# M8416V1.net
KiCad netlist of a schematic drawn in EAGLE
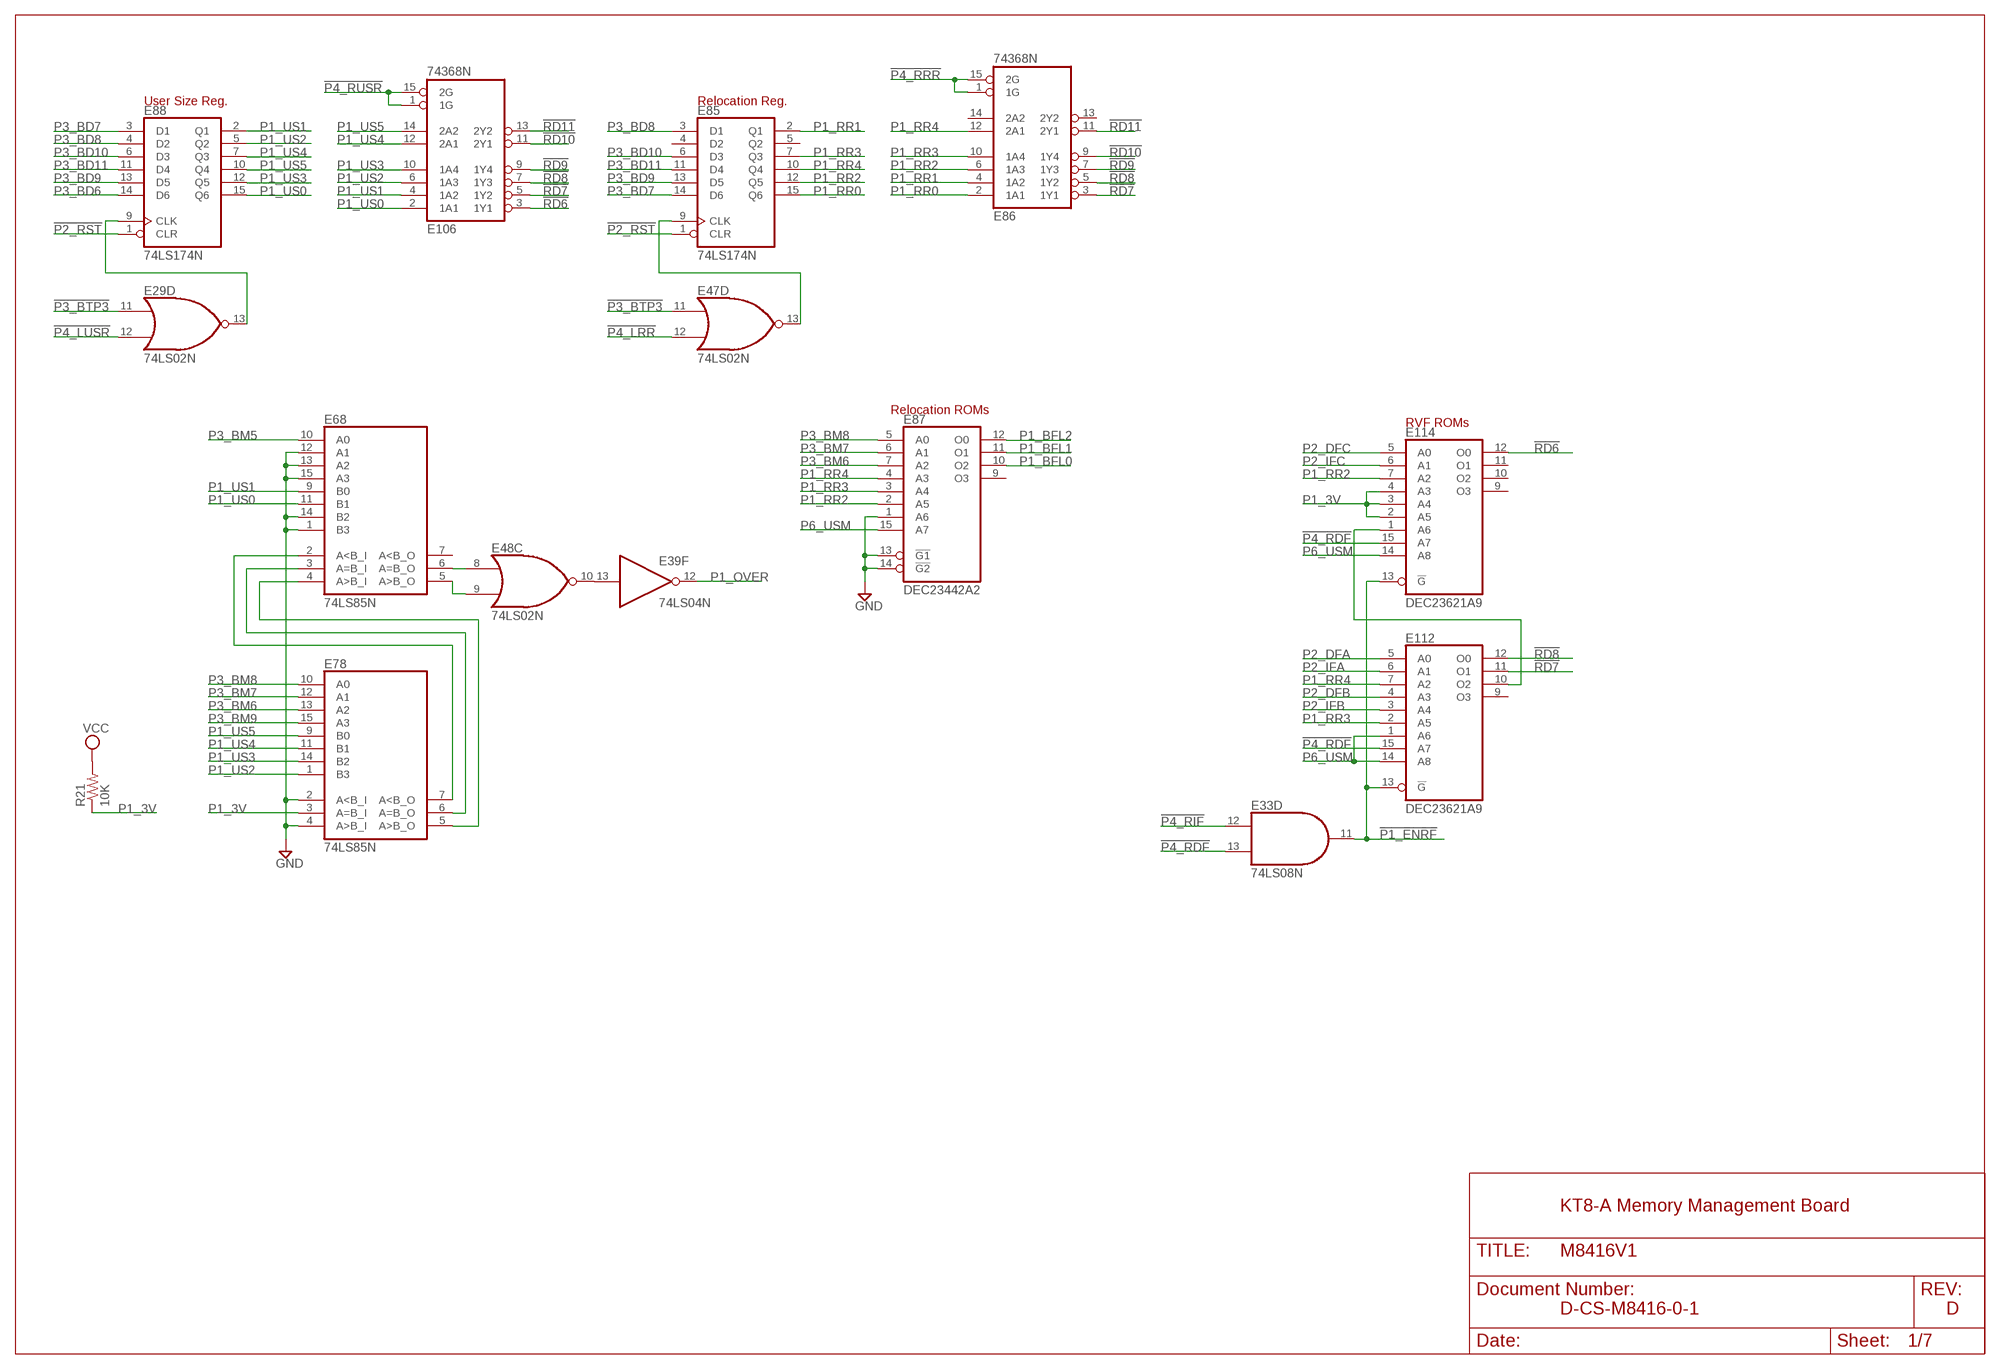
[diagram p0: schematic, sheet 1]
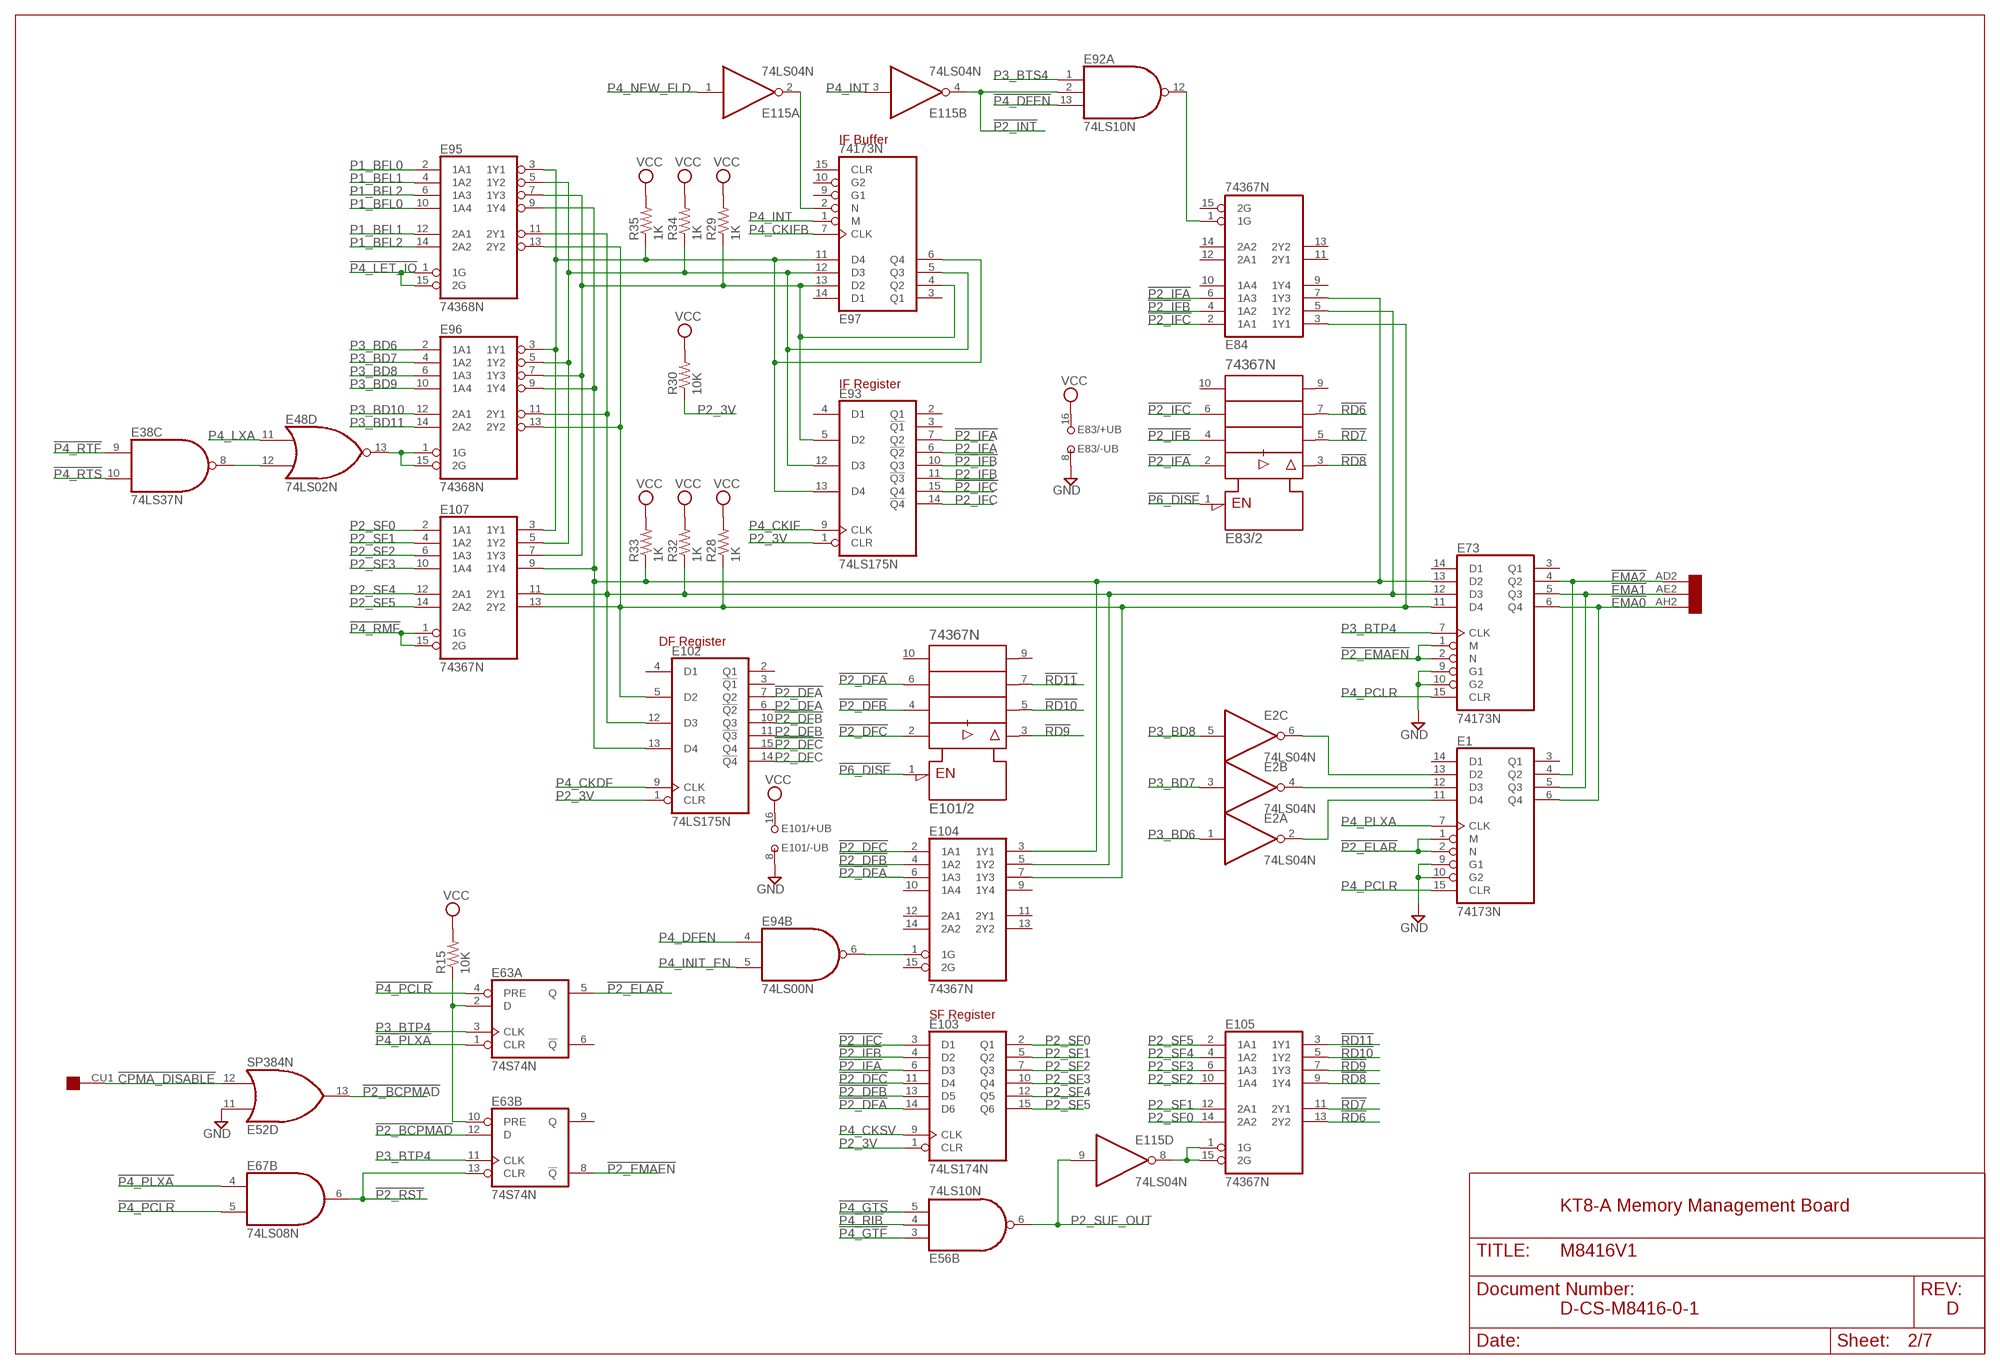
[diagram p1: schematic, sheet 2]
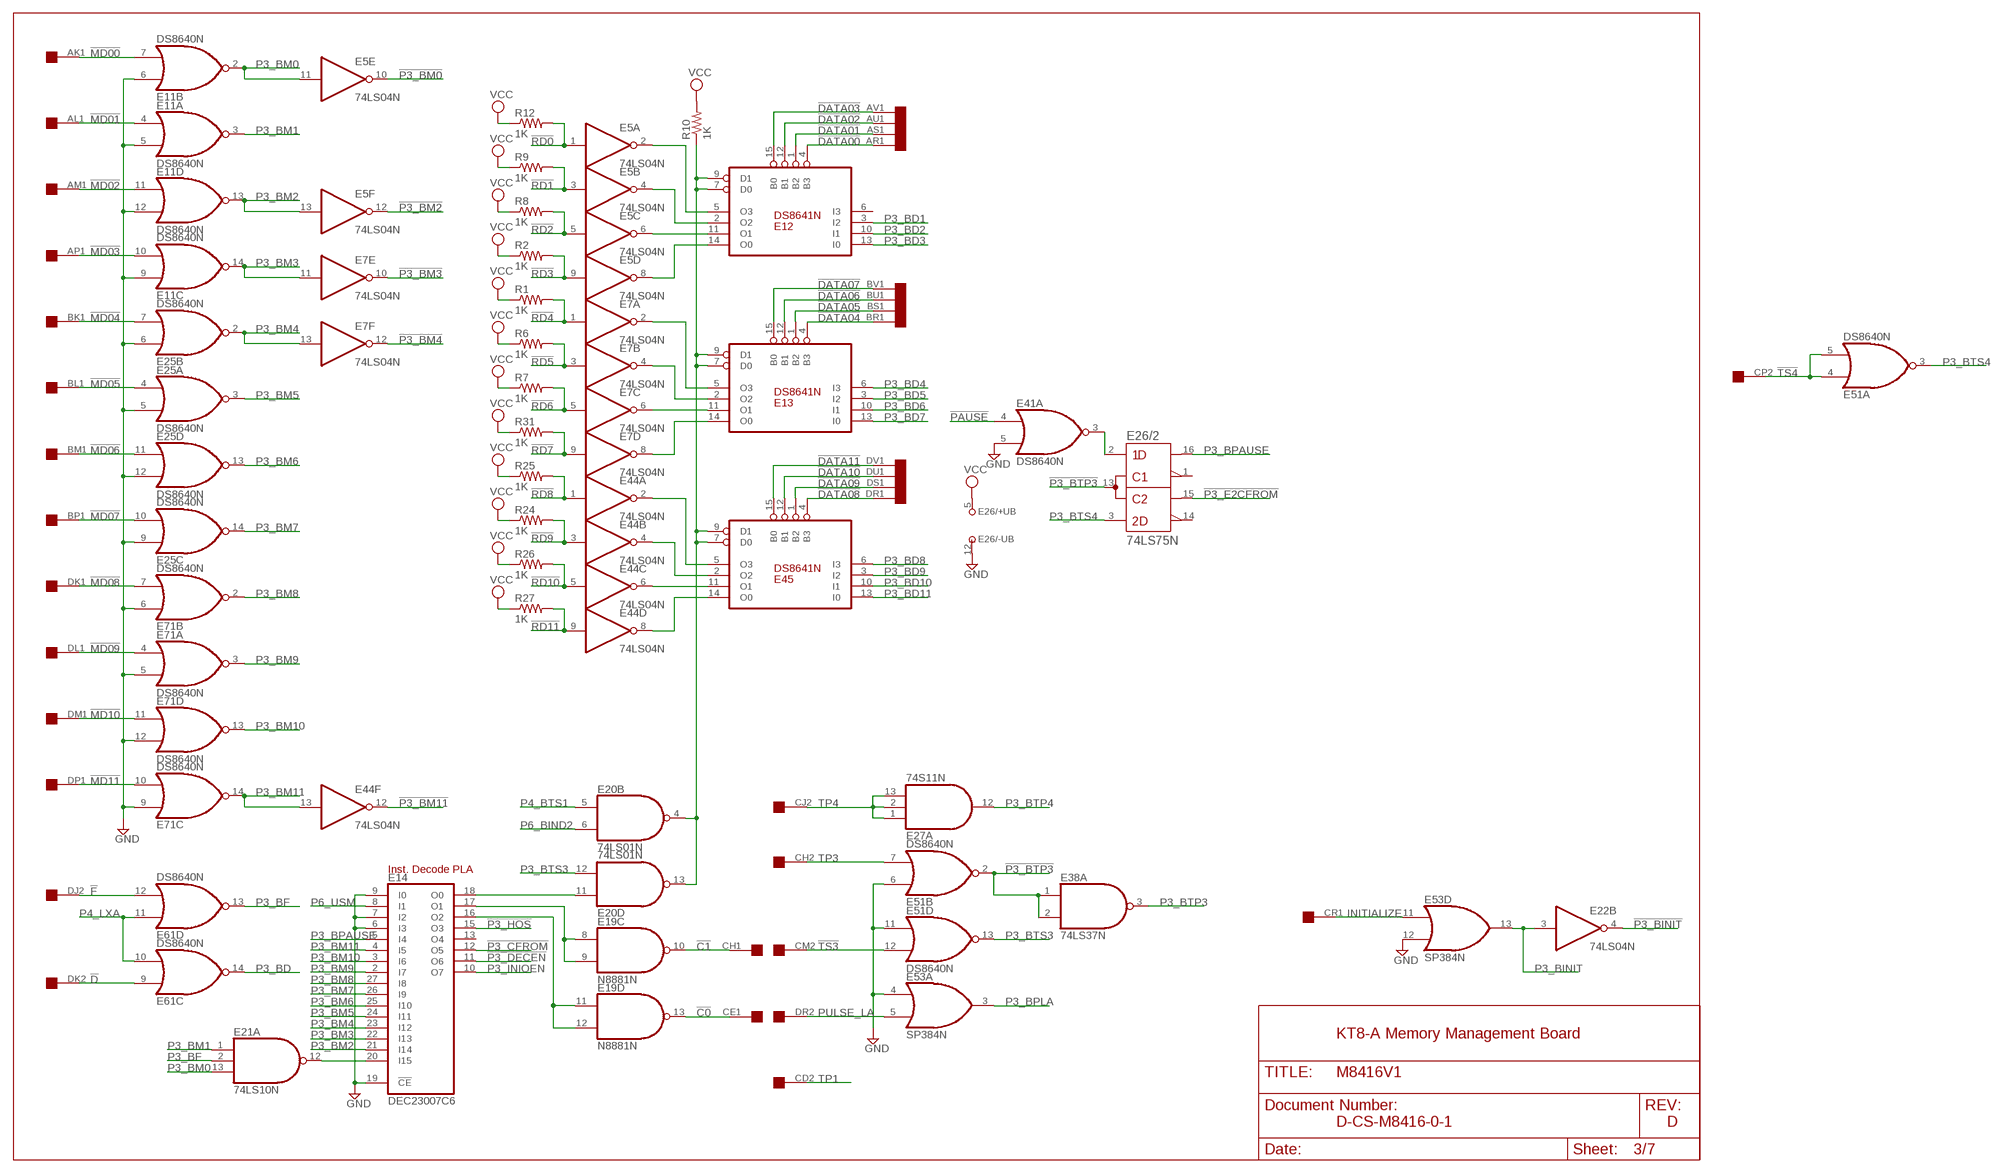
[diagram p2: schematic, sheet 3]
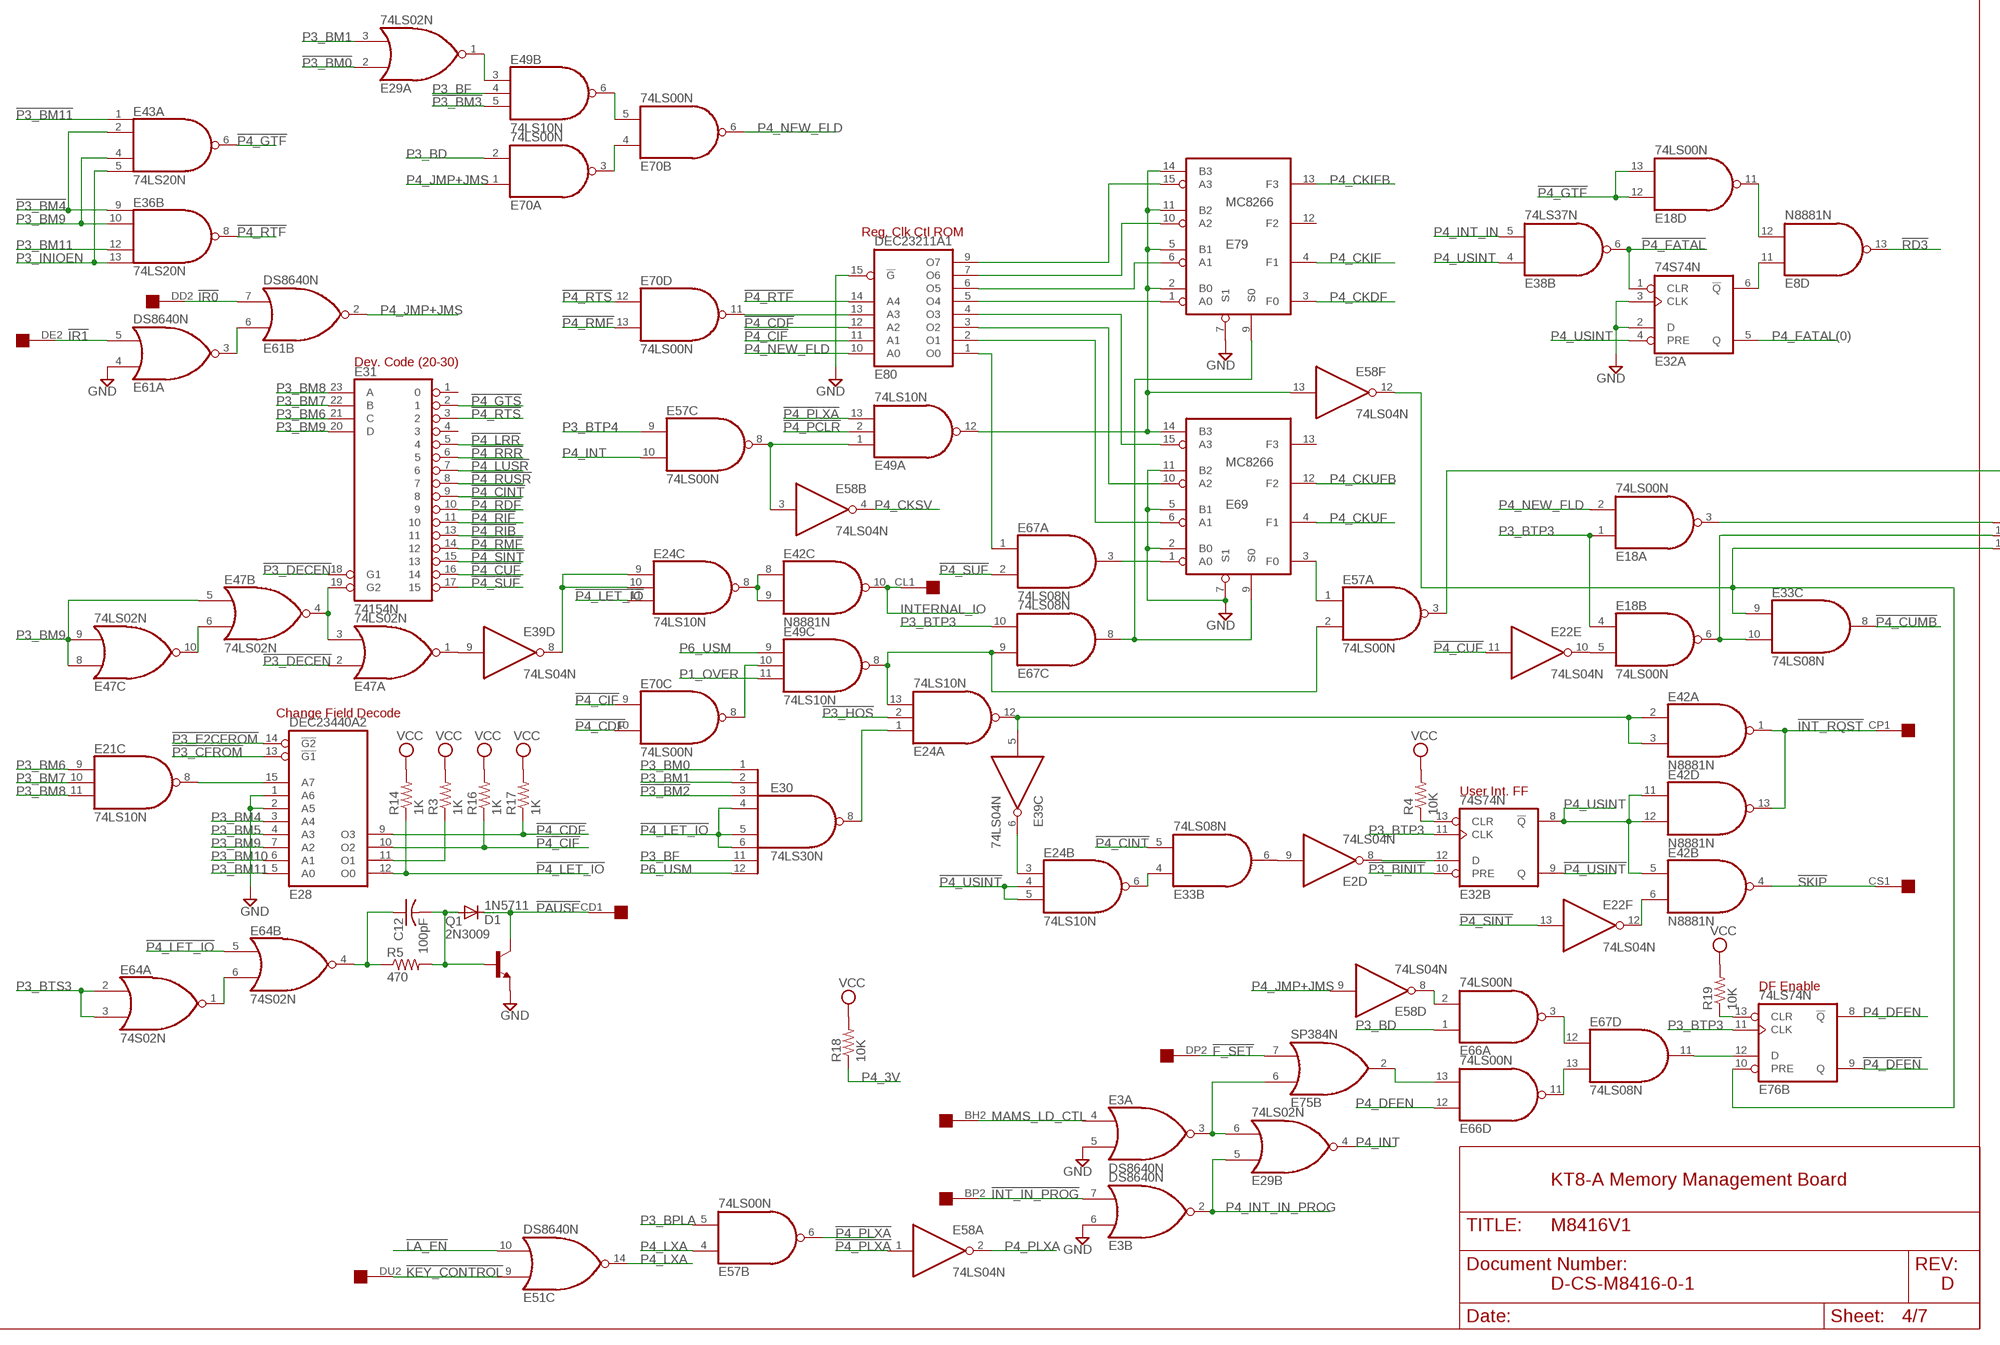
[diagram p3: schematic, sheet 4, part 1 of 2]
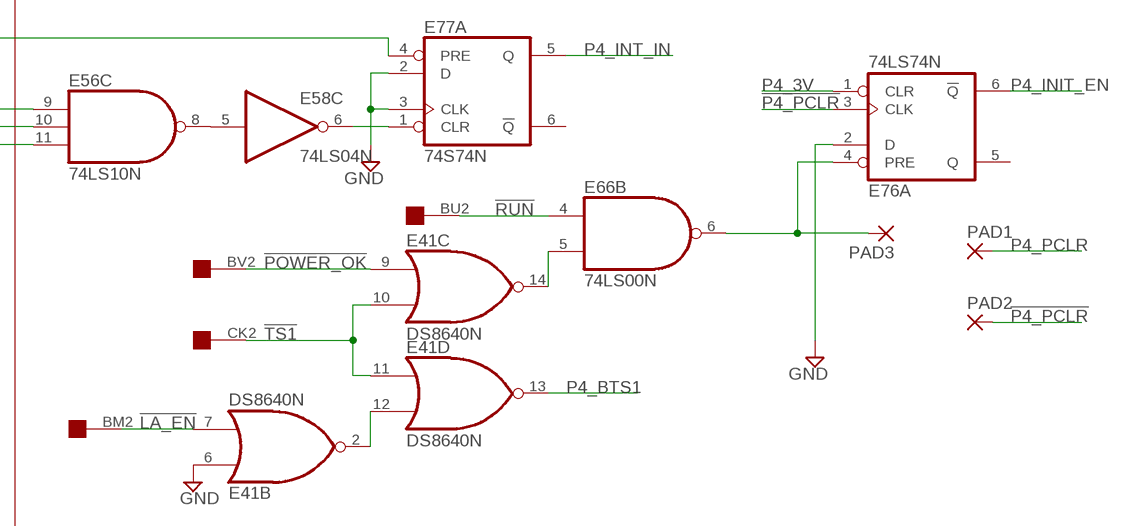
[diagram p4: schematic, sheet 4, part 2 of 2]
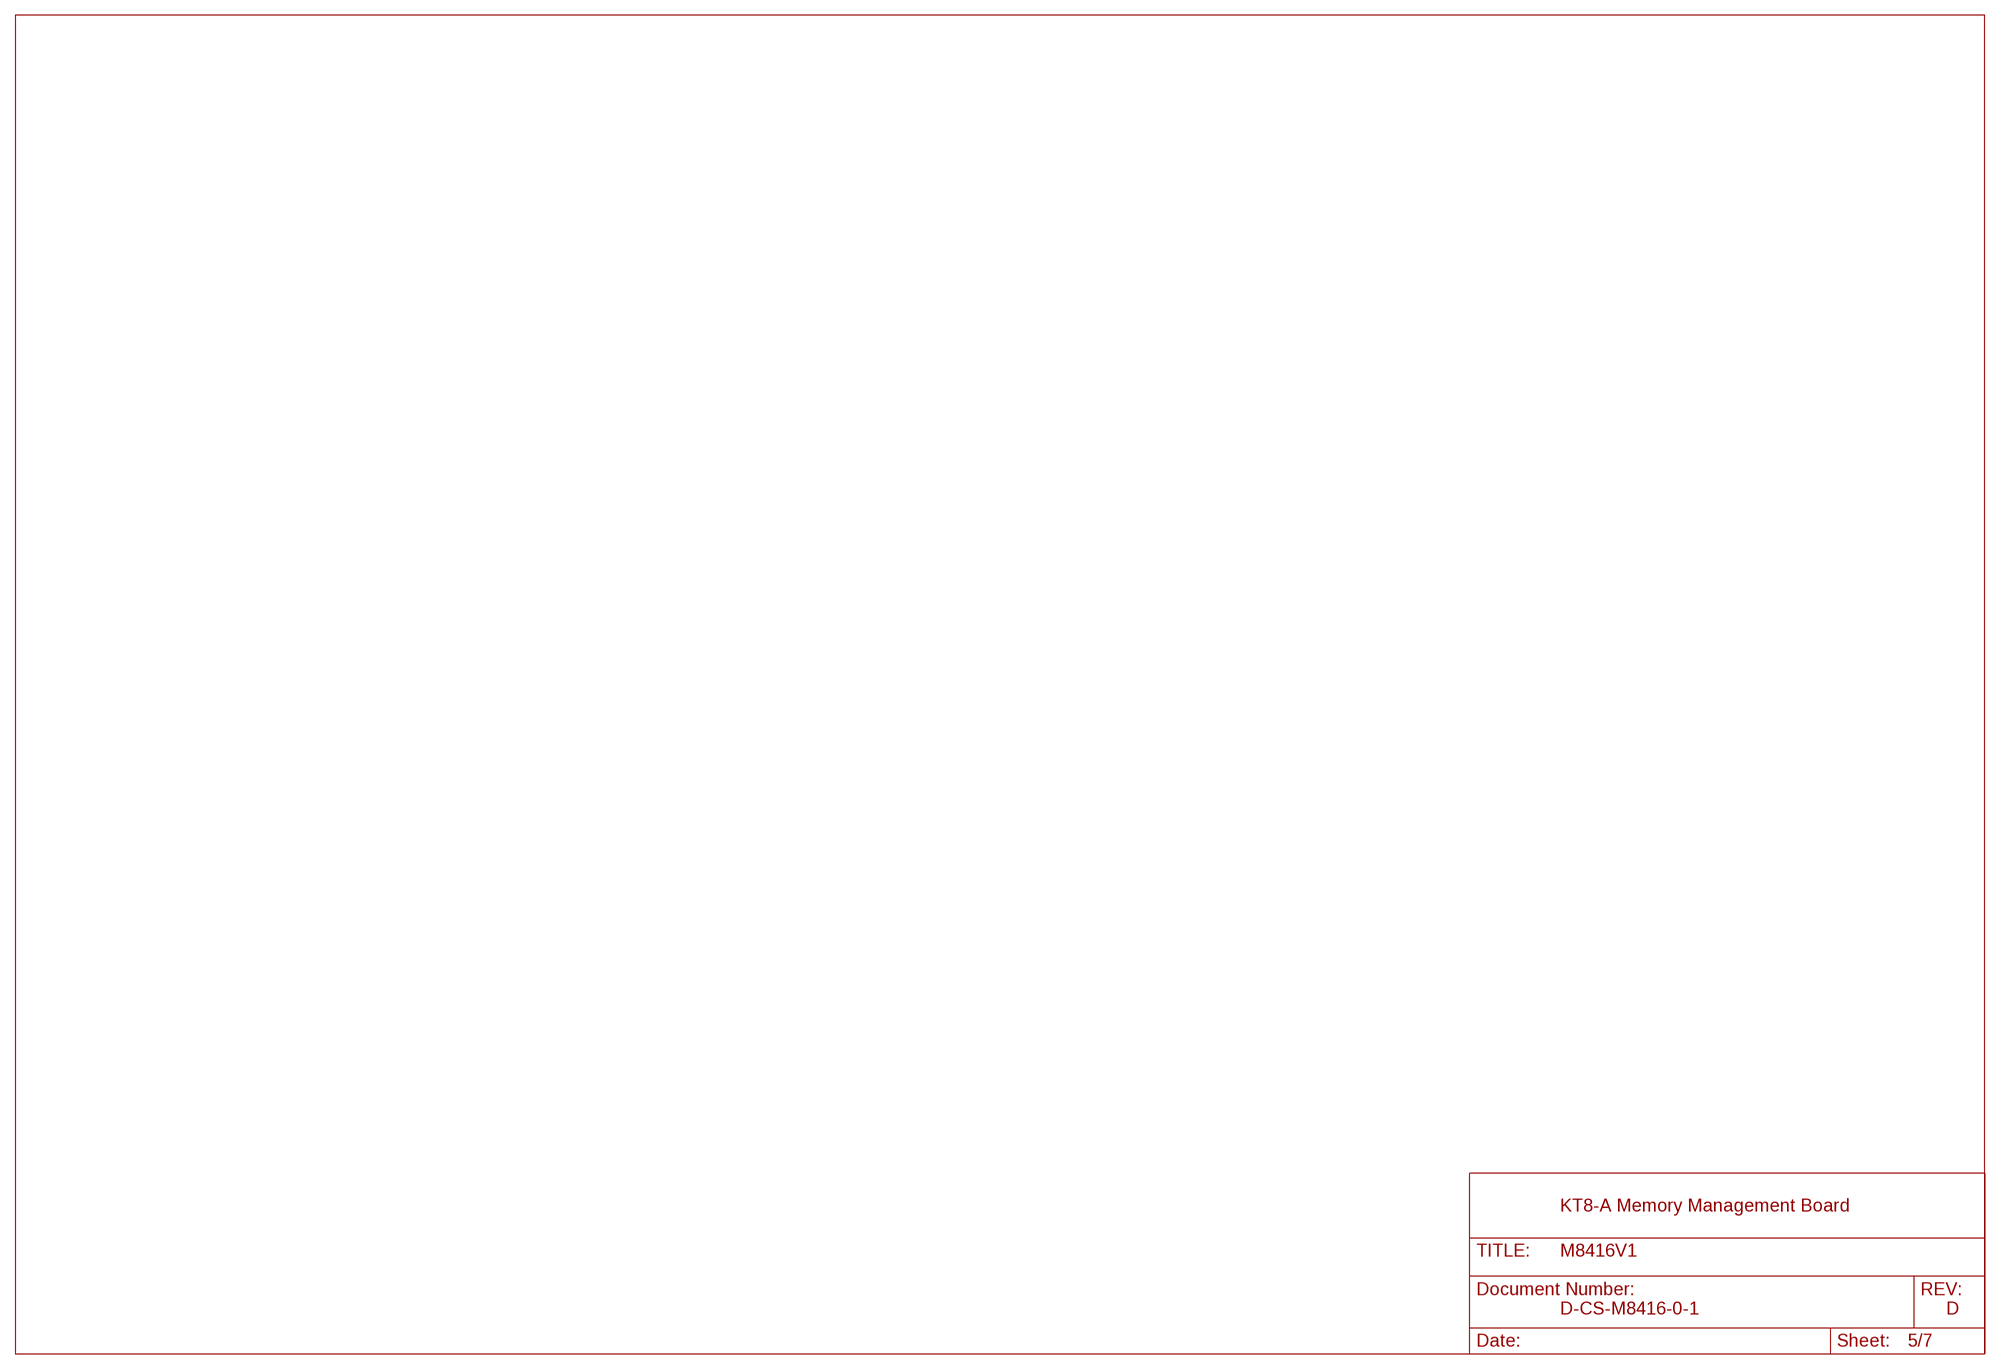
[diagram p5: schematic, sheet 5]
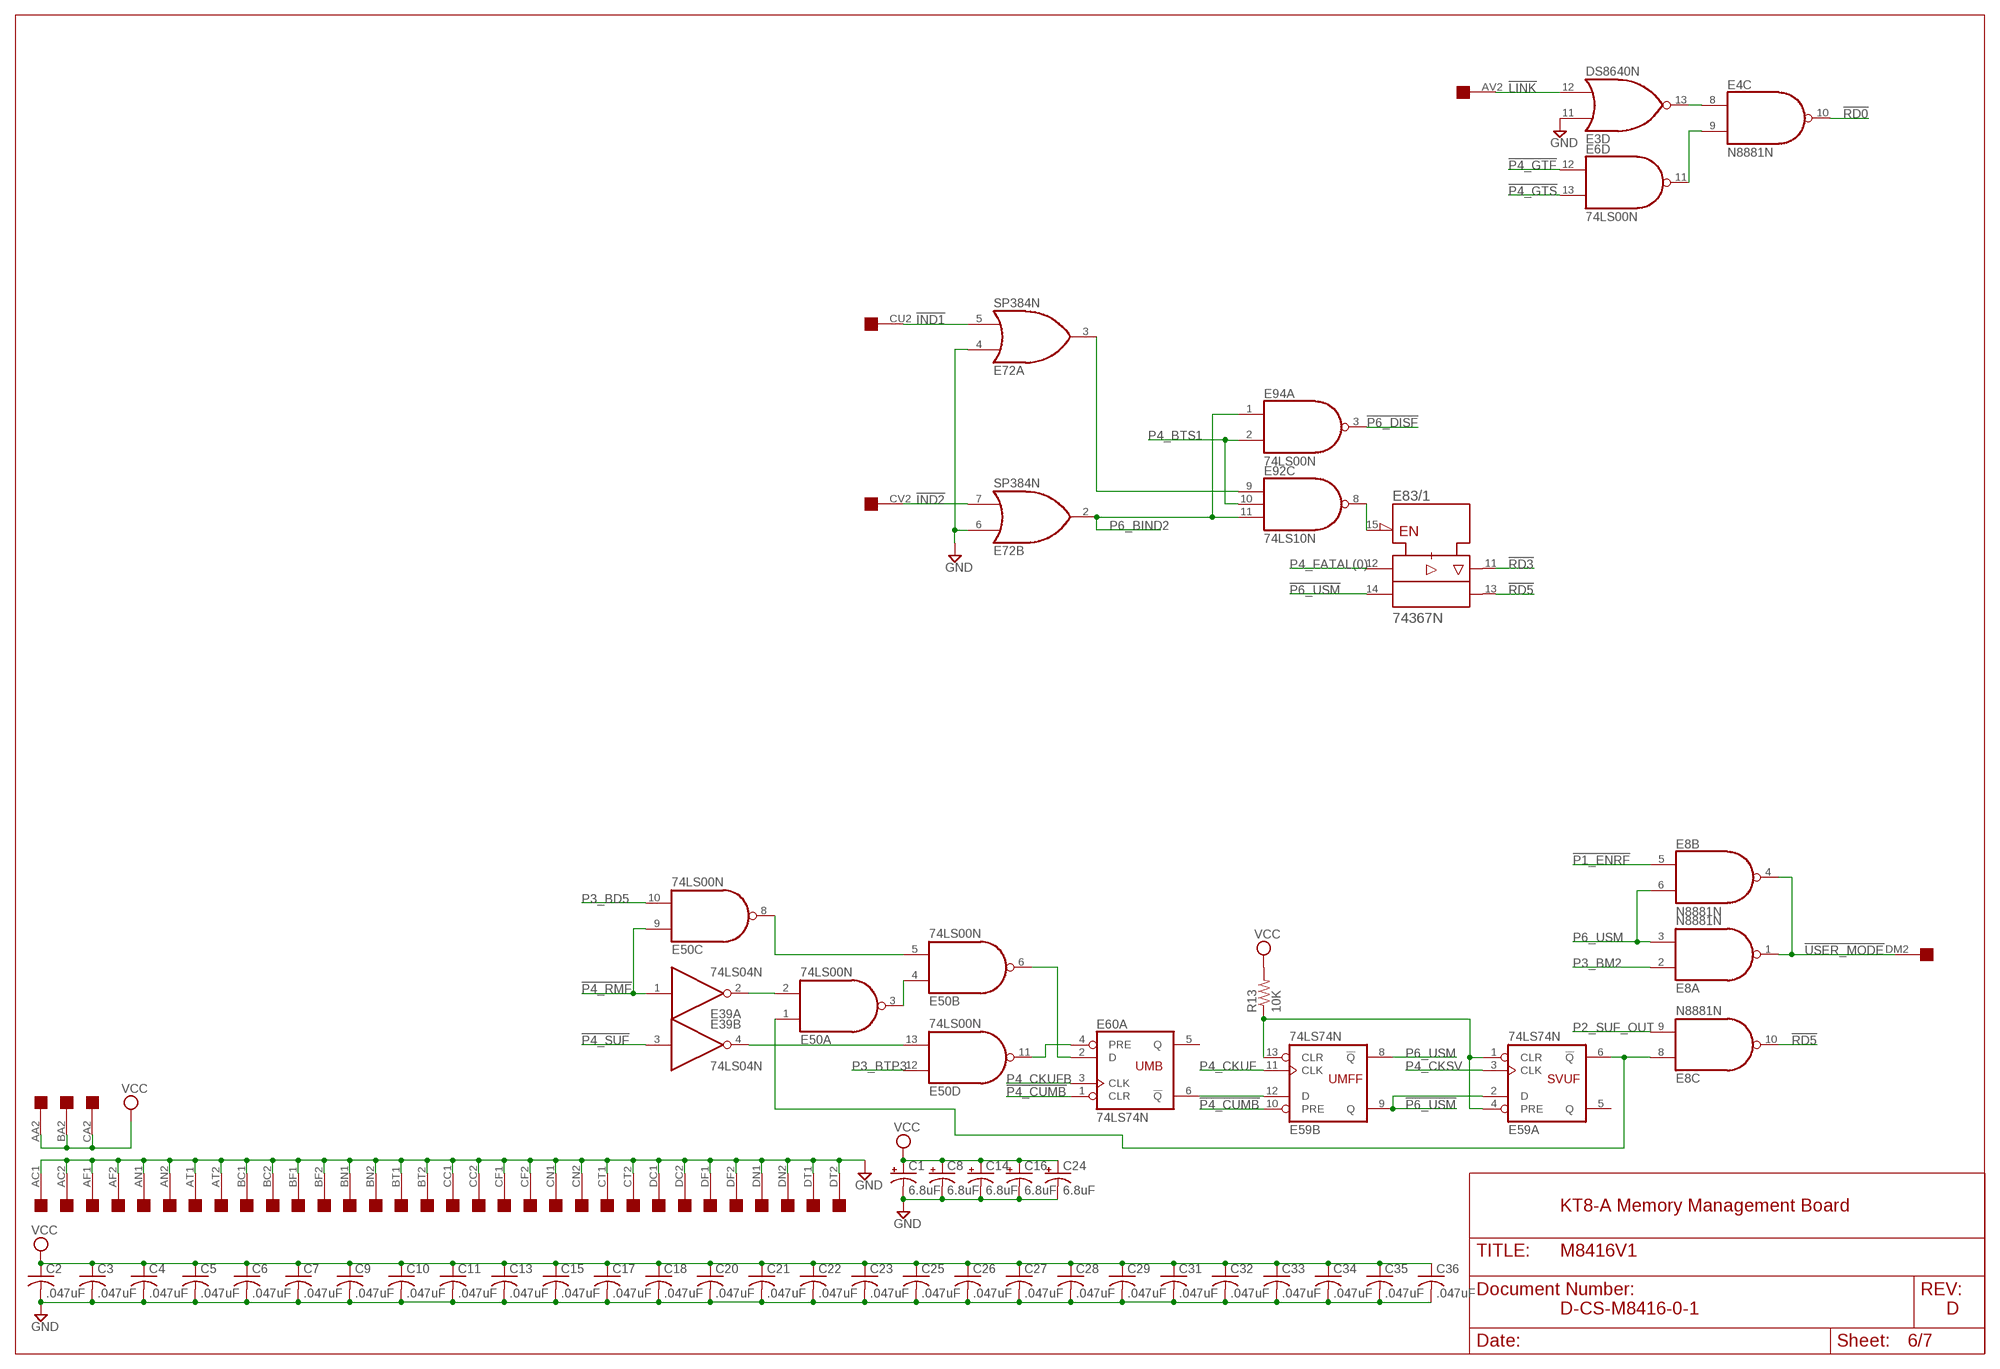
[diagram p6: schematic, sheet 6]
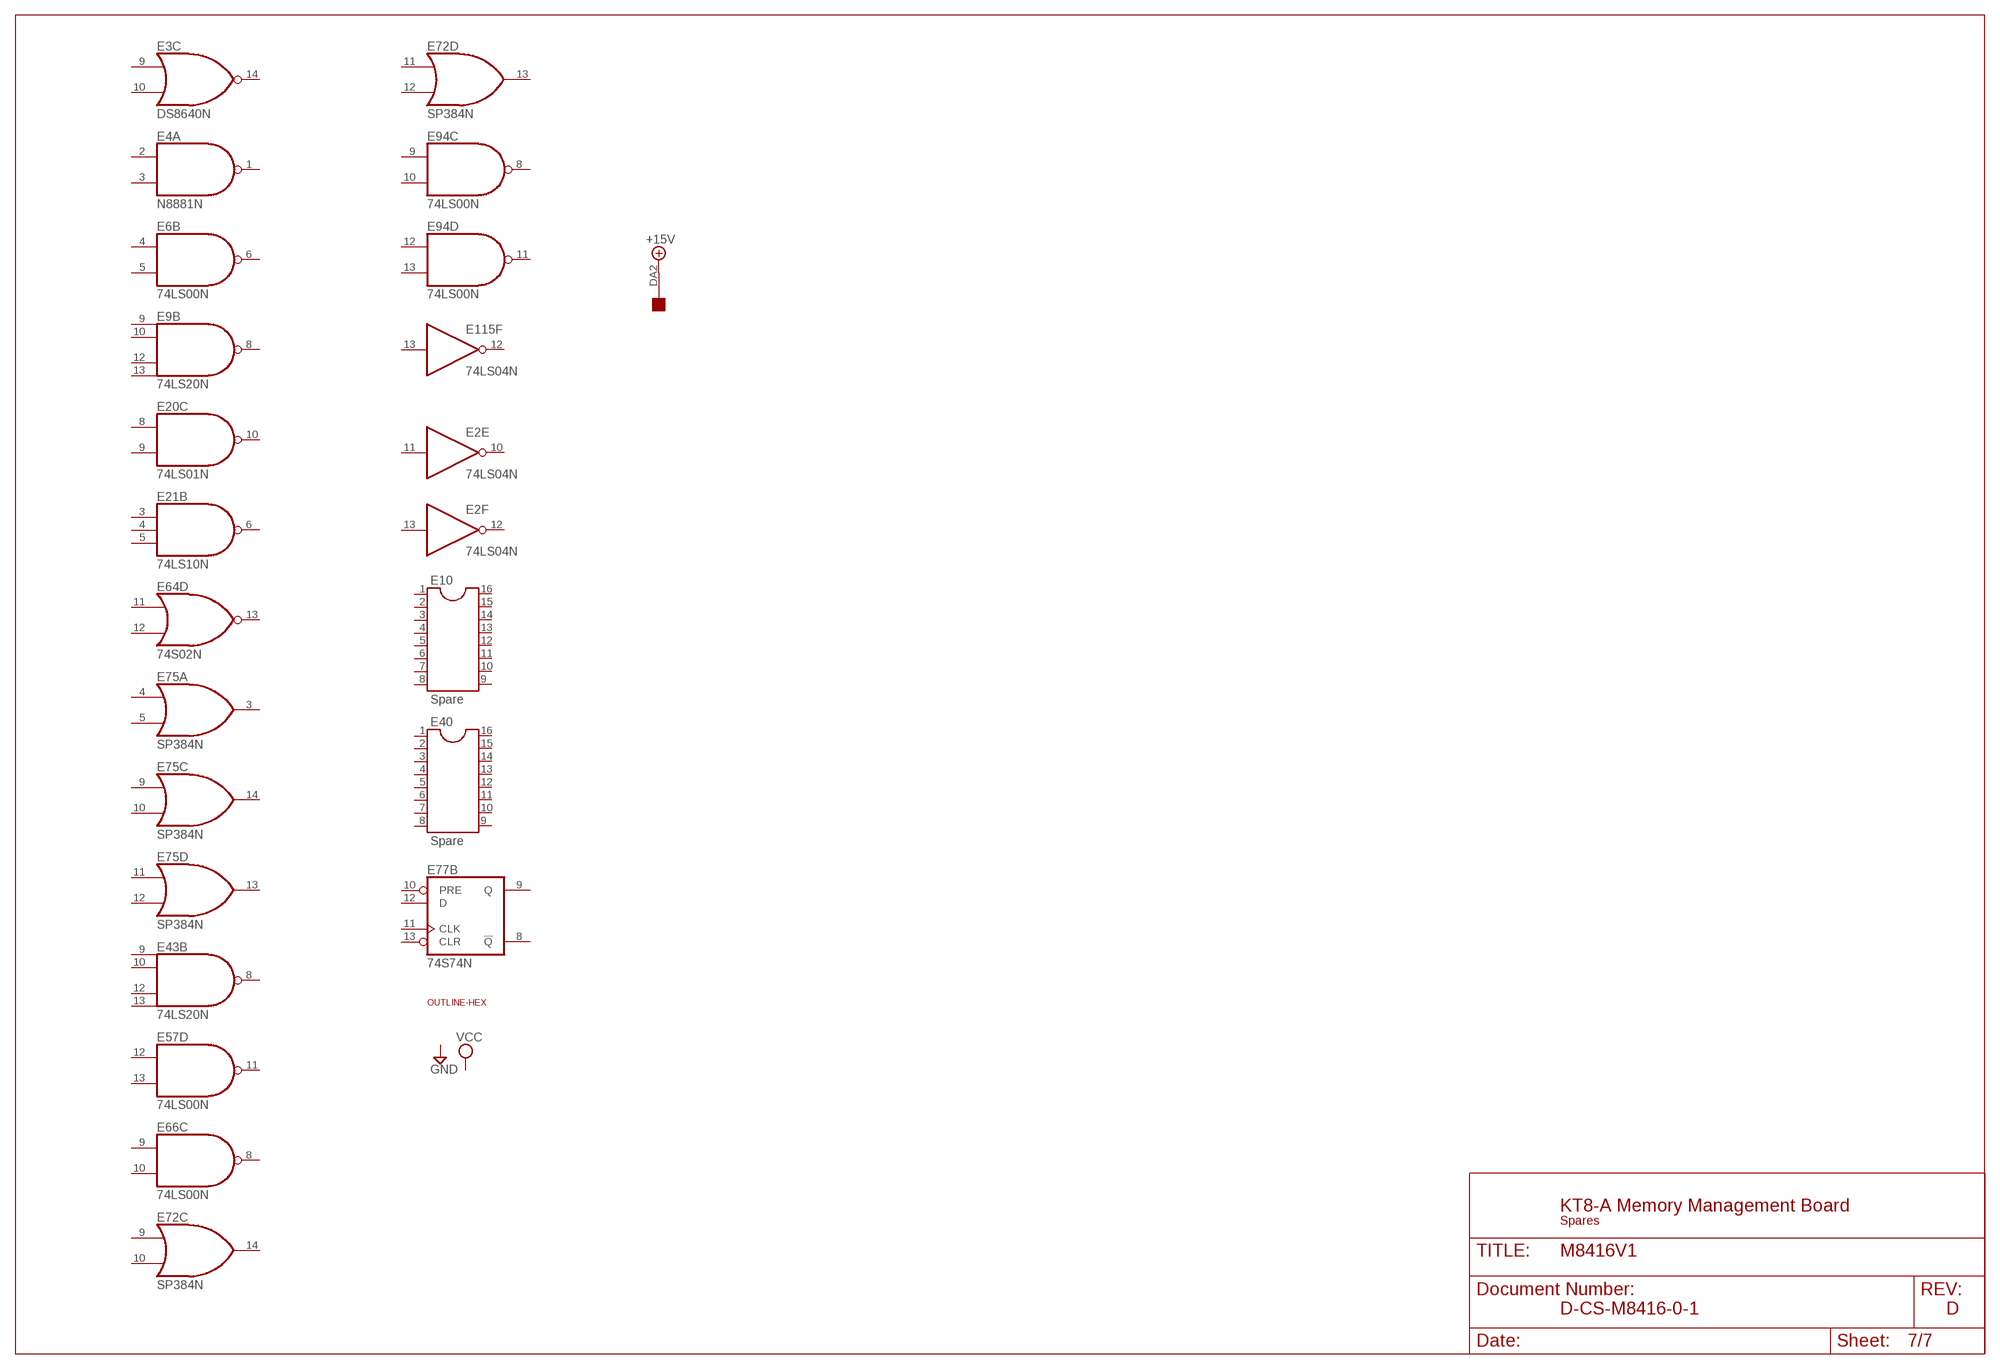
[diagram p7: schematic, sheet 7]

(export (version "E")
  (design (tool "Eeschema 10.0.6"))
  (components
    (comp (ref "E2")
      (value "74LS04N")
      (footprint "eagle-import:DIL14")
      (libsource (lib "eagle-import") (part "7404NLS"))
    )
    (comp (ref "E3")
      (value "DS8640N")
      (footprint "eagle-import:DIL14")
      (libsource (lib "eagle-import") (part "DS8640N"))
    )
    (comp (ref "E4")
      (value "N8881N")
      (footprint "eagle-import:DIL14")
      (libsource (lib "eagle-import") (part "N8881N"))
    )
    (comp (ref "E6")
      (value "74LS00N")
      (footprint "eagle-import:DIL14")
      (libsource (lib "eagle-import") (part "7400NLS"))
    )
    (comp (ref "E9")
      (value "74LS20N")
      (footprint "eagle-import:DIL14")
      (libsource (lib "eagle-import") (part "7420NLS"))
    )
    (comp (ref "E10")
      (value "Spare")
      (footprint "eagle-import:SOCKET-16")
      (libsource (lib "eagle-import") (part "DIL16S"))
    )
    (comp (ref "E20")
      (value "74LS01N")
      (footprint "eagle-import:DIL14")
      (libsource (lib "eagle-import") (part "7401NLS"))
    )
    (comp (ref "E21")
      (value "74LS10N")
      (footprint "eagle-import:DIL14")
      (libsource (lib "eagle-import") (part "7410NLS"))
    )
    (comp (ref "E40")
      (value "Spare")
      (footprint "eagle-import:SOCKET-16")
      (libsource (lib "eagle-import") (part "DIL16S"))
    )
    (comp (ref "E43")
      (value "74LS20N")
      (footprint "eagle-import:DIL14")
      (libsource (lib "eagle-import") (part "7420NLS"))
    )
    (comp (ref "E57")
      (value "74LS00N")
      (footprint "eagle-import:DIL14")
      (libsource (lib "eagle-import") (part "7400NLS"))
    )
    (comp (ref "E64")
      (value "74S02N")
      (footprint "eagle-import:DIL14")
      (libsource (lib "eagle-import") (part "7402NS"))
    )
    (comp (ref "E66")
      (value "74LS00N")
      (footprint "eagle-import:DIL14")
      (libsource (lib "eagle-import") (part "7400NLS"))
    )
    (comp (ref "E72")
      (value "SP384N")
      (footprint "eagle-import:DIL14")
      (libsource (lib "eagle-import") (part "SP384N"))
    )
    (comp (ref "E75")
      (value "SP384N")
      (footprint "eagle-import:DIL14")
      (libsource (lib "eagle-import") (part "SP384N"))
    )
    (comp (ref "E77")
      (value "74S74N")
      (footprint "eagle-import:DIL14")
      (libsource (lib "eagle-import") (part "7474NS"))
    )
    (comp (ref "E94")
      (value "74LS00N")
      (footprint "eagle-import:DIL14")
      (libsource (lib "eagle-import") (part "7400NLS"))
    )
    (comp (ref "E115")
      (value "74LS04N")
      (footprint "eagle-import:DIL14")
      (libsource (lib "eagle-import") (part "7404NLS"))
    )
    (comp (ref "U$1")
      (value "HEX")
      (footprint "eagle-import:EDGE-CON12")
      (libsource (lib "eagle-import") (part "HEX"))
    )
    (comp (ref "U$2")
      (value "OUTLINE-HEX")
      (footprint "eagle-import:HEX-HEIGHT")
      (libsource (lib "eagle-import") (part "OUTLINE-HEX"))
    )
    (comp (ref "E1")
      (value "74173N")
      (footprint "eagle-import:DIL16")
      (libsource (lib "eagle-import") (part "74173NLS"))
    )
    (comp (ref "E38")
      (value "74LS37N")
      (footprint "eagle-import:DIL14")
      (libsource (lib "eagle-import") (part "7437NLS"))
    )
    (comp (ref "E48")
      (value "74LS02N")
      (footprint "eagle-import:DIL14")
      (libsource (lib "eagle-import") (part "7402NLS"))
    )
    (comp (ref "E52")
      (value "SP384N")
      (footprint "eagle-import:DIL14")
      (libsource (lib "eagle-import") (part "SP384N"))
    )
    (comp (ref "E56")
      (value "74LS10N")
      (footprint "eagle-import:DIL14")
      (libsource (lib "eagle-import") (part "7410NLS"))
    )
    (comp (ref "E63")
      (value "74S74N")
      (footprint "eagle-import:DIL14")
      (libsource (lib "eagle-import") (part "7474NS"))
    )
    (comp (ref "E67")
      (value "74LS08N")
      (footprint "eagle-import:DIL14")
      (libsource (lib "eagle-import") (part "7408NLS"))
    )
    (comp (ref "E73")
      (value "74173N")
      (footprint "eagle-import:DIL16")
      (libsource (lib "eagle-import") (part "74173NLS"))
    )
    (comp (ref "E83")
      (value "74367N")
      (footprint "eagle-import:DIL16")
      (libsource (lib "eagle-import") (part "74367N"))
    )
    (comp (ref "E84")
      (value "74367N")
      (footprint "eagle-import:DIL16")
      (libsource (lib "eagle-import") (part "74xx-us_74367N"))
    )
    (comp (ref "E92")
      (value "74LS10N")
      (footprint "eagle-import:DIL14")
      (libsource (lib "eagle-import") (part "7410NLS"))
    )
    (comp (ref "E93")
      (value "74LS175N")
      (footprint "eagle-import:DIL16")
      (libsource (lib "eagle-import") (part "74175NLS"))
    )
    (comp (ref "E95")
      (value "74368N")
      (footprint "eagle-import:DIL16")
      (libsource (lib "eagle-import") (part "74368N"))
    )
    (comp (ref "E96")
      (value "74368N")
      (footprint "eagle-import:DIL16")
      (libsource (lib "eagle-import") (part "74368N"))
    )
    (comp (ref "E97")
      (value "74173N")
      (footprint "eagle-import:DIL16")
      (libsource (lib "eagle-import") (part "74173NLS"))
    )
    (comp (ref "E101")
      (value "74367N")
      (footprint "eagle-import:DIL16")
      (libsource (lib "eagle-import") (part "74367N"))
    )
    (comp (ref "E102")
      (value "74LS175N")
      (footprint "eagle-import:DIL16")
      (libsource (lib "eagle-import") (part "74175NLS"))
    )
    (comp (ref "E103")
      (value "74LS174N")
      (footprint "eagle-import:DIL16")
      (libsource (lib "eagle-import") (part "74174NLS"))
    )
    (comp (ref "E104")
      (value "74367N")
      (footprint "eagle-import:DIL16")
      (libsource (lib "eagle-import") (part "74xx-us_74367N"))
    )
    (comp (ref "E105")
      (value "74367N")
      (footprint "eagle-import:DIL16")
      (libsource (lib "eagle-import") (part "74xx-us_74367N"))
    )
    (comp (ref "E107")
      (value "74367N")
      (footprint "eagle-import:DIL16")
      (libsource (lib "eagle-import") (part "74xx-us_74367N"))
    )
    (comp (ref "R15")
      (value "10K")
      (footprint "eagle-import:0207_10")
      (libsource (lib "eagle-import") (part "R-US_0207/10"))
    )
    (comp (ref "R28")
      (value "1K")
      (footprint "eagle-import:0207_10")
      (libsource (lib "eagle-import") (part "R-US_0207/10"))
    )
    (comp (ref "R29")
      (value "1K")
      (footprint "eagle-import:0207_10")
      (libsource (lib "eagle-import") (part "R-US_0207/10"))
    )
    (comp (ref "R30")
      (value "10K")
      (footprint "eagle-import:0207_10")
      (libsource (lib "eagle-import") (part "R-US_0207/10"))
    )
    (comp (ref "R32")
      (value "1K")
      (footprint "eagle-import:0207_10")
      (libsource (lib "eagle-import") (part "R-US_0207/10"))
    )
    (comp (ref "R33")
      (value "1K")
      (footprint "eagle-import:0207_10")
      (libsource (lib "eagle-import") (part "R-US_0207/10"))
    )
    (comp (ref "R34")
      (value "1K")
      (footprint "eagle-import:0207_10")
      (libsource (lib "eagle-import") (part "R-US_0207/10"))
    )
    (comp (ref "R35")
      (value "1K")
      (footprint "eagle-import:0207_10")
      (libsource (lib "eagle-import") (part "R-US_0207/10"))
    )
    (comp (ref "E29")
      (value "74LS02N")
      (footprint "eagle-import:DIL14")
      (libsource (lib "eagle-import") (part "7402NLS"))
    )
    (comp (ref "E33")
      (value "74LS08N")
      (footprint "eagle-import:DIL14")
      (libsource (lib "eagle-import") (part "7408NLS"))
    )
    (comp (ref "E39")
      (value "74LS04N")
      (footprint "eagle-import:DIL14")
      (libsource (lib "eagle-import") (part "7404NLS"))
    )
    (comp (ref "E47")
      (value "74LS02N")
      (footprint "eagle-import:DIL14")
      (libsource (lib "eagle-import") (part "7402NLS"))
    )
    (comp (ref "E68")
      (value "74LS85N")
      (footprint "eagle-import:DIL16")
      (libsource (lib "eagle-import") (part "7485NLS"))
    )
    (comp (ref "E78")
      (value "74LS85N")
      (footprint "eagle-import:DIL16")
      (libsource (lib "eagle-import") (part "7485NLS"))
    )
    (comp (ref "E85")
      (value "74LS174N")
      (footprint "eagle-import:DIL16")
      (libsource (lib "eagle-import") (part "74174NLS"))
    )
    (comp (ref "E86")
      (value "74368N")
      (footprint "eagle-import:DIL16")
      (libsource (lib "eagle-import") (part "74368N"))
    )
    (comp (ref "E87")
      (value "DEC23442A2")
      (footprint "eagle-import:DIL16")
      (libsource (lib "eagle-import") (part "74S287"))
    )
    (comp (ref "E88")
      (value "74LS174N")
      (footprint "eagle-import:DIL16")
      (libsource (lib "eagle-import") (part "74174NLS"))
    )
    (comp (ref "E106")
      (value "74368N")
      (footprint "eagle-import:DIL16")
      (libsource (lib "eagle-import") (part "74368N"))
    )
    (comp (ref "E112")
      (value "DEC23621A9")
      (footprint "eagle-import:DIL16")
      (libsource (lib "eagle-import") (part "74S571"))
    )
    (comp (ref "E114")
      (value "DEC23621A9")
      (footprint "eagle-import:DIL16")
      (libsource (lib "eagle-import") (part "74S571"))
    )
    (comp (ref "R21")
      (value "10K")
      (footprint "eagle-import:0207_10")
      (libsource (lib "eagle-import") (part "R-US_0207/10"))
    )
    (comp (ref "C1")
      (value "6.8uF")
      (footprint "eagle-import:E12-8")
      (libsource (lib "eagle-import") (part "CPOL-USE20-8AXIAL"))
    )
    (comp (ref "C2")
      (value ".047uF")
      (footprint "eagle-import:C102-043X133")
      (libsource (lib "eagle-import") (part "C-US102-043X133"))
    )
    (comp (ref "C3")
      (value ".047uF")
      (footprint "eagle-import:C102-043X133")
      (libsource (lib "eagle-import") (part "C-US102-043X133"))
    )
    (comp (ref "C4")
      (value ".047uF")
      (footprint "eagle-import:C102-043X133")
      (libsource (lib "eagle-import") (part "C-US102-043X133"))
    )
    (comp (ref "C5")
      (value ".047uF")
      (footprint "eagle-import:C102-043X133")
      (libsource (lib "eagle-import") (part "C-US102-043X133"))
    )
    (comp (ref "C6")
      (value ".047uF")
      (footprint "eagle-import:C102-043X133")
      (libsource (lib "eagle-import") (part "C-US102-043X133"))
    )
    (comp (ref "C7")
      (value ".047uF")
      (footprint "eagle-import:C102-043X133")
      (libsource (lib "eagle-import") (part "C-US102-043X133"))
    )
    (comp (ref "C8")
      (value "6.8uF")
      (footprint "eagle-import:E12-8")
      (libsource (lib "eagle-import") (part "CPOL-USE20-8AXIAL"))
    )
    (comp (ref "C9")
      (value ".047uF")
      (footprint "eagle-import:C102-043X133")
      (libsource (lib "eagle-import") (part "C-US102-043X133"))
    )
    (comp (ref "C10")
      (value ".047uF")
      (footprint "eagle-import:C102-043X133")
      (libsource (lib "eagle-import") (part "C-US102-043X133"))
    )
    (comp (ref "C11")
      (value ".047uF")
      (footprint "eagle-import:C102-043X133")
      (libsource (lib "eagle-import") (part "C-US102-043X133"))
    )
    (comp (ref "C13")
      (value ".047uF")
      (footprint "eagle-import:C102-043X133")
      (libsource (lib "eagle-import") (part "C-US102-043X133"))
    )
    (comp (ref "C14")
      (value "6.8uF")
      (footprint "eagle-import:E12-8")
      (libsource (lib "eagle-import") (part "CPOL-USE20-8AXIAL"))
    )
    (comp (ref "C15")
      (value ".047uF")
      (footprint "eagle-import:C102-043X133")
      (libsource (lib "eagle-import") (part "C-US102-043X133"))
    )
    (comp (ref "C16")
      (value "6.8uF")
      (footprint "eagle-import:E12-8")
      (libsource (lib "eagle-import") (part "CPOL-USE20-8AXIAL"))
    )
    (comp (ref "C17")
      (value ".047uF")
      (footprint "eagle-import:C102-043X133")
      (libsource (lib "eagle-import") (part "C-US102-043X133"))
    )
    (comp (ref "C18")
      (value ".047uF")
      (footprint "eagle-import:C102-043X133")
      (libsource (lib "eagle-import") (part "C-US102-043X133"))
    )
    (comp (ref "C20")
      (value ".047uF")
      (footprint "eagle-import:C102-043X133")
      (libsource (lib "eagle-import") (part "C-US102-043X133"))
    )
    (comp (ref "C21")
      (value ".047uF")
      (footprint "eagle-import:C102-043X133")
      (libsource (lib "eagle-import") (part "C-US102-043X133"))
    )
    (comp (ref "C22")
      (value ".047uF")
      (footprint "eagle-import:C102-043X133")
      (libsource (lib "eagle-import") (part "C-US102-043X133"))
    )
    (comp (ref "C23")
      (value ".047uF")
      (footprint "eagle-import:C102-043X133")
      (libsource (lib "eagle-import") (part "C-US102-043X133"))
    )
    (comp (ref "C24")
      (value "6.8uF")
      (footprint "eagle-import:E12-8")
      (libsource (lib "eagle-import") (part "CPOL-USE20-8AXIAL"))
    )
    (comp (ref "C25")
      (value ".047uF")
      (footprint "eagle-import:C102-043X133")
      (libsource (lib "eagle-import") (part "C-US102-043X133"))
    )
    (comp (ref "C26")
      (value ".047uF")
      (footprint "eagle-import:C102-043X133")
      (libsource (lib "eagle-import") (part "C-US102-043X133"))
    )
    (comp (ref "C27")
      (value ".047uF")
      (footprint "eagle-import:C102-043X133")
      (libsource (lib "eagle-import") (part "C-US102-043X133"))
    )
    (comp (ref "C28")
      (value ".047uF")
      (footprint "eagle-import:C102-043X133")
      (libsource (lib "eagle-import") (part "C-US102-043X133"))
    )
    (comp (ref "C29")
      (value ".047uF")
      (footprint "eagle-import:C102-043X133")
      (libsource (lib "eagle-import") (part "C-US102-043X133"))
    )
    (comp (ref "C31")
      (value ".047uF")
      (footprint "eagle-import:C102-043X133")
      (libsource (lib "eagle-import") (part "C-US102-043X133"))
    )
    (comp (ref "C32")
      (value ".047uF")
      (footprint "eagle-import:C102-043X133")
      (libsource (lib "eagle-import") (part "C-US102-043X133"))
    )
    (comp (ref "C33")
      (value ".047uF")
      (footprint "eagle-import:C102-043X133")
      (libsource (lib "eagle-import") (part "C-US102-043X133"))
    )
    (comp (ref "C34")
      (value ".047uF")
      (footprint "eagle-import:C102-043X133")
      (libsource (lib "eagle-import") (part "C-US102-043X133"))
    )
    (comp (ref "C35")
      (value ".047uF")
      (footprint "eagle-import:C102-043X133")
      (libsource (lib "eagle-import") (part "C-US102-043X133"))
    )
    (comp (ref "C36")
      (value ".047uF")
      (footprint "eagle-import:C102-043X133")
      (libsource (lib "eagle-import") (part "C-US102-043X133"))
    )
    (comp (ref "E8")
      (value "N8881N")
      (footprint "eagle-import:DIL14")
      (libsource (lib "eagle-import") (part "N8881N"))
    )
    (comp (ref "E50")
      (value "74LS00N")
      (footprint "eagle-import:DIL14")
      (libsource (lib "eagle-import") (part "7400NLS"))
    )
    (comp (ref "E59")
      (value "74LS74N")
      (footprint "eagle-import:DIL14")
      (libsource (lib "eagle-import") (part "7474NLS"))
    )
    (comp (ref "E60")
      (value "74LS74N")
      (footprint "eagle-import:DIL14")
      (libsource (lib "eagle-import") (part "7474NLS"))
    )
    (comp (ref "R13")
      (value "10K")
      (footprint "eagle-import:0207_10")
      (libsource (lib "eagle-import") (part "R-US_0207/10"))
    )
    (comp (ref "C12")
      (value "100pF")
      (footprint "eagle-import:C063-025X075")
      (libsource (lib "eagle-import") (part "C-US"))
    )
    (comp (ref "D1")
      (value "1N5711")
      (footprint "eagle-import:DO35-10")
      (libsource (lib "eagle-import") (part "DIODE-DO35-10"))
    )
    (comp (ref "E18")
      (value "74LS00N")
      (footprint "eagle-import:DIL14")
      (libsource (lib "eagle-import") (part "7400NLS"))
    )
    (comp (ref "E22")
      (value "74LS04N")
      (footprint "eagle-import:DIL14")
      (libsource (lib "eagle-import") (part "7404NLS"))
    )
    (comp (ref "E24")
      (value "74LS10N")
      (footprint "eagle-import:DIL14")
      (libsource (lib "eagle-import") (part "7410NLS"))
    )
    (comp (ref "E28")
      (value "DEC23440A2")
      (footprint "eagle-import:DIL16")
      (libsource (lib "eagle-import") (part "74S287"))
    )
    (comp (ref "E30")
      (value "74LS30N")
      (footprint "eagle-import:DIL14")
      (libsource (lib "eagle-import") (part "7430NLS"))
    )
    (comp (ref "E31")
      (value "74154N")
      (footprint "eagle-import:DIL24-6")
      (libsource (lib "eagle-import") (part "74154N"))
    )
    (comp (ref "E32")
      (value "74S74N")
      (footprint "eagle-import:DIL14")
      (libsource (lib "eagle-import") (part "7474NS"))
    )
    (comp (ref "E36")
      (value "74LS20N")
      (footprint "eagle-import:DIL14")
      (libsource (lib "eagle-import") (part "7420NLS"))
    )
    (comp (ref "E41")
      (value "DS8640N")
      (footprint "eagle-import:DIL14")
      (libsource (lib "eagle-import") (part "DS8640N"))
    )
    (comp (ref "E42")
      (value "N8881N")
      (footprint "eagle-import:DIL14")
      (libsource (lib "eagle-import") (part "N8881N"))
    )
    (comp (ref "E49")
      (value "74LS10N")
      (footprint "eagle-import:DIL14")
      (libsource (lib "eagle-import") (part "7410NLS"))
    )
    (comp (ref "E51")
      (value "DS8640N")
      (footprint "eagle-import:DIL14")
      (libsource (lib "eagle-import") (part "DS8640N"))
    )
    (comp (ref "E58")
      (value "74LS04N")
      (footprint "eagle-import:DIL14")
      (libsource (lib "eagle-import") (part "7404NLS"))
    )
    (comp (ref "E61")
      (value "DS8640N")
      (footprint "eagle-import:DIL14")
      (libsource (lib "eagle-import") (part "DS8640N"))
    )
    (comp (ref "E69")
      (value "MC8266")
      (footprint "eagle-import:DIL16")
      (libsource (lib "eagle-import") (part "MC8266"))
    )
    (comp (ref "E70")
      (value "74LS00N")
      (footprint "eagle-import:DIL14")
      (libsource (lib "eagle-import") (part "7400NLS"))
    )
    (comp (ref "E76")
      (value "74LS74N")
      (footprint "eagle-import:DIL14")
      (libsource (lib "eagle-import") (part "7474NLS"))
    )
    (comp (ref "E79")
      (value "MC8266")
      (footprint "eagle-import:DIL16")
      (libsource (lib "eagle-import") (part "MC8266"))
    )
    (comp (ref "E80")
      (value "DEC23211A1")
      (footprint "eagle-import:DIL16")
      (libsource (lib "eagle-import") (part "74S288"))
    )
    (comp (ref "PAD1")
      (value "1,6/0,8")
      (footprint "eagle-import:1,6_0,8")
      (libsource (lib "eagle-import") (part "1,6/0,8"))
    )
    (comp (ref "PAD2")
      (value "1,6/0,8")
      (footprint "eagle-import:1,6_0,8")
      (libsource (lib "eagle-import") (part "1,6/0,8"))
    )
    (comp (ref "PAD3")
      (value "1,6/0,8")
      (footprint "eagle-import:1,6_0,8")
      (libsource (lib "eagle-import") (part "1,6/0,8"))
    )
    (comp (ref "Q1")
      (value "2N3009")
      (footprint "eagle-import:TO5")
      (libsource (lib "eagle-import") (part "-NPN-TO5"))
    )
    (comp (ref "R3")
      (value "1K")
      (footprint "eagle-import:0207_10")
      (libsource (lib "eagle-import") (part "R-US_0207/10"))
    )
    (comp (ref "R4")
      (value "10K")
      (footprint "eagle-import:0207_10")
      (libsource (lib "eagle-import") (part "R-US_0207/10"))
    )
    (comp (ref "R5")
      (value "470")
      (footprint "eagle-import:0207_10")
      (libsource (lib "eagle-import") (part "R-US_0207/10"))
    )
    (comp (ref "R14")
      (value "1K")
      (footprint "eagle-import:0207_10")
      (libsource (lib "eagle-import") (part "R-US_0207/10"))
    )
    (comp (ref "R16")
      (value "1K")
      (footprint "eagle-import:0207_10")
      (libsource (lib "eagle-import") (part "R-US_0207/10"))
    )
    (comp (ref "R17")
      (value "1K")
      (footprint "eagle-import:0207_10")
      (libsource (lib "eagle-import") (part "R-US_0207/10"))
    )
    (comp (ref "R18")
      (value "10K")
      (footprint "eagle-import:0207_10")
      (libsource (lib "eagle-import") (part "R-US_0207/10"))
    )
    (comp (ref "R19")
      (value "10K")
      (footprint "eagle-import:0207_10")
      (libsource (lib "eagle-import") (part "R-US_0207/10"))
    )
    (comp (ref "E5")
      (value "74LS04N")
      (footprint "eagle-import:DIL14")
      (libsource (lib "eagle-import") (part "7404NLS"))
    )
    (comp (ref "E7")
      (value "74LS04N")
      (footprint "eagle-import:DIL14")
      (libsource (lib "eagle-import") (part "7404NLS"))
    )
    (comp (ref "E11")
      (value "DS8640N")
      (footprint "eagle-import:DIL14")
      (libsource (lib "eagle-import") (part "DS8640N"))
    )
    (comp (ref "E12")
      (value "DS8641N")
      (footprint "eagle-import:DIL16")
      (libsource (lib "eagle-import") (part "DS8641N"))
    )
    (comp (ref "E13")
      (value "DS8641N")
      (footprint "eagle-import:DIL16")
      (libsource (lib "eagle-import") (part "DS8641N"))
    )
    (comp (ref "E14")
      (value "DEC23007C6")
      (footprint "eagle-import:DIL28")
      (libsource (lib "eagle-import") (part "82S100"))
    )
    (comp (ref "E19")
      (value "N8881N")
      (footprint "eagle-import:DIL14")
      (libsource (lib "eagle-import") (part "N8881N"))
    )
    (comp (ref "E25")
      (value "DS8640N")
      (footprint "eagle-import:DIL14")
      (libsource (lib "eagle-import") (part "DS8640N"))
    )
    (comp (ref "E26")
      (value "74LS75N")
      (footprint "eagle-import:DIL16")
      (libsource (lib "eagle-import") (part "7475N"))
    )
    (comp (ref "E27")
      (value "74S11N")
      (footprint "eagle-import:DIL14")
      (libsource (lib "eagle-import") (part "7411NS"))
    )
    (comp (ref "E44")
      (value "74LS04N")
      (footprint "eagle-import:DIL14")
      (libsource (lib "eagle-import") (part "7404NLS"))
    )
    (comp (ref "E45")
      (value "DS8641N")
      (footprint "eagle-import:DIL16")
      (libsource (lib "eagle-import") (part "DS8641N"))
    )
    (comp (ref "E53")
      (value "SP384N")
      (footprint "eagle-import:DIL14")
      (libsource (lib "eagle-import") (part "SP384N"))
    )
    (comp (ref "E71")
      (value "DS8640N")
      (footprint "eagle-import:DIL14")
      (libsource (lib "eagle-import") (part "DS8640N"))
    )
    (comp (ref "R1")
      (value "1K")
      (footprint "eagle-import:0207_10")
      (libsource (lib "eagle-import") (part "R-US_0207/10"))
    )
    (comp (ref "R2")
      (value "1K")
      (footprint "eagle-import:0207_10")
      (libsource (lib "eagle-import") (part "R-US_0207/10"))
    )
    (comp (ref "R6")
      (value "1K")
      (footprint "eagle-import:0207_10")
      (libsource (lib "eagle-import") (part "R-US_0207/10"))
    )
    (comp (ref "R7")
      (value "1K")
      (footprint "eagle-import:0207_10")
      (libsource (lib "eagle-import") (part "R-US_0207/10"))
    )
    (comp (ref "R8")
      (value "1K")
      (footprint "eagle-import:0207_10")
      (libsource (lib "eagle-import") (part "R-US_0207/10"))
    )
    (comp (ref "R9")
      (value "1K")
      (footprint "eagle-import:0207_10")
      (libsource (lib "eagle-import") (part "R-US_0207/10"))
    )
    (comp (ref "R10")
      (value "1K")
      (footprint "eagle-import:0207_10")
      (libsource (lib "eagle-import") (part "R-US_0207/10"))
    )
    (comp (ref "R12")
      (value "1K")
      (footprint "eagle-import:0207_10")
      (libsource (lib "eagle-import") (part "R-US_0207/10"))
    )
    (comp (ref "R24")
      (value "1K")
      (footprint "eagle-import:0207_10")
      (libsource (lib "eagle-import") (part "R-US_0207/10"))
    )
    (comp (ref "R25")
      (value "1K")
      (footprint "eagle-import:0207_10")
      (libsource (lib "eagle-import") (part "R-US_0207/10"))
    )
    (comp (ref "R26")
      (value "1K")
      (footprint "eagle-import:0207_10")
      (libsource (lib "eagle-import") (part "R-US_0207/10"))
    )
    (comp (ref "R27")
      (value "1K")
      (footprint "eagle-import:0207_10")
      (libsource (lib "eagle-import") (part "R-US_0207/10"))
    )
    (comp (ref "R31")
      (value "1K")
      (footprint "eagle-import:0207_10")
      (libsource (lib "eagle-import") (part "R-US_0207/10"))
    )
  )
  (nets
    (net (code "1") (name "+15V") (class "Default")
      (node (ref "U$1") (pin "DA2") (pinfunction "1_DA2") (pintype "bidirectional"))
    )
    (net (code "2") (name "GND") (class "Default")
      (node (ref "C1") (pin "-") (pinfunction "-_-") (pintype "passive"))
      (node (ref "C10") (pin "2") (pinfunction "2_2") (pintype "passive"))
      (node (ref "C11") (pin "2") (pinfunction "2_2") (pintype "passive"))
      (node (ref "C13") (pin "2") (pinfunction "2_2") (pintype "passive"))
      (node (ref "C14") (pin "-") (pinfunction "-_-") (pintype "passive"))
      (node (ref "C15") (pin "2") (pinfunction "2_2") (pintype "passive"))
      (node (ref "C16") (pin "-") (pinfunction "-_-") (pintype "passive"))
      (node (ref "C17") (pin "2") (pinfunction "2_2") (pintype "passive"))
      (node (ref "C18") (pin "2") (pinfunction "2_2") (pintype "passive"))
      (node (ref "C2") (pin "2") (pinfunction "2_2") (pintype "passive"))
      (node (ref "C20") (pin "2") (pinfunction "2_2") (pintype "passive"))
      (node (ref "C21") (pin "2") (pinfunction "2_2") (pintype "passive"))
      (node (ref "C22") (pin "2") (pinfunction "2_2") (pintype "passive"))
      (node (ref "C23") (pin "2") (pinfunction "2_2") (pintype "passive"))
      (node (ref "C24") (pin "-") (pinfunction "-_-") (pintype "passive"))
      (node (ref "C25") (pin "2") (pinfunction "2_2") (pintype "passive"))
      (node (ref "C26") (pin "2") (pinfunction "2_2") (pintype "passive"))
      (node (ref "C27") (pin "2") (pinfunction "2_2") (pintype "passive"))
      (node (ref "C28") (pin "2") (pinfunction "2_2") (pintype "passive"))
      (node (ref "C29") (pin "2") (pinfunction "2_2") (pintype "passive"))
      (node (ref "C3") (pin "2") (pinfunction "2_2") (pintype "passive"))
      (node (ref "C31") (pin "2") (pinfunction "2_2") (pintype "passive"))
      (node (ref "C32") (pin "2") (pinfunction "2_2") (pintype "passive"))
      (node (ref "C33") (pin "2") (pinfunction "2_2") (pintype "passive"))
      (node (ref "C34") (pin "2") (pinfunction "2_2") (pintype "passive"))
      (node (ref "C35") (pin "2") (pinfunction "2_2") (pintype "passive"))
      (node (ref "C36") (pin "2") (pinfunction "2_2") (pintype "passive"))
      (node (ref "C4") (pin "2") (pinfunction "2_2") (pintype "passive"))
      (node (ref "C5") (pin "2") (pinfunction "2_2") (pintype "passive"))
      (node (ref "C6") (pin "2") (pinfunction "2_2") (pintype "passive"))
      (node (ref "C7") (pin "2") (pinfunction "2_2") (pintype "passive"))
      (node (ref "C8") (pin "-") (pinfunction "-_-") (pintype "passive"))
      (node (ref "C9") (pin "2") (pinfunction "2_2") (pintype "passive"))
      (node (ref "E1") (pin "10") (pinfunction "G2_10") (pintype "input"))
      (node (ref "E1") (pin "9") (pinfunction "G1_9") (pintype "input"))
      (node (ref "E101") (pin "8") (pinfunction "-UB_8") (pintype "power_in"))
      (node (ref "E11") (pin "12") (pinfunction "I1_12") (pintype "input"))
      (node (ref "E11") (pin "5") (pinfunction "I1_5") (pintype "input"))
      (node (ref "E11") (pin "6") (pinfunction "I0_6") (pintype "input"))
      (node (ref "E11") (pin "9") (pinfunction "I0_9") (pintype "input"))
      (node (ref "E14") (pin "19") (pinfunction "~{CE}_19") (pintype "input"))
      (node (ref "E14") (pin "6") (pinfunction "I3_6") (pintype "input"))
      (node (ref "E14") (pin "7") (pinfunction "I2_7") (pintype "input"))
      (node (ref "E14") (pin "9") (pinfunction "I0_9") (pintype "input"))
      (node (ref "E25") (pin "12") (pinfunction "I1_12") (pintype "input"))
      (node (ref "E25") (pin "5") (pinfunction "I1_5") (pintype "input"))
      (node (ref "E25") (pin "6") (pinfunction "I0_6") (pintype "input"))
      (node (ref "E25") (pin "9") (pinfunction "I0_9") (pintype "input"))
      (node (ref "E26") (pin "12") (pinfunction "-UB_12") (pintype "power_in"))
      (node (ref "E28") (pin "1") (pinfunction "A6_1") (pintype "input"))
      (node (ref "E28") (pin "2") (pinfunction "A5_2") (pintype "input"))
      (node (ref "E3") (pin "11") (pinfunction "I0_11") (pintype "input"))
      (node (ref "E3") (pin "5") (pinfunction "I1_5") (pintype "input"))
      (node (ref "E3") (pin "6") (pinfunction "I0_6") (pintype "input"))
      (node (ref "E32") (pin "2") (pinfunction "D_2") (pintype "input"))
      (node (ref "E32") (pin "3") (pinfunction "CLK_3") (pintype "input"))
      (node (ref "E41") (pin "5") (pinfunction "I1_5") (pintype "input"))
      (node (ref "E41") (pin "6") (pinfunction "I0_6") (pintype "input"))
      (node (ref "E51") (pin "11") (pinfunction "I0_11") (pintype "input"))
      (node (ref "E51") (pin "6") (pinfunction "I0_6") (pintype "input"))
      (node (ref "E52") (pin "11") (pinfunction "I0_11") (pintype "input"))
      (node (ref "E53") (pin "12") (pinfunction "I1_12") (pintype "input"))
      (node (ref "E53") (pin "4") (pinfunction "I0_4") (pintype "input"))
      (node (ref "E61") (pin "4") (pinfunction "I0_4") (pintype "input"))
      (node (ref "E68") (pin "1") (pinfunction "B3_1") (pintype "input"))
      (node (ref "E68") (pin "12") (pinfunction "A1_12") (pintype "input"))
      (node (ref "E68") (pin "13") (pinfunction "A2_13") (pintype "input"))
      (node (ref "E68") (pin "14") (pinfunction "B2_14") (pintype "input"))
      (node (ref "E68") (pin "15") (pinfunction "A3_15") (pintype "input"))
      (node (ref "E69") (pin "11") (pinfunction "B2_11") (pintype "input"))
      (node (ref "E69") (pin "2") (pinfunction "B0_2") (pintype "input"))
      (node (ref "E69") (pin "5") (pinfunction "B1_5") (pintype "input"))
      (node (ref "E69") (pin "7") (pinfunction "S1_7") (pintype "input"))
      (node (ref "E71") (pin "12") (pinfunction "I1_12") (pintype "input"))
      (node (ref "E71") (pin "5") (pinfunction "I1_5") (pintype "input"))
      (node (ref "E71") (pin "6") (pinfunction "I0_6") (pintype "input"))
      (node (ref "E71") (pin "9") (pinfunction "I0_9") (pintype "input"))
      (node (ref "E72") (pin "4") (pinfunction "I0_4") (pintype "input"))
      (node (ref "E72") (pin "6") (pinfunction "I0_6") (pintype "input"))
      (node (ref "E73") (pin "10") (pinfunction "G2_10") (pintype "input"))
      (node (ref "E73") (pin "9") (pinfunction "G1_9") (pintype "input"))
      (node (ref "E76") (pin "2") (pinfunction "D_2") (pintype "input"))
      (node (ref "E77") (pin "2") (pinfunction "D_2") (pintype "input"))
      (node (ref "E77") (pin "3") (pinfunction "CLK_3") (pintype "input"))
      (node (ref "E78") (pin "2") (pinfunction "A<B_I_2") (pintype "input"))
      (node (ref "E78") (pin "4") (pinfunction "A>B_I_4") (pintype "input"))
      (node (ref "E79") (pin "7") (pinfunction "S1_7") (pintype "input"))
      (node (ref "E80") (pin "15") (pinfunction "~{G}_15") (pintype "input"))
      (node (ref "E83") (pin "8") (pinfunction "-UB_8") (pintype "power_in"))
      (node (ref "E87") (pin "1") (pinfunction "A6_1") (pintype "input"))
      (node (ref "E87") (pin "13") (pinfunction "~{G1}_13") (pintype "input"))
      (node (ref "E87") (pin "14") (pinfunction "~{G2}_14") (pintype "input"))
      (node (ref "Q1") (pin "1") (pinfunction "E_1") (pintype "passive"))
      (node (ref "U$1") (pin "AC1") (pinfunction "1_AC1") (pintype "bidirectional"))
      (node (ref "U$1") (pin "AC2") (pinfunction "1_AC2") (pintype "bidirectional"))
      (node (ref "U$1") (pin "AF1") (pinfunction "1_AF1") (pintype "bidirectional"))
      (node (ref "U$1") (pin "AF2") (pinfunction "1_AF2") (pintype "bidirectional"))
      (node (ref "U$1") (pin "AN1") (pinfunction "1_AN1") (pintype "bidirectional"))
      (node (ref "U$1") (pin "AN2") (pinfunction "1_AN2") (pintype "bidirectional"))
      (node (ref "U$1") (pin "AT1") (pinfunction "1_AT1") (pintype "bidirectional"))
      (node (ref "U$1") (pin "AT2") (pinfunction "1_AT2") (pintype "bidirectional"))
      (node (ref "U$1") (pin "BC1") (pinfunction "1_BC1") (pintype "bidirectional"))
      (node (ref "U$1") (pin "BC2") (pinfunction "1_BC2") (pintype "bidirectional"))
      (node (ref "U$1") (pin "BF1") (pinfunction "1_BF1") (pintype "bidirectional"))
      (node (ref "U$1") (pin "BF2") (pinfunction "1_BF2") (pintype "bidirectional"))
      (node (ref "U$1") (pin "BN1") (pinfunction "1_BN1") (pintype "bidirectional"))
      (node (ref "U$1") (pin "BN2") (pinfunction "1_BN2") (pintype "bidirectional"))
      (node (ref "U$1") (pin "BT1") (pinfunction "1_BT1") (pintype "bidirectional"))
      (node (ref "U$1") (pin "BT2") (pinfunction "1_BT2") (pintype "bidirectional"))
      (node (ref "U$1") (pin "CC1") (pinfunction "1_CC1") (pintype "bidirectional"))
      (node (ref "U$1") (pin "CC2") (pinfunction "1_CC2") (pintype "bidirectional"))
      (node (ref "U$1") (pin "CF1") (pinfunction "1_CF1") (pintype "bidirectional"))
      (node (ref "U$1") (pin "CF2") (pinfunction "1_CF2") (pintype "bidirectional"))
      (node (ref "U$1") (pin "CN1") (pinfunction "1_CN1") (pintype "bidirectional"))
      (node (ref "U$1") (pin "CN2") (pinfunction "1_CN2") (pintype "bidirectional"))
      (node (ref "U$1") (pin "CT1") (pinfunction "1_CT1") (pintype "bidirectional"))
      (node (ref "U$1") (pin "CT2") (pinfunction "1_CT2") (pintype "bidirectional"))
      (node (ref "U$1") (pin "DC1") (pinfunction "1_DC1") (pintype "bidirectional"))
      (node (ref "U$1") (pin "DC2") (pinfunction "1_DC2") (pintype "bidirectional"))
      (node (ref "U$1") (pin "DF1") (pinfunction "1_DF1") (pintype "bidirectional"))
      (node (ref "U$1") (pin "DF2") (pinfunction "1_DF2") (pintype "bidirectional"))
      (node (ref "U$1") (pin "DN1") (pinfunction "1_DN1") (pintype "bidirectional"))
      (node (ref "U$1") (pin "DN2") (pinfunction "1_DN2") (pintype "bidirectional"))
      (node (ref "U$1") (pin "DT1") (pinfunction "1_DT1") (pintype "bidirectional"))
      (node (ref "U$1") (pin "DT2") (pinfunction "1_DT2") (pintype "bidirectional"))
    )
    (net (code "3") (name "INITIALIZE") (class "Default")
      (node (ref "E53") (pin "11") (pinfunction "I0_11") (pintype "input"))
      (node (ref "U$1") (pin "CR1") (pinfunction "1_CR1") (pintype "bidirectional"))
    )
    (net (code "4") (name "INTERNAL_IO") (class "Default")
      (node (ref "E42") (pin "10") (pinfunction "O_10") (pintype "open_collector"))
      (node (ref "U$1") (pin "CL1") (pinfunction "1_CL1") (pintype "bidirectional"))
    )
    (net (code "5") (name "MAMS_LD_CTL") (class "Default")
      (node (ref "E3") (pin "4") (pinfunction "I0_4") (pintype "input"))
      (node (ref "U$1") (pin "BH2") (pinfunction "1_BH2") (pintype "bidirectional"))
    )
    (net (code "6") (name "Net-(E1A-D2)") (class "Default")
      (node (ref "E1") (pin "13") (pinfunction "D2_13") (pintype "input"))
      (node (ref "E2") (pin "6") (pinfunction "O_6") (pintype "output"))
    )
    (net (code "7") (name "Net-(E1A-D3)") (class "Default")
      (node (ref "E1") (pin "12") (pinfunction "D3_12") (pintype "input"))
      (node (ref "E2") (pin "4") (pinfunction "O_4") (pintype "output"))
    )
    (net (code "8") (name "Net-(E1A-D4)") (class "Default")
      (node (ref "E1") (pin "11") (pinfunction "D4_11") (pintype "input"))
      (node (ref "E2") (pin "2") (pinfunction "O_2") (pintype "output"))
    )
    (net (code "9") (name "Net-(E2D-I)") (class "Default")
      (node (ref "E2") (pin "9") (pinfunction "I_9") (pintype "input"))
      (node (ref "E33") (pin "6") (pinfunction "O_6") (pintype "output"))
    )
    (net (code "10") (name "Net-(E2D-O)") (class "Default")
      (node (ref "E2") (pin "8") (pinfunction "O_8") (pintype "output"))
      (node (ref "E32") (pin "12") (pinfunction "D_12") (pintype "input"))
    )
    (net (code "11") (name "Net-(E3D-O)") (class "Default")
      (node (ref "E3") (pin "13") (pinfunction "O_13") (pintype "output"))
      (node (ref "E4") (pin "8") (pinfunction "I0_8") (pintype "input"))
    )
    (net (code "12") (name "Net-(E4C-I1)") (class "Default")
      (node (ref "E4") (pin "9") (pinfunction "I1_9") (pintype "input"))
      (node (ref "E6") (pin "11") (pinfunction "O_11") (pintype "output"))
    )
    (net (code "13") (name "Net-(E12A-D0)") (class "Default")
      (node (ref "E12") (pin "7") (pinfunction "D0_7") (pintype "input"))
      (node (ref "E12") (pin "9") (pinfunction "D1_9") (pintype "input"))
      (node (ref "E13") (pin "7") (pinfunction "D0_7") (pintype "input"))
      (node (ref "E13") (pin "9") (pinfunction "D1_9") (pintype "input"))
      (node (ref "E20") (pin "13") (pinfunction "O_13") (pintype "open_collector"))
      (node (ref "E20") (pin "4") (pinfunction "O_4") (pintype "open_collector"))
      (node (ref "E45") (pin "7") (pinfunction "D0_7") (pintype "input"))
      (node (ref "E45") (pin "9") (pinfunction "D1_9") (pintype "input"))
      (node (ref "R10") (pin "1") (pinfunction "1_1") (pintype "passive"))
    )
    (net (code "14") (name "Net-(E12A-O0)") (class "Default")
      (node (ref "E12") (pin "14") (pinfunction "O0_14") (pintype "input"))
      (node (ref "E5") (pin "8") (pinfunction "O_8") (pintype "output"))
    )
    (net (code "15") (name "Net-(E12A-O1)") (class "Default")
      (node (ref "E12") (pin "11") (pinfunction "O1_11") (pintype "input"))
      (node (ref "E5") (pin "6") (pinfunction "O_6") (pintype "output"))
    )
    (net (code "16") (name "Net-(E12A-O2)") (class "Default")
      (node (ref "E12") (pin "2") (pinfunction "O2_2") (pintype "input"))
      (node (ref "E5") (pin "4") (pinfunction "O_4") (pintype "output"))
    )
    (net (code "17") (name "Net-(E12A-O3)") (class "Default")
      (node (ref "E12") (pin "5") (pinfunction "O3_5") (pintype "input"))
      (node (ref "E5") (pin "2") (pinfunction "O_2") (pintype "output"))
    )
    (net (code "18") (name "Net-(E13A-O0)") (class "Default")
      (node (ref "E13") (pin "14") (pinfunction "O0_14") (pintype "input"))
      (node (ref "E7") (pin "8") (pinfunction "O_8") (pintype "output"))
    )
    (net (code "19") (name "Net-(E13A-O1)") (class "Default")
      (node (ref "E13") (pin "11") (pinfunction "O1_11") (pintype "input"))
      (node (ref "E7") (pin "6") (pinfunction "O_6") (pintype "output"))
    )
    (net (code "20") (name "Net-(E13A-O2)") (class "Default")
      (node (ref "E13") (pin "2") (pinfunction "O2_2") (pintype "input"))
      (node (ref "E7") (pin "4") (pinfunction "O_4") (pintype "output"))
    )
    (net (code "21") (name "Net-(E13A-O3)") (class "Default")
      (node (ref "E13") (pin "5") (pinfunction "O3_5") (pintype "input"))
      (node (ref "E7") (pin "2") (pinfunction "O_2") (pintype "output"))
    )
    (net (code "22") (name "Net-(E14A-I15)") (class "Default")
      (node (ref "E14") (pin "20") (pinfunction "I15_20") (pintype "input"))
      (node (ref "E21") (pin "12") (pinfunction "O_12") (pintype "output"))
    )
    (net (code "23") (name "Net-(E14A-O0)") (class "Default")
      (node (ref "E14") (pin "18") (pinfunction "O0_18") (pintype "tri_state"))
      (node (ref "E20") (pin "11") (pinfunction "I0_11") (pintype "input"))
    )
    (net (code "24") (name "Net-(E14A-O1)") (class "Default")
      (node (ref "E14") (pin "17") (pinfunction "O1_17") (pintype "tri_state"))
      (node (ref "E19") (pin "8") (pinfunction "I0_8") (pintype "input"))
      (node (ref "E19") (pin "9") (pinfunction "I1_9") (pintype "input"))
    )
    (net (code "25") (name "Net-(E14A-O2)") (class "Default")
      (node (ref "E14") (pin "16") (pinfunction "O2_16") (pintype "tri_state"))
      (node (ref "E19") (pin "11") (pinfunction "I0_11") (pintype "input"))
      (node (ref "E19") (pin "12") (pinfunction "I1_12") (pintype "input"))
    )
    (net (code "26") (name "Net-(E18A-O)") (class "Default")
      (node (ref "E18") (pin "3") (pinfunction "O_3") (pintype "output"))
      (node (ref "E56") (pin "9") (pinfunction "I0_9") (pintype "input"))
    )
    (net (code "27") (name "Net-(E18B-I1)") (class "Default")
      (node (ref "E18") (pin "5") (pinfunction "I1_5") (pintype "input"))
      (node (ref "E22") (pin "10") (pinfunction "O_10") (pintype "output"))
    )
    (net (code "28") (name "Net-(E18B-O)") (class "Default")
      (node (ref "E18") (pin "6") (pinfunction "O_6") (pintype "output"))
      (node (ref "E33") (pin "10") (pinfunction "I1_10") (pintype "input"))
      (node (ref "E56") (pin "10") (pinfunction "I1_10") (pintype "input"))
    )
    (net (code "29") (name "Net-(E18D-O)") (class "Default")
      (node (ref "E18") (pin "11") (pinfunction "O_11") (pintype "output"))
      (node (ref "E8") (pin "12") (pinfunction "I1_12") (pintype "input"))
    )
    (net (code "30") (name "Net-(E21C-O)") (class "Default")
      (node (ref "E21") (pin "8") (pinfunction "O_8") (pintype "output"))
      (node (ref "E28") (pin "15") (pinfunction "A7_15") (pintype "input"))
    )
    (net (code "31") (name "Net-(E22F-O)") (class "Default")
      (node (ref "E22") (pin "12") (pinfunction "O_12") (pintype "output"))
      (node (ref "E42") (pin "6") (pinfunction "I1_6") (pintype "input"))
    )
    (net (code "32") (name "Net-(E24A-I0)") (class "Default")
      (node (ref "E24") (pin "1") (pinfunction "I0_1") (pintype "input"))
      (node (ref "E30") (pin "8") (pinfunction "O_8") (pintype "output"))
    )
    (net (code "33") (name "Net-(E24A-I2)") (class "Default")
      (node (ref "E24") (pin "13") (pinfunction "I2_13") (pintype "input"))
      (node (ref "E49") (pin "8") (pinfunction "O_8") (pintype "output"))
      (node (ref "E57") (pin "2") (pinfunction "I1_2") (pintype "input"))
      (node (ref "E67") (pin "9") (pinfunction "I0_9") (pintype "input"))
    )
    (net (code "34") (name "Net-(E24A-O)") (class "Default")
      (node (ref "E24") (pin "12") (pinfunction "O_12") (pintype "output"))
      (node (ref "E39") (pin "5") (pinfunction "I_5") (pintype "input"))
      (node (ref "E42") (pin "2") (pinfunction "I0_2") (pintype "input"))
      (node (ref "E42") (pin "3") (pinfunction "I1_3") (pintype "input"))
    )
    (net (code "35") (name "Net-(E24B-I0)") (class "Default")
      (node (ref "E24") (pin "3") (pinfunction "I0_3") (pintype "input"))
      (node (ref "E39") (pin "6") (pinfunction "O_6") (pintype "output"))
    )
    (net (code "36") (name "Net-(E24B-O)") (class "Default")
      (node (ref "E24") (pin "6") (pinfunction "O_6") (pintype "output"))
      (node (ref "E33") (pin "4") (pinfunction "I0_4") (pintype "input"))
    )
    (net (code "37") (name "Net-(E24C-I0)") (class "Default")
      (node (ref "E24") (pin "10") (pinfunction "I1_10") (pintype "input"))
      (node (ref "E24") (pin "9") (pinfunction "I0_9") (pintype "input"))
      (node (ref "E39") (pin "8") (pinfunction "O_8") (pintype "output"))
    )
    (net (code "38") (name "Net-(E24C-O)") (class "Default")
      (node (ref "E24") (pin "8") (pinfunction "O_8") (pintype "output"))
      (node (ref "E42") (pin "8") (pinfunction "I0_8") (pintype "input"))
      (node (ref "E42") (pin "9") (pinfunction "I1_9") (pintype "input"))
    )
    (net (code "39") (name "Net-(E26D-1D)") (class "Default")
      (node (ref "E26") (pin "2") (pinfunction "1D_2") (pintype "input"))
      (node (ref "E41") (pin "3") (pinfunction "O_3") (pintype "output"))
    )
    (net (code "40") (name "Net-(E28A-O1)") (class "Default")
      (node (ref "E28") (pin "11") (pinfunction "O1_11") (pintype "tri_state"))
      (node (ref "R3") (pin "1") (pinfunction "1_1") (pintype "passive"))
    )
    (net (code "41") (name "Net-(E29A-O)") (class "Default")
      (node (ref "E29") (pin "1") (pinfunction "O_1") (pintype "output"))
      (node (ref "E49") (pin "3") (pinfunction "I0_3") (pintype "input"))
    )
    (net (code "42") (name "Net-(E29B-I1)") (class "Default")
      (node (ref "E29") (pin "6") (pinfunction "I1_6") (pintype "input"))
      (node (ref "E3") (pin "3") (pinfunction "O_3") (pintype "output"))
      (node (ref "E75") (pin "6") (pinfunction "I0_6") (pintype "input"))
    )
    (net (code "43") (name "Net-(E29D-O)") (class "Default")
      (node (ref "E29") (pin "13") (pinfunction "O_13") (pintype "output"))
      (node (ref "E88") (pin "9") (pinfunction "CLK_9") (pintype "input"))
    )
    (net (code "44") (name "Net-(E31A-G2)") (class "Default")
      (node (ref "E31") (pin "19") (pinfunction "G2_19") (pintype "input"))
      (node (ref "E47") (pin "3") (pinfunction "I1_3") (pintype "input"))
      (node (ref "E47") (pin "4") (pinfunction "O_4") (pintype "output"))
    )
    (net (code "45") (name "Net-(E32A-~{Q})") (class "Default")
      (node (ref "E32") (pin "6") (pinfunction "~{Q}_6") (pintype "output"))
      (node (ref "E8") (pin "11") (pinfunction "I0_11") (pintype "input"))
    )
    (net (code "46") (name "Net-(E32B-CLR)") (class "Default")
      (node (ref "E32") (pin "13") (pinfunction "CLR_13") (pintype "input"))
      (node (ref "R4") (pin "1") (pinfunction "1_1") (pintype "passive"))
    )
    (net (code "47") (name "Net-(E33C-I0)") (class "Default")
      (node (ref "E33") (pin "9") (pinfunction "I0_9") (pintype "input"))
      (node (ref "E56") (pin "11") (pinfunction "I2_11") (pintype "input"))
      (node (ref "E58") (pin "12") (pinfunction "O_12") (pintype "output"))
      (node (ref "E76") (pin "10") (pinfunction "PRE_10") (pintype "input"))
    )
    (net (code "48") (name "Net-(E38C-O)") (class "Default")
      (node (ref "E38") (pin "8") (pinfunction "O_8") (pintype "output"))
      (node (ref "E48") (pin "12") (pinfunction "I1_12") (pintype "input"))
    )
    (net (code "49") (name "Net-(E39A-O)") (class "Default")
      (node (ref "E39") (pin "2") (pinfunction "O_2") (pintype "output"))
      (node (ref "E50") (pin "2") (pinfunction "I1_2") (pintype "input"))
    )
    (net (code "50") (name "Net-(E39B-O)") (class "Default")
      (node (ref "E39") (pin "4") (pinfunction "O_4") (pintype "output"))
      (node (ref "E50") (pin "13") (pinfunction "I1_13") (pintype "input"))
    )
    (net (code "51") (name "Net-(E39D-I)") (class "Default")
      (node (ref "E39") (pin "9") (pinfunction "I_9") (pintype "input"))
      (node (ref "E47") (pin "1") (pinfunction "O_1") (pintype "output"))
    )
    (net (code "52") (name "Net-(E39F-I)") (class "Default")
      (node (ref "E39") (pin "13") (pinfunction "I_13") (pintype "input"))
      (node (ref "E48") (pin "10") (pinfunction "O_10") (pintype "output"))
    )
    (net (code "53") (name "Net-(E41B-O)") (class "Default")
      (node (ref "E41") (pin "12") (pinfunction "I1_12") (pintype "input"))
      (node (ref "E41") (pin "2") (pinfunction "O_2") (pintype "output"))
    )
    (net (code "54") (name "Net-(E41C-O)") (class "Default")
      (node (ref "E41") (pin "14") (pinfunction "O_14") (pintype "output"))
      (node (ref "E66") (pin "5") (pinfunction "I1_5") (pintype "input"))
    )
    (net (code "55") (name "Net-(E44A-O)") (class "Default")
      (node (ref "E44") (pin "2") (pinfunction "O_2") (pintype "output"))
      (node (ref "E45") (pin "5") (pinfunction "O3_5") (pintype "input"))
    )
    (net (code "56") (name "Net-(E44B-O)") (class "Default")
      (node (ref "E44") (pin "4") (pinfunction "O_4") (pintype "output"))
      (node (ref "E45") (pin "2") (pinfunction "O2_2") (pintype "input"))
    )
    (net (code "57") (name "Net-(E44C-O)") (class "Default")
      (node (ref "E44") (pin "6") (pinfunction "O_6") (pintype "output"))
      (node (ref "E45") (pin "11") (pinfunction "O1_11") (pintype "input"))
    )
    (net (code "58") (name "Net-(E44D-O)") (class "Default")
      (node (ref "E44") (pin "8") (pinfunction "O_8") (pintype "output"))
      (node (ref "E45") (pin "14") (pinfunction "O0_14") (pintype "input"))
    )
    (net (code "59") (name "Net-(E47B-I1)") (class "Default")
      (node (ref "E47") (pin "10") (pinfunction "O_10") (pintype "output"))
      (node (ref "E47") (pin "6") (pinfunction "I1_6") (pintype "input"))
    )
    (net (code "60") (name "Net-(E47D-O)") (class "Default")
      (node (ref "E47") (pin "13") (pinfunction "O_13") (pintype "output"))
      (node (ref "E85") (pin "9") (pinfunction "CLK_9") (pintype "input"))
    )
    (net (code "61") (name "Net-(E48C-I0)") (class "Default")
      (node (ref "E48") (pin "8") (pinfunction "I0_8") (pintype "input"))
      (node (ref "E68") (pin "6") (pinfunction "A=B_O_6") (pintype "output"))
    )
    (net (code "62") (name "Net-(E48C-I1)") (class "Default")
      (node (ref "E48") (pin "9") (pinfunction "I1_9") (pintype "input"))
      (node (ref "E68") (pin "5") (pinfunction "A>B_O_5") (pintype "output"))
    )
    (net (code "63") (name "Net-(E48D-O)") (class "Default")
      (node (ref "E48") (pin "13") (pinfunction "O_13") (pintype "output"))
      (node (ref "E96") (pin "1") (pinfunction "1G_1") (pintype "input"))
      (node (ref "E96") (pin "15") (pinfunction "2G_15") (pintype "input"))
    )
    (net (code "64") (name "Net-(E49A-I0)") (class "Default")
      (node (ref "E49") (pin "1") (pinfunction "I0_1") (pintype "input"))
      (node (ref "E57") (pin "8") (pinfunction "O_8") (pintype "output"))
      (node (ref "E58") (pin "3") (pinfunction "I_3") (pintype "input"))
    )
    (net (code "65") (name "Net-(E49A-O)") (class "Default")
      (node (ref "E49") (pin "12") (pinfunction "O_12") (pintype "output"))
      (node (ref "E58") (pin "13") (pinfunction "I_13") (pintype "input"))
      (node (ref "E69") (pin "14") (pinfunction "B3_14") (pintype "input"))
      (node (ref "E79") (pin "11") (pinfunction "B2_11") (pintype "input"))
      (node (ref "E79") (pin "14") (pinfunction "B3_14") (pintype "input"))
      (node (ref "E79") (pin "2") (pinfunction "B0_2") (pintype "input"))
      (node (ref "E79") (pin "5") (pinfunction "B1_5") (pintype "input"))
    )
    (net (code "66") (name "Net-(E49B-O)") (class "Default")
      (node (ref "E49") (pin "6") (pinfunction "O_6") (pintype "output"))
      (node (ref "E70") (pin "5") (pinfunction "I1_5") (pintype "input"))
    )
    (net (code "67") (name "Net-(E49C-I1)") (class "Default")
      (node (ref "E49") (pin "10") (pinfunction "I1_10") (pintype "input"))
      (node (ref "E70") (pin "8") (pinfunction "O_8") (pintype "output"))
    )
    (net (code "68") (name "Net-(E50A-I0)") (class "Default")
      (node (ref "E50") (pin "1") (pinfunction "I0_1") (pintype "input"))
      (node (ref "E59") (pin "6") (pinfunction "~{Q}_6") (pintype "output"))
      (node (ref "E8") (pin "8") (pinfunction "I0_8") (pintype "input"))
    )
    (net (code "69") (name "Net-(E50A-O)") (class "Default")
      (node (ref "E50") (pin "3") (pinfunction "O_3") (pintype "output"))
      (node (ref "E50") (pin "4") (pinfunction "I0_4") (pintype "input"))
    )
    (net (code "70") (name "Net-(E50B-I1)") (class "Default")
      (node (ref "E50") (pin "5") (pinfunction "I1_5") (pintype "input"))
      (node (ref "E50") (pin "8") (pinfunction "O_8") (pintype "output"))
    )
    (net (code "71") (name "Net-(E50B-O)") (class "Default")
      (node (ref "E50") (pin "6") (pinfunction "O_6") (pintype "output"))
      (node (ref "E60") (pin "2") (pinfunction "D_2") (pintype "input"))
    )
    (net (code "72") (name "Net-(E50D-O)") (class "Default")
      (node (ref "E50") (pin "11") (pinfunction "O_11") (pintype "output"))
      (node (ref "E60") (pin "4") (pinfunction "PRE_4") (pintype "input"))
    )
    (net (code "73") (name "Net-(E56C-O)") (class "Default")
      (node (ref "E56") (pin "8") (pinfunction "O_8") (pintype "output"))
      (node (ref "E58") (pin "5") (pinfunction "I_5") (pintype "input"))
    )
    (net (code "74") (name "Net-(E57A-I0)") (class "Default")
      (node (ref "E57") (pin "1") (pinfunction "I0_1") (pintype "input"))
      (node (ref "E69") (pin "3") (pinfunction "F0_3") (pintype "output"))
    )
    (net (code "75") (name "Net-(E57A-O)") (class "Default")
      (node (ref "E57") (pin "3") (pinfunction "O_3") (pintype "output"))
      (node (ref "E77") (pin "4") (pinfunction "PRE_4") (pintype "input"))
    )
    (net (code "76") (name "Net-(E58C-O)") (class "Default")
      (node (ref "E58") (pin "6") (pinfunction "O_6") (pintype "output"))
      (node (ref "E77") (pin "1") (pinfunction "CLR_1") (pintype "input"))
    )
    (net (code "77") (name "Net-(E58D-O)") (class "Default")
      (node (ref "E58") (pin "8") (pinfunction "O_8") (pintype "output"))
      (node (ref "E66") (pin "2") (pinfunction "I1_2") (pintype "input"))
    )
    (net (code "78") (name "Net-(E59A-CLR)") (class "Default")
      (node (ref "E59") (pin "1") (pinfunction "CLR_1") (pintype "input"))
      (node (ref "E59") (pin "13") (pinfunction "CLR_13") (pintype "input"))
      (node (ref "E59") (pin "4") (pinfunction "PRE_4") (pintype "input"))
      (node (ref "R13") (pin "1") (pinfunction "1_1") (pintype "passive"))
    )
    (net (code "79") (name "Net-(E59B-D)") (class "Default")
      (node (ref "E59") (pin "12") (pinfunction "D_12") (pintype "input"))
      (node (ref "E60") (pin "6") (pinfunction "~{Q}_6") (pintype "output"))
    )
    (net (code "80") (name "Net-(E61A-O)") (class "Default")
      (node (ref "E61") (pin "3") (pinfunction "O_3") (pintype "output"))
      (node (ref "E61") (pin "6") (pinfunction "I0_6") (pintype "input"))
    )
    (net (code "81") (name "Net-(E63A-D)") (class "Default")
      (node (ref "E63") (pin "10") (pinfunction "PRE_10") (pintype "input"))
      (node (ref "E63") (pin "2") (pinfunction "D_2") (pintype "input"))
      (node (ref "R15") (pin "1") (pinfunction "1_1") (pintype "passive"))
    )
    (net (code "82") (name "Net-(E64A-O)") (class "Default")
      (node (ref "E64") (pin "1") (pinfunction "O_1") (pintype "output"))
      (node (ref "E64") (pin "6") (pinfunction "I1_6") (pintype "input"))
    )
    (net (code "83") (name "Net-(E64B-O)") (class "Default")
      (node (ref "C12") (pin "1") (pinfunction "1_1") (pintype "passive"))
      (node (ref "E64") (pin "4") (pinfunction "O_4") (pintype "output"))
      (node (ref "R5") (pin "1") (pinfunction "1_1") (pintype "passive"))
    )
    (net (code "84") (name "Net-(E66A-O)") (class "Default")
      (node (ref "E66") (pin "3") (pinfunction "O_3") (pintype "output"))
      (node (ref "E67") (pin "12") (pinfunction "I0_12") (pintype "input"))
    )
    (net (code "85") (name "Net-(E66B-O)") (class "Default")
      (node (ref "E66") (pin "6") (pinfunction "O_6") (pintype "output"))
      (node (ref "E76") (pin "4") (pinfunction "PRE_4") (pintype "input"))
      (node (ref "PAD3") (pin "1") (pinfunction "P_1") (pintype "passive"))
    )
    (net (code "86") (name "Net-(E66D-I1)") (class "Default")
      (node (ref "E66") (pin "13") (pinfunction "I1_13") (pintype "input"))
      (node (ref "E75") (pin "2") (pinfunction "O_2") (pintype "output"))
    )
    (net (code "87") (name "Net-(E66D-O)") (class "Default")
      (node (ref "E66") (pin "11") (pinfunction "O_11") (pintype "output"))
      (node (ref "E67") (pin "13") (pinfunction "I1_13") (pintype "input"))
    )
    (net (code "88") (name "Net-(E67A-I0)") (class "Default")
      (node (ref "E67") (pin "1") (pinfunction "I0_1") (pintype "input"))
      (node (ref "E80") (pin "1") (pinfunction "O0_1") (pintype "tri_state"))
    )
    (net (code "89") (name "Net-(E67A-O)") (class "Default")
      (node (ref "E67") (pin "3") (pinfunction "O_3") (pintype "output"))
      (node (ref "E69") (pin "1") (pinfunction "A0_1") (pintype "input"))
    )
    (net (code "90") (name "Net-(E67C-O)") (class "Default")
      (node (ref "E67") (pin "8") (pinfunction "O_8") (pintype "output"))
      (node (ref "E69") (pin "9") (pinfunction "S0_9") (pintype "input"))
      (node (ref "E79") (pin "9") (pinfunction "S0_9") (pintype "input"))
    )
    (net (code "91") (name "Net-(E67D-O)") (class "Default")
      (node (ref "E67") (pin "11") (pinfunction "O_11") (pintype "output"))
      (node (ref "E76") (pin "12") (pinfunction "D_12") (pintype "input"))
    )
    (net (code "92") (name "Net-(E68A-A<B_I)") (class "Default")
      (node (ref "E68") (pin "2") (pinfunction "A<B_I_2") (pintype "input"))
      (node (ref "E78") (pin "7") (pinfunction "A<B_O_7") (pintype "output"))
    )
    (net (code "93") (name "Net-(E68A-A=B_I)") (class "Default")
      (node (ref "E68") (pin "3") (pinfunction "A=B_I_3") (pintype "input"))
      (node (ref "E78") (pin "6") (pinfunction "A=B_O_6") (pintype "output"))
    )
    (net (code "94") (name "Net-(E68A-A>B_I)") (class "Default")
      (node (ref "E68") (pin "4") (pinfunction "A>B_I_4") (pintype "input"))
      (node (ref "E78") (pin "5") (pinfunction "A>B_O_5") (pintype "output"))
    )
    (net (code "95") (name "Net-(E69A-A1)") (class "Default")
      (node (ref "E69") (pin "6") (pinfunction "A1_6") (pintype "input"))
      (node (ref "E80") (pin "2") (pinfunction "O1_2") (pintype "tri_state"))
    )
    (net (code "96") (name "Net-(E69A-A2)") (class "Default")
      (node (ref "E69") (pin "10") (pinfunction "A2_10") (pintype "input"))
      (node (ref "E80") (pin "3") (pinfunction "O2_3") (pintype "tri_state"))
    )
    (net (code "97") (name "Net-(E69A-A3)") (class "Default")
      (node (ref "E69") (pin "15") (pinfunction "A3_15") (pintype "input"))
      (node (ref "E80") (pin "4") (pinfunction "O3_4") (pintype "tri_state"))
    )
    (net (code "98") (name "Net-(E70A-O)") (class "Default")
      (node (ref "E70") (pin "3") (pinfunction "O_3") (pintype "output"))
      (node (ref "E70") (pin "4") (pinfunction "I0_4") (pintype "input"))
    )
    (net (code "99") (name "Net-(E70D-O)") (class "Default")
      (node (ref "E70") (pin "11") (pinfunction "O_11") (pintype "output"))
      (node (ref "E80") (pin "13") (pinfunction "A3_13") (pintype "input"))
    )
    (net (code "100") (name "Net-(E72A-O)") (class "Default")
      (node (ref "E72") (pin "3") (pinfunction "O_3") (pintype "output"))
      (node (ref "E92") (pin "9") (pinfunction "I0_9") (pintype "input"))
    )
    (net (code "101") (name "Net-(E76B-CLR)") (class "Default")
      (node (ref "E76") (pin "13") (pinfunction "CLR_13") (pintype "input"))
      (node (ref "R19") (pin "1") (pinfunction "1_1") (pintype "passive"))
    )
    (net (code "102") (name "Net-(E79A-A0)") (class "Default")
      (node (ref "E79") (pin "1") (pinfunction "A0_1") (pintype "input"))
      (node (ref "E80") (pin "5") (pinfunction "O4_5") (pintype "tri_state"))
    )
    (net (code "103") (name "Net-(E79A-A1)") (class "Default")
      (node (ref "E79") (pin "6") (pinfunction "A1_6") (pintype "input"))
      (node (ref "E80") (pin "6") (pinfunction "O5_6") (pintype "tri_state"))
    )
    (net (code "104") (name "Net-(E79A-A2)") (class "Default")
      (node (ref "E79") (pin "10") (pinfunction "A2_10") (pintype "input"))
      (node (ref "E80") (pin "7") (pinfunction "O6_7") (pintype "tri_state"))
    )
    (net (code "105") (name "Net-(E79A-A3)") (class "Default")
      (node (ref "E79") (pin "15") (pinfunction "A3_15") (pintype "input"))
      (node (ref "E80") (pin "9") (pinfunction "O7_9") (pintype "tri_state"))
    )
    (net (code "106") (name "Net-(E83C-~{G})") (class "Default")
      (node (ref "E83") (pin "15") (pinfunction "~{G}_15") (pintype "input"))
      (node (ref "E92") (pin "8") (pinfunction "O_8") (pintype "output"))
    )
    (net (code "107") (name "Net-(E84A-1G)") (class "Default")
      (node (ref "E84") (pin "1") (pinfunction "1G_1") (pintype "input"))
      (node (ref "E92") (pin "12") (pinfunction "O_12") (pintype "output"))
    )
    (net (code "108") (name "Net-(E102A-D2)") (class "Default")
      (node (ref "E102") (pin "5") (pinfunction "D2_5") (pintype "input"))
      (node (ref "E104") (pin "7") (pinfunction "1Y3_7") (pintype "tri_state"))
      (node (ref "E107") (pin "13") (pinfunction "2Y2_13") (pintype "tri_state"))
      (node (ref "E73") (pin "11") (pinfunction "D4_11") (pintype "input"))
      (node (ref "E84") (pin "3") (pinfunction "1Y1_3") (pintype "tri_state"))
      (node (ref "E95") (pin "13") (pinfunction "2Y2_13") (pintype "tri_state"))
      (node (ref "E96") (pin "13") (pinfunction "2Y2_13") (pintype "tri_state"))
      (node (ref "R28") (pin "1") (pinfunction "1_1") (pintype "passive"))
    )
    (net (code "109") (name "Net-(E102A-D3)") (class "Default")
      (node (ref "E102") (pin "12") (pinfunction "D3_12") (pintype "input"))
      (node (ref "E104") (pin "5") (pinfunction "1Y2_5") (pintype "tri_state"))
      (node (ref "E107") (pin "11") (pinfunction "2Y1_11") (pintype "tri_state"))
      (node (ref "E73") (pin "12") (pinfunction "D3_12") (pintype "input"))
      (node (ref "E84") (pin "5") (pinfunction "1Y2_5") (pintype "tri_state"))
      (node (ref "E95") (pin "11") (pinfunction "2Y1_11") (pintype "tri_state"))
      (node (ref "E96") (pin "11") (pinfunction "2Y1_11") (pintype "tri_state"))
      (node (ref "R32") (pin "1") (pinfunction "1_1") (pintype "passive"))
    )
    (net (code "110") (name "Net-(E102A-D4)") (class "Default")
      (node (ref "E102") (pin "13") (pinfunction "D4_13") (pintype "input"))
      (node (ref "E104") (pin "3") (pinfunction "1Y1_3") (pintype "tri_state"))
      (node (ref "E107") (pin "9") (pinfunction "1Y4_9") (pintype "tri_state"))
      (node (ref "E73") (pin "13") (pinfunction "D2_13") (pintype "input"))
      (node (ref "E84") (pin "7") (pinfunction "1Y3_7") (pintype "tri_state"))
      (node (ref "E95") (pin "9") (pinfunction "1Y4_9") (pintype "tri_state"))
      (node (ref "E96") (pin "9") (pinfunction "1Y4_9") (pintype "tri_state"))
      (node (ref "R33") (pin "1") (pinfunction "1_1") (pintype "passive"))
    )
    (net (code "111") (name "Net-(E104A-1G)") (class "Default")
      (node (ref "E104") (pin "1") (pinfunction "1G_1") (pintype "input"))
      (node (ref "E94") (pin "6") (pinfunction "O_6") (pintype "output"))
    )
    (net (code "112") (name "Net-(E105A-1G)") (class "Default")
      (node (ref "E105") (pin "1") (pinfunction "1G_1") (pintype "input"))
      (node (ref "E105") (pin "15") (pinfunction "2G_15") (pintype "input"))
      (node (ref "E115") (pin "8") (pinfunction "O_8") (pintype "output"))
    )
    (net (code "113") (name "Net-(E107A-1Y1)") (class "Default")
      (node (ref "E107") (pin "3") (pinfunction "1Y1_3") (pintype "tri_state"))
      (node (ref "E93") (pin "13") (pinfunction "D4_13") (pintype "input"))
      (node (ref "E95") (pin "3") (pinfunction "1Y1_3") (pintype "tri_state"))
      (node (ref "E96") (pin "3") (pinfunction "1Y1_3") (pintype "tri_state"))
      (node (ref "E97") (pin "11") (pinfunction "D4_11") (pintype "input"))
      (node (ref "E97") (pin "6") (pinfunction "Q4_6") (pintype "tri_state"))
      (node (ref "R35") (pin "1") (pinfunction "1_1") (pintype "passive"))
    )
    (net (code "114") (name "Net-(E107A-1Y2)") (class "Default")
      (node (ref "E107") (pin "5") (pinfunction "1Y2_5") (pintype "tri_state"))
      (node (ref "E93") (pin "12") (pinfunction "D3_12") (pintype "input"))
      (node (ref "E95") (pin "5") (pinfunction "1Y2_5") (pintype "tri_state"))
      (node (ref "E96") (pin "5") (pinfunction "1Y2_5") (pintype "tri_state"))
      (node (ref "E97") (pin "12") (pinfunction "D3_12") (pintype "input"))
      (node (ref "E97") (pin "5") (pinfunction "Q3_5") (pintype "tri_state"))
      (node (ref "R34") (pin "1") (pinfunction "1_1") (pintype "passive"))
    )
    (net (code "115") (name "Net-(E107A-1Y3)") (class "Default")
      (node (ref "E107") (pin "7") (pinfunction "1Y3_7") (pintype "tri_state"))
      (node (ref "E93") (pin "5") (pinfunction "D2_5") (pintype "input"))
      (node (ref "E95") (pin "7") (pinfunction "1Y3_7") (pintype "tri_state"))
      (node (ref "E96") (pin "7") (pinfunction "1Y3_7") (pintype "tri_state"))
      (node (ref "E97") (pin "13") (pinfunction "D2_13") (pintype "input"))
      (node (ref "E97") (pin "4") (pinfunction "Q2_4") (pintype "tri_state"))
      (node (ref "R29") (pin "1") (pinfunction "1_1") (pintype "passive"))
    )
    (net (code "116") (name "Net-(E112A-O2)") (class "Default")
      (node (ref "E112") (pin "10") (pinfunction "O2_10") (pintype "tri_state"))
      (node (ref "E114") (pin "1") (pinfunction "A6_1") (pintype "input"))
    )
    (net (code "117") (name "Net-(E115A-O)") (class "Default")
      (node (ref "E115") (pin "2") (pinfunction "O_2") (pintype "output"))
      (node (ref "E97") (pin "2") (pinfunction "N_2") (pintype "input"))
    )
    (net (code "118") (name "Net-(Q1-B)") (class "Default")
      (node (ref "C12") (pin "2") (pinfunction "2_2") (pintype "passive"))
      (node (ref "D1") (pin "A") (pinfunction "A_A") (pintype "passive"))
      (node (ref "Q1") (pin "2") (pinfunction "B_2") (pintype "passive"))
      (node (ref "R5") (pin "2") (pinfunction "2_2") (pintype "passive"))
    )
    (net (code "119") (name "P1_3V") (class "Default")
      (node (ref "E114") (pin "2") (pinfunction "A5_2") (pintype "input"))
      (node (ref "E114") (pin "3") (pinfunction "A4_3") (pintype "input"))
      (node (ref "E114") (pin "4") (pinfunction "A3_4") (pintype "input"))
      (node (ref "E78") (pin "3") (pinfunction "A=B_I_3") (pintype "input"))
      (node (ref "R21") (pin "1") (pinfunction "1_1") (pintype "passive"))
    )
    (net (code "120") (name "P1_BFL0") (class "Default")
      (node (ref "E87") (pin "10") (pinfunction "O2_10") (pintype "tri_state"))
      (node (ref "E95") (pin "10") (pinfunction "1A4_10") (pintype "input"))
      (node (ref "E95") (pin "2") (pinfunction "1A1_2") (pintype "input"))
    )
    (net (code "121") (name "P1_BFL1") (class "Default")
      (node (ref "E87") (pin "11") (pinfunction "O1_11") (pintype "tri_state"))
      (node (ref "E95") (pin "12") (pinfunction "2A1_12") (pintype "input"))
      (node (ref "E95") (pin "4") (pinfunction "1A2_4") (pintype "input"))
    )
    (net (code "122") (name "P1_BFL2") (class "Default")
      (node (ref "E87") (pin "12") (pinfunction "O0_12") (pintype "tri_state"))
      (node (ref "E95") (pin "14") (pinfunction "2A2_14") (pintype "input"))
      (node (ref "E95") (pin "6") (pinfunction "1A3_6") (pintype "input"))
    )
    (net (code "123") (name "P1_OVER") (class "Default")
      (node (ref "E39") (pin "12") (pinfunction "O_12") (pintype "output"))
      (node (ref "E49") (pin "11") (pinfunction "I2_11") (pintype "input"))
    )
    (net (code "124") (name "P1_RR0") (class "Default")
      (node (ref "E85") (pin "15") (pinfunction "Q6_15") (pintype "output"))
      (node (ref "E86") (pin "2") (pinfunction "1A1_2") (pintype "input"))
    )
    (net (code "125") (name "P1_RR1") (class "Default")
      (node (ref "E85") (pin "2") (pinfunction "Q1_2") (pintype "output"))
      (node (ref "E86") (pin "4") (pinfunction "1A2_4") (pintype "input"))
    )
    (net (code "126") (name "P1_RR2") (class "Default")
      (node (ref "E114") (pin "7") (pinfunction "A2_7") (pintype "input"))
      (node (ref "E85") (pin "12") (pinfunction "Q5_12") (pintype "output"))
      (node (ref "E86") (pin "6") (pinfunction "1A3_6") (pintype "input"))
      (node (ref "E87") (pin "2") (pinfunction "A5_2") (pintype "input"))
    )
    (net (code "127") (name "P1_RR3") (class "Default")
      (node (ref "E112") (pin "2") (pinfunction "A5_2") (pintype "input"))
      (node (ref "E85") (pin "7") (pinfunction "Q3_7") (pintype "output"))
      (node (ref "E86") (pin "10") (pinfunction "1A4_10") (pintype "input"))
      (node (ref "E87") (pin "3") (pinfunction "A4_3") (pintype "input"))
    )
    (net (code "128") (name "P1_RR4") (class "Default")
      (node (ref "E112") (pin "7") (pinfunction "A2_7") (pintype "input"))
      (node (ref "E85") (pin "10") (pinfunction "Q4_10") (pintype "output"))
      (node (ref "E86") (pin "12") (pinfunction "2A1_12") (pintype "input"))
      (node (ref "E87") (pin "4") (pinfunction "A3_4") (pintype "input"))
    )
    (net (code "129") (name "P1_US0") (class "Default")
      (node (ref "E106") (pin "2") (pinfunction "1A1_2") (pintype "input"))
      (node (ref "E68") (pin "11") (pinfunction "B1_11") (pintype "input"))
      (node (ref "E88") (pin "15") (pinfunction "Q6_15") (pintype "output"))
    )
    (net (code "130") (name "P1_US1") (class "Default")
      (node (ref "E106") (pin "4") (pinfunction "1A2_4") (pintype "input"))
      (node (ref "E68") (pin "9") (pinfunction "B0_9") (pintype "input"))
      (node (ref "E88") (pin "2") (pinfunction "Q1_2") (pintype "output"))
    )
    (net (code "131") (name "P1_US2") (class "Default")
      (node (ref "E106") (pin "6") (pinfunction "1A3_6") (pintype "input"))
      (node (ref "E78") (pin "1") (pinfunction "B3_1") (pintype "input"))
      (node (ref "E88") (pin "5") (pinfunction "Q2_5") (pintype "output"))
    )
    (net (code "132") (name "P1_US3") (class "Default")
      (node (ref "E106") (pin "10") (pinfunction "1A4_10") (pintype "input"))
      (node (ref "E78") (pin "14") (pinfunction "B2_14") (pintype "input"))
      (node (ref "E88") (pin "12") (pinfunction "Q5_12") (pintype "output"))
    )
    (net (code "133") (name "P1_US4") (class "Default")
      (node (ref "E106") (pin "12") (pinfunction "2A1_12") (pintype "input"))
      (node (ref "E78") (pin "11") (pinfunction "B1_11") (pintype "input"))
      (node (ref "E88") (pin "7") (pinfunction "Q3_7") (pintype "output"))
    )
    (net (code "134") (name "P1_US5") (class "Default")
      (node (ref "E106") (pin "14") (pinfunction "2A2_14") (pintype "input"))
      (node (ref "E78") (pin "9") (pinfunction "B0_9") (pintype "input"))
      (node (ref "E88") (pin "10") (pinfunction "Q4_10") (pintype "output"))
    )
    (net (code "135") (name "P2_3V") (class "Default")
      (node (ref "E102") (pin "1") (pinfunction "CLR_1") (pintype "input"))
      (node (ref "E103") (pin "1") (pinfunction "CLR_1") (pintype "input"))
      (node (ref "E93") (pin "1") (pinfunction "CLR_1") (pintype "input"))
      (node (ref "R30") (pin "1") (pinfunction "1_1") (pintype "passive"))
    )
    (net (code "136") (name "P2_DFA") (class "Default")
      (node (ref "E102") (pin "6") (pinfunction "~{Q2}_6") (pintype "output"))
      (node (ref "E112") (pin "5") (pinfunction "A0_5") (pintype "input"))
    )
    (net (code "137") (name "P2_DFB") (class "Default")
      (node (ref "E102") (pin "11") (pinfunction "~{Q3}_11") (pintype "output"))
      (node (ref "E112") (pin "4") (pinfunction "A3_4") (pintype "input"))
    )
    (net (code "138") (name "P2_DFC") (class "Default")
      (node (ref "E102") (pin "14") (pinfunction "~{Q4}_14") (pintype "output"))
      (node (ref "E114") (pin "5") (pinfunction "A0_5") (pintype "input"))
    )
    (net (code "139") (name "P2_IFA") (class "Default")
      (node (ref "E112") (pin "6") (pinfunction "A1_6") (pintype "input"))
      (node (ref "E93") (pin "6") (pinfunction "~{Q2}_6") (pintype "output"))
    )
    (net (code "140") (name "P2_IFB") (class "Default")
      (node (ref "E112") (pin "3") (pinfunction "A4_3") (pintype "input"))
      (node (ref "E93") (pin "11") (pinfunction "~{Q3}_11") (pintype "output"))
    )
    (net (code "141") (name "P2_IFC") (class "Default")
      (node (ref "E114") (pin "6") (pinfunction "A1_6") (pintype "input"))
      (node (ref "E93") (pin "14") (pinfunction "~{Q4}_14") (pintype "output"))
    )
    (net (code "142") (name "P2_SF0") (class "Default")
      (node (ref "E103") (pin "2") (pinfunction "Q1_2") (pintype "output"))
      (node (ref "E105") (pin "14") (pinfunction "2A2_14") (pintype "input"))
      (node (ref "E107") (pin "2") (pinfunction "1A1_2") (pintype "input"))
    )
    (net (code "143") (name "P2_SF1") (class "Default")
      (node (ref "E103") (pin "5") (pinfunction "Q2_5") (pintype "output"))
      (node (ref "E105") (pin "12") (pinfunction "2A1_12") (pintype "input"))
      (node (ref "E107") (pin "4") (pinfunction "1A2_4") (pintype "input"))
    )
    (net (code "144") (name "P2_SF2") (class "Default")
      (node (ref "E103") (pin "7") (pinfunction "Q3_7") (pintype "output"))
      (node (ref "E105") (pin "10") (pinfunction "1A4_10") (pintype "input"))
      (node (ref "E107") (pin "6") (pinfunction "1A3_6") (pintype "input"))
    )
    (net (code "145") (name "P2_SF3") (class "Default")
      (node (ref "E103") (pin "10") (pinfunction "Q4_10") (pintype "output"))
      (node (ref "E105") (pin "6") (pinfunction "1A3_6") (pintype "input"))
      (node (ref "E107") (pin "10") (pinfunction "1A4_10") (pintype "input"))
    )
    (net (code "146") (name "P2_SF4") (class "Default")
      (node (ref "E103") (pin "12") (pinfunction "Q5_12") (pintype "output"))
      (node (ref "E105") (pin "4") (pinfunction "1A2_4") (pintype "input"))
      (node (ref "E107") (pin "12") (pinfunction "2A1_12") (pintype "input"))
    )
    (net (code "147") (name "P2_SF5") (class "Default")
      (node (ref "E103") (pin "15") (pinfunction "Q6_15") (pintype "output"))
      (node (ref "E105") (pin "2") (pinfunction "1A1_2") (pintype "input"))
      (node (ref "E107") (pin "14") (pinfunction "2A2_14") (pintype "input"))
    )
    (net (code "148") (name "P2_SUF_OUT") (class "Default")
      (node (ref "E115") (pin "9") (pinfunction "I_9") (pintype "input"))
      (node (ref "E56") (pin "6") (pinfunction "O_6") (pintype "output"))
      (node (ref "E8") (pin "9") (pinfunction "I1_9") (pintype "input"))
    )
    (net (code "149") (name "P3_BD") (class "Default")
      (node (ref "E61") (pin "14") (pinfunction "O_14") (pintype "output"))
      (node (ref "E66") (pin "1") (pinfunction "I0_1") (pintype "input"))
      (node (ref "E70") (pin "2") (pinfunction "I1_2") (pintype "input"))
    )
    (net (code "150") (name "P3_BD1") (class "Default")
      (node (ref "E12") (pin "3") (pinfunction "I2_3") (pintype "output"))
    )
    (net (code "151") (name "P3_BD2") (class "Default")
      (node (ref "E12") (pin "10") (pinfunction "I1_10") (pintype "output"))
    )
    (net (code "152") (name "P3_BD3") (class "Default")
      (node (ref "E12") (pin "13") (pinfunction "I0_13") (pintype "output"))
    )
    (net (code "153") (name "P3_BD4") (class "Default")
      (node (ref "E13") (pin "6") (pinfunction "I3_6") (pintype "output"))
    )
    (net (code "154") (name "P3_BD5") (class "Default")
      (node (ref "E13") (pin "3") (pinfunction "I2_3") (pintype "output"))
      (node (ref "E50") (pin "10") (pinfunction "I1_10") (pintype "input"))
    )
    (net (code "155") (name "P3_BD6") (class "Default")
      (node (ref "E13") (pin "10") (pinfunction "I1_10") (pintype "output"))
      (node (ref "E2") (pin "1") (pinfunction "I_1") (pintype "input"))
      (node (ref "E88") (pin "14") (pinfunction "D6_14") (pintype "input"))
      (node (ref "E96") (pin "2") (pinfunction "1A1_2") (pintype "input"))
    )
    (net (code "156") (name "P3_BD7") (class "Default")
      (node (ref "E13") (pin "13") (pinfunction "I0_13") (pintype "output"))
      (node (ref "E2") (pin "3") (pinfunction "I_3") (pintype "input"))
      (node (ref "E85") (pin "14") (pinfunction "D6_14") (pintype "input"))
      (node (ref "E88") (pin "3") (pinfunction "D1_3") (pintype "input"))
      (node (ref "E96") (pin "4") (pinfunction "1A2_4") (pintype "input"))
    )
    (net (code "157") (name "P3_BD8") (class "Default")
      (node (ref "E2") (pin "5") (pinfunction "I_5") (pintype "input"))
      (node (ref "E45") (pin "6") (pinfunction "I3_6") (pintype "output"))
      (node (ref "E85") (pin "3") (pinfunction "D1_3") (pintype "input"))
      (node (ref "E88") (pin "4") (pinfunction "D2_4") (pintype "input"))
      (node (ref "E96") (pin "6") (pinfunction "1A3_6") (pintype "input"))
    )
    (net (code "158") (name "P3_BD9") (class "Default")
      (node (ref "E45") (pin "3") (pinfunction "I2_3") (pintype "output"))
      (node (ref "E85") (pin "13") (pinfunction "D5_13") (pintype "input"))
      (node (ref "E88") (pin "13") (pinfunction "D5_13") (pintype "input"))
      (node (ref "E96") (pin "10") (pinfunction "1A4_10") (pintype "input"))
    )
    (net (code "159") (name "P3_BD10") (class "Default")
      (node (ref "E45") (pin "10") (pinfunction "I1_10") (pintype "output"))
      (node (ref "E85") (pin "6") (pinfunction "D3_6") (pintype "input"))
      (node (ref "E88") (pin "6") (pinfunction "D3_6") (pintype "input"))
      (node (ref "E96") (pin "12") (pinfunction "2A1_12") (pintype "input"))
    )
    (net (code "160") (name "P3_BD11") (class "Default")
      (node (ref "E45") (pin "13") (pinfunction "I0_13") (pintype "output"))
      (node (ref "E85") (pin "11") (pinfunction "D4_11") (pintype "input"))
      (node (ref "E88") (pin "11") (pinfunction "D4_11") (pintype "input"))
      (node (ref "E96") (pin "14") (pinfunction "2A2_14") (pintype "input"))
    )
    (net (code "161") (name "P3_BF") (class "Default")
      (node (ref "E21") (pin "2") (pinfunction "I1_2") (pintype "input"))
      (node (ref "E30") (pin "11") (pinfunction "I6_11") (pintype "input"))
      (node (ref "E49") (pin "4") (pinfunction "I1_4") (pintype "input"))
      (node (ref "E61") (pin "13") (pinfunction "O_13") (pintype "output"))
    )
    (net (code "162") (name "P3_BINIT") (class "Default")
      (node (ref "E22") (pin "3") (pinfunction "I_3") (pintype "input"))
      (node (ref "E53") (pin "13") (pinfunction "O_13") (pintype "output"))
    )
    (net (code "163") (name "P3_BM0") (class "Default")
      (node (ref "E11") (pin "2") (pinfunction "O_2") (pintype "output"))
      (node (ref "E21") (pin "13") (pinfunction "I2_13") (pintype "input"))
      (node (ref "E30") (pin "1") (pinfunction "I0_1") (pintype "input"))
      (node (ref "E5") (pin "11") (pinfunction "I_11") (pintype "input"))
    )
    (net (code "164") (name "P3_BM1") (class "Default")
      (node (ref "E11") (pin "3") (pinfunction "O_3") (pintype "output"))
      (node (ref "E21") (pin "1") (pinfunction "I0_1") (pintype "input"))
      (node (ref "E29") (pin "3") (pinfunction "I1_3") (pintype "input"))
      (node (ref "E30") (pin "2") (pinfunction "I1_2") (pintype "input"))
    )
    (net (code "165") (name "P3_BM2") (class "Default")
      (node (ref "E11") (pin "13") (pinfunction "O_13") (pintype "output"))
      (node (ref "E14") (pin "21") (pinfunction "I14_21") (pintype "input"))
      (node (ref "E5") (pin "13") (pinfunction "I_13") (pintype "input"))
      (node (ref "E8") (pin "2") (pinfunction "I0_2") (pintype "input"))
    )
    (net (code "166") (name "P3_BM3") (class "Default")
      (node (ref "E11") (pin "14") (pinfunction "O_14") (pintype "output"))
      (node (ref "E14") (pin "22") (pinfunction "I13_22") (pintype "input"))
      (node (ref "E7") (pin "11") (pinfunction "I_11") (pintype "input"))
    )
    (net (code "167") (name "P3_BM4") (class "Default")
      (node (ref "E14") (pin "23") (pinfunction "I12_23") (pintype "input"))
      (node (ref "E25") (pin "2") (pinfunction "O_2") (pintype "output"))
      (node (ref "E28") (pin "3") (pinfunction "A4_3") (pintype "input"))
      (node (ref "E7") (pin "13") (pinfunction "I_13") (pintype "input"))
    )
    (net (code "168") (name "P3_BM5") (class "Default")
      (node (ref "E14") (pin "24") (pinfunction "I11_24") (pintype "input"))
      (node (ref "E25") (pin "3") (pinfunction "O_3") (pintype "output"))
      (node (ref "E28") (pin "4") (pinfunction "A3_4") (pintype "input"))
      (node (ref "E68") (pin "10") (pinfunction "A0_10") (pintype "input"))
    )
    (net (code "169") (name "P3_BM6") (class "Default")
      (node (ref "E14") (pin "25") (pinfunction "I10_25") (pintype "input"))
      (node (ref "E21") (pin "9") (pinfunction "I0_9") (pintype "input"))
      (node (ref "E25") (pin "13") (pinfunction "O_13") (pintype "output"))
      (node (ref "E31") (pin "21") (pinfunction "C_21") (pintype "input"))
      (node (ref "E78") (pin "13") (pinfunction "A2_13") (pintype "input"))
      (node (ref "E87") (pin "7") (pinfunction "A2_7") (pintype "input"))
    )
    (net (code "170") (name "P3_BM7") (class "Default")
      (node (ref "E14") (pin "26") (pinfunction "I9_26") (pintype "input"))
      (node (ref "E21") (pin "10") (pinfunction "I1_10") (pintype "input"))
      (node (ref "E25") (pin "14") (pinfunction "O_14") (pintype "output"))
      (node (ref "E31") (pin "22") (pinfunction "B_22") (pintype "input"))
      (node (ref "E78") (pin "12") (pinfunction "A1_12") (pintype "input"))
      (node (ref "E87") (pin "6") (pinfunction "A1_6") (pintype "input"))
    )
    (net (code "171") (name "P3_BM8") (class "Default")
      (node (ref "E14") (pin "27") (pinfunction "I8_27") (pintype "input"))
      (node (ref "E21") (pin "11") (pinfunction "I2_11") (pintype "input"))
      (node (ref "E31") (pin "23") (pinfunction "A_23") (pintype "input"))
      (node (ref "E71") (pin "2") (pinfunction "O_2") (pintype "output"))
      (node (ref "E78") (pin "10") (pinfunction "A0_10") (pintype "input"))
      (node (ref "E87") (pin "5") (pinfunction "A0_5") (pintype "input"))
    )
    (net (code "172") (name "P3_BM9") (class "Default")
      (node (ref "E14") (pin "2") (pinfunction "I7_2") (pintype "input"))
      (node (ref "E28") (pin "7") (pinfunction "A2_7") (pintype "input"))
      (node (ref "E31") (pin "20") (pinfunction "D_20") (pintype "input"))
      (node (ref "E36") (pin "10") (pinfunction "I1_10") (pintype "input"))
      (node (ref "E43") (pin "4") (pinfunction "I2_4") (pintype "input"))
      (node (ref "E47") (pin "5") (pinfunction "I0_5") (pintype "input"))
      (node (ref "E47") (pin "8") (pinfunction "I0_8") (pintype "input"))
      (node (ref "E47") (pin "9") (pinfunction "I1_9") (pintype "input"))
      (node (ref "E71") (pin "3") (pinfunction "O_3") (pintype "output"))
      (node (ref "E78") (pin "15") (pinfunction "A3_15") (pintype "input"))
    )
    (net (code "173") (name "P3_BM10") (class "Default")
      (node (ref "E14") (pin "3") (pinfunction "I6_3") (pintype "input"))
      (node (ref "E28") (pin "6") (pinfunction "A1_6") (pintype "input"))
      (node (ref "E71") (pin "13") (pinfunction "O_13") (pintype "output"))
    )
    (net (code "174") (name "P3_BM11") (class "Default")
      (node (ref "E14") (pin "4") (pinfunction "I5_4") (pintype "input"))
      (node (ref "E28") (pin "5") (pinfunction "A0_5") (pintype "input"))
      (node (ref "E36") (pin "12") (pinfunction "I2_12") (pintype "input"))
      (node (ref "E44") (pin "13") (pinfunction "I_13") (pintype "input"))
      (node (ref "E71") (pin "14") (pinfunction "O_14") (pintype "output"))
    )
    (net (code "175") (name "P3_BPAUSE") (class "Default")
      (node (ref "E14") (pin "5") (pinfunction "I4_5") (pintype "input"))
      (node (ref "E26") (pin "16") (pinfunction "1Q_16") (pintype "output"))
    )
    (net (code "176") (name "P3_BPLA") (class "Default")
      (node (ref "E53") (pin "3") (pinfunction "O_3") (pintype "output"))
      (node (ref "E57") (pin "5") (pinfunction "I1_5") (pintype "input"))
    )
    (net (code "177") (name "P3_BTP3") (class "Default")
      (node (ref "E18") (pin "1") (pinfunction "I0_1") (pintype "input"))
      (node (ref "E18") (pin "4") (pinfunction "I0_4") (pintype "input"))
      (node (ref "E32") (pin "11") (pinfunction "CLK_11") (pintype "input"))
      (node (ref "E38") (pin "3") (pinfunction "O_3") (pintype "output"))
      (node (ref "E50") (pin "12") (pinfunction "I0_12") (pintype "input"))
      (node (ref "E67") (pin "10") (pinfunction "I1_10") (pintype "input"))
      (node (ref "E76") (pin "11") (pinfunction "CLK_11") (pintype "input"))
    )
    (net (code "178") (name "P3_BTP4") (class "Default")
      (node (ref "E27") (pin "12") (pinfunction "O_12") (pintype "output"))
      (node (ref "E57") (pin "9") (pinfunction "I0_9") (pintype "input"))
      (node (ref "E63") (pin "11") (pinfunction "CLK_11") (pintype "input"))
      (node (ref "E63") (pin "3") (pinfunction "CLK_3") (pintype "input"))
      (node (ref "E73") (pin "7") (pinfunction "CLK_7") (pintype "input"))
    )
    (net (code "179") (name "P3_BTS3") (class "Default")
      (node (ref "E20") (pin "12") (pinfunction "I1_12") (pintype "input"))
      (node (ref "E51") (pin "13") (pinfunction "O_13") (pintype "output"))
      (node (ref "E64") (pin "2") (pinfunction "I0_2") (pintype "input"))
      (node (ref "E64") (pin "3") (pinfunction "I1_3") (pintype "input"))
    )
    (net (code "180") (name "P3_BTS4") (class "Default")
      (node (ref "E26") (pin "3") (pinfunction "2D_3") (pintype "input"))
      (node (ref "E51") (pin "3") (pinfunction "O_3") (pintype "output"))
      (node (ref "E92") (pin "1") (pinfunction "I0_1") (pintype "input"))
    )
    (net (code "181") (name "P3_INIOEN") (class "Default")
      (node (ref "E14") (pin "10") (pinfunction "O7_10") (pintype "tri_state"))
      (node (ref "E36") (pin "13") (pinfunction "I3_13") (pintype "input"))
      (node (ref "E43") (pin "5") (pinfunction "I3_5") (pintype "input"))
    )
    (net (code "182") (name "P4_3V") (class "Default")
      (node (ref "E76") (pin "1") (pinfunction "CLR_1") (pintype "input"))
      (node (ref "R18") (pin "1") (pinfunction "1_1") (pintype "passive"))
    )
    (net (code "183") (name "P4_BTS1") (class "Default")
      (node (ref "E20") (pin "5") (pinfunction "I0_5") (pintype "input"))
      (node (ref "E41") (pin "13") (pinfunction "O_13") (pintype "output"))
      (node (ref "E92") (pin "10") (pinfunction "I1_10") (pintype "input"))
      (node (ref "E94") (pin "2") (pinfunction "I1_2") (pintype "input"))
    )
    (net (code "184") (name "P4_CKDF") (class "Default")
      (node (ref "E102") (pin "9") (pinfunction "CLK_9") (pintype "input"))
      (node (ref "E79") (pin "3") (pinfunction "F0_3") (pintype "output"))
    )
    (net (code "185") (name "P4_CKIF") (class "Default")
      (node (ref "E79") (pin "4") (pinfunction "F1_4") (pintype "output"))
      (node (ref "E93") (pin "9") (pinfunction "CLK_9") (pintype "input"))
    )
    (net (code "186") (name "P4_CKIFB") (class "Default")
      (node (ref "E79") (pin "13") (pinfunction "F3_13") (pintype "output"))
      (node (ref "E97") (pin "7") (pinfunction "CLK_7") (pintype "input"))
    )
    (net (code "187") (name "P4_CKSV") (class "Default")
      (node (ref "E103") (pin "9") (pinfunction "CLK_9") (pintype "input"))
      (node (ref "E58") (pin "4") (pinfunction "O_4") (pintype "output"))
      (node (ref "E59") (pin "3") (pinfunction "CLK_3") (pintype "input"))
    )
    (net (code "188") (name "P4_CKUF") (class "Default")
      (node (ref "E59") (pin "11") (pinfunction "CLK_11") (pintype "input"))
      (node (ref "E69") (pin "4") (pinfunction "F1_4") (pintype "output"))
    )
    (net (code "189") (name "P4_CKUFB") (class "Default")
      (node (ref "E60") (pin "3") (pinfunction "CLK_3") (pintype "input"))
      (node (ref "E69") (pin "12") (pinfunction "F2_12") (pintype "output"))
    )
    (net (code "190") (name "P4_DFEN") (class "Default")
      (node (ref "E66") (pin "12") (pinfunction "I0_12") (pintype "input"))
      (node (ref "E76") (pin "8") (pinfunction "~{Q}_8") (pintype "output"))
      (node (ref "E94") (pin "4") (pinfunction "I0_4") (pintype "input"))
    )
    (net (code "191") (name "P4_FATAL(0)") (class "Default")
      (node (ref "E32") (pin "5") (pinfunction "Q_5") (pintype "output"))
      (node (ref "E83") (pin "12") (pinfunction "A1_12") (pintype "input"))
    )
    (net (code "192") (name "P4_INIT_EN") (class "Default")
      (node (ref "E76") (pin "6") (pinfunction "~{Q}_6") (pintype "output"))
      (node (ref "E94") (pin "5") (pinfunction "I1_5") (pintype "input"))
    )
    (net (code "193") (name "P4_INT") (class "Default")
      (node (ref "E115") (pin "3") (pinfunction "I_3") (pintype "input"))
      (node (ref "E29") (pin "4") (pinfunction "O_4") (pintype "output"))
      (node (ref "E57") (pin "10") (pinfunction "I1_10") (pintype "input"))
      (node (ref "E97") (pin "1") (pinfunction "M_1") (pintype "input"))
    )
    (net (code "194") (name "P4_INT_IN") (class "Default")
      (node (ref "E38") (pin "5") (pinfunction "I1_5") (pintype "input"))
      (node (ref "E77") (pin "5") (pinfunction "Q_5") (pintype "output"))
    )
    (net (code "195") (name "P4_INT_IN_PROG") (class "Default")
      (node (ref "E29") (pin "5") (pinfunction "I0_5") (pintype "input"))
      (node (ref "E3") (pin "2") (pinfunction "O_2") (pintype "output"))
    )
    (net (code "196") (name "P4_JMP+JMS") (class "Default")
      (node (ref "E58") (pin "9") (pinfunction "I_9") (pintype "input"))
      (node (ref "E61") (pin "2") (pinfunction "O_2") (pintype "output"))
      (node (ref "E70") (pin "1") (pinfunction "I0_1") (pintype "input"))
    )
    (net (code "197") (name "P4_LXA") (class "Default")
      (node (ref "E48") (pin "11") (pinfunction "I0_11") (pintype "input"))
      (node (ref "E51") (pin "14") (pinfunction "O_14") (pintype "output"))
      (node (ref "E57") (pin "4") (pinfunction "I0_4") (pintype "input"))
      (node (ref "E61") (pin "10") (pinfunction "I1_10") (pintype "input"))
      (node (ref "E61") (pin "11") (pinfunction "I0_11") (pintype "input"))
    )
    (net (code "198") (name "P4_NEW_FLD") (class "Default")
      (node (ref "E115") (pin "1") (pinfunction "I_1") (pintype "input"))
      (node (ref "E18") (pin "2") (pinfunction "I1_2") (pintype "input"))
      (node (ref "E70") (pin "6") (pinfunction "O_6") (pintype "output"))
      (node (ref "E80") (pin "10") (pinfunction "A0_10") (pintype "input"))
    )
    (net (code "199") (name "P4_PCLR") (class "Default")
      (node (ref "E1") (pin "15") (pinfunction "CLR_15") (pintype "input"))
      (node (ref "E73") (pin "15") (pinfunction "CLR_15") (pintype "input"))
      (node (ref "PAD1") (pin "1") (pinfunction "P_1") (pintype "passive"))
    )
    (net (code "200") (name "P4_PLXA") (class "Default")
      (node (ref "E1") (pin "7") (pinfunction "CLK_7") (pintype "input"))
      (node (ref "E58") (pin "2") (pinfunction "O_2") (pintype "output"))
    )
    (net (code "201") (name "P4_USINT") (class "Default")
      (node (ref "E32") (pin "4") (pinfunction "PRE_4") (pintype "input"))
      (node (ref "E32") (pin "8") (pinfunction "~{Q}_8") (pintype "output"))
      (node (ref "E38") (pin "4") (pinfunction "I0_4") (pintype "input"))
      (node (ref "E42") (pin "11") (pinfunction "I0_11") (pintype "input"))
      (node (ref "E42") (pin "12") (pinfunction "I1_12") (pintype "input"))
      (node (ref "E42") (pin "5") (pinfunction "I0_5") (pintype "input"))
    )
    (net (code "202") (name "P6_BIND2") (class "Default")
      (node (ref "E20") (pin "6") (pinfunction "I1_6") (pintype "input"))
      (node (ref "E72") (pin "2") (pinfunction "O_2") (pintype "output"))
      (node (ref "E92") (pin "11") (pinfunction "I2_11") (pintype "input"))
      (node (ref "E94") (pin "1") (pinfunction "I0_1") (pintype "input"))
    )
    (net (code "203") (name "P6_USM") (class "Default")
      (node (ref "E112") (pin "1") (pinfunction "A6_1") (pintype "input"))
      (node (ref "E112") (pin "14") (pinfunction "A8_14") (pintype "input"))
      (node (ref "E114") (pin "14") (pinfunction "A8_14") (pintype "input"))
      (node (ref "E14") (pin "8") (pinfunction "I1_8") (pintype "input"))
      (node (ref "E30") (pin "12") (pinfunction "I7_12") (pintype "input"))
      (node (ref "E49") (pin "9") (pinfunction "I0_9") (pintype "input"))
      (node (ref "E59") (pin "8") (pinfunction "~{Q}_8") (pintype "output"))
      (node (ref "E8") (pin "3") (pinfunction "I1_3") (pintype "input"))
      (node (ref "E8") (pin "6") (pinfunction "I1_6") (pintype "input"))
      (node (ref "E87") (pin "15") (pinfunction "A7_15") (pintype "input"))
    )
    (net (code "204") (name "PULSE_LA") (class "Default")
      (node (ref "E53") (pin "5") (pinfunction "I1_5") (pintype "input"))
      (node (ref "U$1") (pin "DR2") (pinfunction "1_DR2") (pintype "bidirectional"))
    )
    (net (code "205") (name "TP1") (class "Default")
      (node (ref "U$1") (pin "CD2") (pinfunction "1_CD2") (pintype "bidirectional"))
    )
    (net (code "206") (name "TP3") (class "Default")
      (node (ref "E51") (pin "7") (pinfunction "I1_7") (pintype "input"))
      (node (ref "U$1") (pin "CH2") (pinfunction "1_CH2") (pintype "bidirectional"))
    )
    (net (code "207") (name "TP4") (class "Default")
      (node (ref "E27") (pin "1") (pinfunction "I0_1") (pintype "input"))
      (node (ref "E27") (pin "13") (pinfunction "I2_13") (pintype "input"))
      (node (ref "E27") (pin "2") (pinfunction "I1_2") (pintype "input"))
      (node (ref "U$1") (pin "CJ2") (pinfunction "1_CJ2") (pintype "bidirectional"))
    )
    (net (code "208") (name "VCC") (class "Default")
      (node (ref "C1") (pin "+") (pinfunction "+_+") (pintype "passive"))
      (node (ref "C10") (pin "1") (pinfunction "1_1") (pintype "passive"))
      (node (ref "C11") (pin "1") (pinfunction "1_1") (pintype "passive"))
      (node (ref "C13") (pin "1") (pinfunction "1_1") (pintype "passive"))
      (node (ref "C14") (pin "+") (pinfunction "+_+") (pintype "passive"))
      (node (ref "C15") (pin "1") (pinfunction "1_1") (pintype "passive"))
      (node (ref "C16") (pin "+") (pinfunction "+_+") (pintype "passive"))
      (node (ref "C17") (pin "1") (pinfunction "1_1") (pintype "passive"))
      (node (ref "C18") (pin "1") (pinfunction "1_1") (pintype "passive"))
      (node (ref "C2") (pin "1") (pinfunction "1_1") (pintype "passive"))
      (node (ref "C20") (pin "1") (pinfunction "1_1") (pintype "passive"))
      (node (ref "C21") (pin "1") (pinfunction "1_1") (pintype "passive"))
      (node (ref "C22") (pin "1") (pinfunction "1_1") (pintype "passive"))
      (node (ref "C23") (pin "1") (pinfunction "1_1") (pintype "passive"))
      (node (ref "C24") (pin "+") (pinfunction "+_+") (pintype "passive"))
      (node (ref "C25") (pin "1") (pinfunction "1_1") (pintype "passive"))
      (node (ref "C26") (pin "1") (pinfunction "1_1") (pintype "passive"))
      (node (ref "C27") (pin "1") (pinfunction "1_1") (pintype "passive"))
      (node (ref "C28") (pin "1") (pinfunction "1_1") (pintype "passive"))
      (node (ref "C29") (pin "1") (pinfunction "1_1") (pintype "passive"))
      (node (ref "C3") (pin "1") (pinfunction "1_1") (pintype "passive"))
      (node (ref "C31") (pin "1") (pinfunction "1_1") (pintype "passive"))
      (node (ref "C32") (pin "1") (pinfunction "1_1") (pintype "passive"))
      (node (ref "C33") (pin "1") (pinfunction "1_1") (pintype "passive"))
      (node (ref "C34") (pin "1") (pinfunction "1_1") (pintype "passive"))
      (node (ref "C35") (pin "1") (pinfunction "1_1") (pintype "passive"))
      (node (ref "C36") (pin "1") (pinfunction "1_1") (pintype "passive"))
      (node (ref "C4") (pin "1") (pinfunction "1_1") (pintype "passive"))
      (node (ref "C5") (pin "1") (pinfunction "1_1") (pintype "passive"))
      (node (ref "C6") (pin "1") (pinfunction "1_1") (pintype "passive"))
      (node (ref "C7") (pin "1") (pinfunction "1_1") (pintype "passive"))
      (node (ref "C8") (pin "+") (pinfunction "+_+") (pintype "passive"))
      (node (ref "C9") (pin "1") (pinfunction "1_1") (pintype "passive"))
      (node (ref "E101") (pin "16") (pinfunction "+UB_16") (pintype "power_in"))
      (node (ref "E26") (pin "5") (pinfunction "+UB_5") (pintype "power_in"))
      (node (ref "E83") (pin "16") (pinfunction "+UB_16") (pintype "power_in"))
      (node (ref "R1") (pin "1") (pinfunction "1_1") (pintype "passive"))
      (node (ref "R10") (pin "2") (pinfunction "2_2") (pintype "passive"))
      (node (ref "R12") (pin "1") (pinfunction "1_1") (pintype "passive"))
      (node (ref "R13") (pin "2") (pinfunction "2_2") (pintype "passive"))
      (node (ref "R14") (pin "2") (pinfunction "2_2") (pintype "passive"))
      (node (ref "R15") (pin "2") (pinfunction "2_2") (pintype "passive"))
      (node (ref "R16") (pin "2") (pinfunction "2_2") (pintype "passive"))
      (node (ref "R17") (pin "2") (pinfunction "2_2") (pintype "passive"))
      (node (ref "R18") (pin "2") (pinfunction "2_2") (pintype "passive"))
      (node (ref "R19") (pin "2") (pinfunction "2_2") (pintype "passive"))
      (node (ref "R2") (pin "1") (pinfunction "1_1") (pintype "passive"))
      (node (ref "R21") (pin "2") (pinfunction "2_2") (pintype "passive"))
      (node (ref "R24") (pin "1") (pinfunction "1_1") (pintype "passive"))
      (node (ref "R25") (pin "1") (pinfunction "1_1") (pintype "passive"))
      (node (ref "R26") (pin "1") (pinfunction "1_1") (pintype "passive"))
      (node (ref "R27") (pin "1") (pinfunction "1_1") (pintype "passive"))
      (node (ref "R28") (pin "2") (pinfunction "2_2") (pintype "passive"))
      (node (ref "R29") (pin "2") (pinfunction "2_2") (pintype "passive"))
      (node (ref "R3") (pin "2") (pinfunction "2_2") (pintype "passive"))
      (node (ref "R30") (pin "2") (pinfunction "2_2") (pintype "passive"))
      (node (ref "R31") (pin "1") (pinfunction "1_1") (pintype "passive"))
      (node (ref "R32") (pin "2") (pinfunction "2_2") (pintype "passive"))
      (node (ref "R33") (pin "2") (pinfunction "2_2") (pintype "passive"))
      (node (ref "R34") (pin "2") (pinfunction "2_2") (pintype "passive"))
      (node (ref "R35") (pin "2") (pinfunction "2_2") (pintype "passive"))
      (node (ref "R4") (pin "2") (pinfunction "2_2") (pintype "passive"))
      (node (ref "R6") (pin "1") (pinfunction "1_1") (pintype "passive"))
      (node (ref "R7") (pin "1") (pinfunction "1_1") (pintype "passive"))
      (node (ref "R8") (pin "1") (pinfunction "1_1") (pintype "passive"))
      (node (ref "R9") (pin "1") (pinfunction "1_1") (pintype "passive"))
      (node (ref "U$1") (pin "AA2") (pinfunction "1_AA2") (pintype "bidirectional"))
      (node (ref "U$1") (pin "BA2") (pinfunction "1_BA2") (pintype "bidirectional"))
      (node (ref "U$1") (pin "CA2") (pinfunction "1_CA2") (pintype "bidirectional"))
    )
    (net (code "209") (name "unconnected-(E1A-D1-Pad14)") (class "Default")
      (node (ref "E1") (pin "14") (pinfunction "D1_14") (pintype "input"))
    )
    (net (code "210") (name "unconnected-(E1A-Q1-Pad3)") (class "Default")
      (node (ref "E1") (pin "3") (pinfunction "Q1_3") (pintype "tri_state"))
    )
    (net (code "211") (name "unconnected-(E2E-I-Pad11)") (class "Default")
      (node (ref "E2") (pin "11") (pinfunction "I_11") (pintype "input"))
    )
    (net (code "212") (name "unconnected-(E2E-O-Pad10)") (class "Default")
      (node (ref "E2") (pin "10") (pinfunction "O_10") (pintype "output"))
    )
    (net (code "213") (name "unconnected-(E2F-I-Pad13)") (class "Default")
      (node (ref "E2") (pin "13") (pinfunction "I_13") (pintype "input"))
    )
    (net (code "214") (name "unconnected-(E2F-O-Pad12)") (class "Default")
      (node (ref "E2") (pin "12") (pinfunction "O_12") (pintype "output"))
    )
    (net (code "215") (name "unconnected-(E3C-I0-Pad9)") (class "Default")
      (node (ref "E3") (pin "9") (pinfunction "I0_9") (pintype "input"))
    )
    (net (code "216") (name "unconnected-(E3C-I1-Pad10)") (class "Default")
      (node (ref "E3") (pin "10") (pinfunction "I1_10") (pintype "input"))
    )
    (net (code "217") (name "unconnected-(E3C-O-Pad14)") (class "Default")
      (node (ref "E3") (pin "14") (pinfunction "O_14") (pintype "output"))
    )
    (net (code "218") (name "unconnected-(E4A-I0-Pad2)") (class "Default")
      (node (ref "E4") (pin "2") (pinfunction "I0_2") (pintype "input"))
    )
    (net (code "219") (name "unconnected-(E4A-I1-Pad3)") (class "Default")
      (node (ref "E4") (pin "3") (pinfunction "I1_3") (pintype "input"))
    )
    (net (code "220") (name "unconnected-(E4A-O-Pad1)") (class "Default")
      (node (ref "E4") (pin "1") (pinfunction "O_1") (pintype "open_collector"))
    )
    (net (code "221") (name "unconnected-(E6B-I0-Pad4)") (class "Default")
      (node (ref "E6") (pin "4") (pinfunction "I0_4") (pintype "input"))
    )
    (net (code "222") (name "unconnected-(E6B-I1-Pad5)") (class "Default")
      (node (ref "E6") (pin "5") (pinfunction "I1_5") (pintype "input"))
    )
    (net (code "223") (name "unconnected-(E6B-O-Pad6)") (class "Default")
      (node (ref "E6") (pin "6") (pinfunction "O_6") (pintype "output"))
    )
    (net (code "224") (name "unconnected-(E9B-I0-Pad9)") (class "Default")
      (node (ref "E9") (pin "9") (pinfunction "I0_9") (pintype "input"))
    )
    (net (code "225") (name "unconnected-(E9B-I1-Pad10)") (class "Default")
      (node (ref "E9") (pin "10") (pinfunction "I1_10") (pintype "input"))
    )
    (net (code "226") (name "unconnected-(E9B-I2-Pad12)") (class "Default")
      (node (ref "E9") (pin "12") (pinfunction "I2_12") (pintype "input"))
    )
    (net (code "227") (name "unconnected-(E9B-I3-Pad13)") (class "Default")
      (node (ref "E9") (pin "13") (pinfunction "I3_13") (pintype "input"))
    )
    (net (code "228") (name "unconnected-(E9B-O-Pad8)") (class "Default")
      (node (ref "E9") (pin "8") (pinfunction "O_8") (pintype "output"))
    )
    (net (code "229") (name "unconnected-(E10-Pad1)") (class "Default")
      (node (ref "E10") (pin "1") (pinfunction "1_1") (pintype "passive"))
    )
    (net (code "230") (name "unconnected-(E10-Pad2)") (class "Default")
      (node (ref "E10") (pin "2") (pinfunction "2_2") (pintype "passive"))
    )
    (net (code "231") (name "unconnected-(E10-Pad3)") (class "Default")
      (node (ref "E10") (pin "3") (pinfunction "3_3") (pintype "passive"))
    )
    (net (code "232") (name "unconnected-(E10-Pad4)") (class "Default")
      (node (ref "E10") (pin "4") (pinfunction "4_4") (pintype "passive"))
    )
    (net (code "233") (name "unconnected-(E10-Pad5)") (class "Default")
      (node (ref "E10") (pin "5") (pinfunction "5_5") (pintype "passive"))
    )
    (net (code "234") (name "unconnected-(E10-Pad6)") (class "Default")
      (node (ref "E10") (pin "6") (pinfunction "6_6") (pintype "passive"))
    )
    (net (code "235") (name "unconnected-(E10-Pad7)") (class "Default")
      (node (ref "E10") (pin "7") (pinfunction "7_7") (pintype "passive"))
    )
    (net (code "236") (name "unconnected-(E10-Pad8)") (class "Default")
      (node (ref "E10") (pin "8") (pinfunction "8_8") (pintype "passive"))
    )
    (net (code "237") (name "unconnected-(E10-Pad9)") (class "Default")
      (node (ref "E10") (pin "9") (pinfunction "9_9") (pintype "passive"))
    )
    (net (code "238") (name "unconnected-(E10-Pad10)") (class "Default")
      (node (ref "E10") (pin "10") (pinfunction "10_10") (pintype "passive"))
    )
    (net (code "239") (name "unconnected-(E10-Pad11)") (class "Default")
      (node (ref "E10") (pin "11") (pinfunction "11_11") (pintype "passive"))
    )
    (net (code "240") (name "unconnected-(E10-Pad12)") (class "Default")
      (node (ref "E10") (pin "12") (pinfunction "12_12") (pintype "passive"))
    )
    (net (code "241") (name "unconnected-(E10-Pad13)") (class "Default")
      (node (ref "E10") (pin "13") (pinfunction "13_13") (pintype "passive"))
    )
    (net (code "242") (name "unconnected-(E10-Pad14)") (class "Default")
      (node (ref "E10") (pin "14") (pinfunction "14_14") (pintype "passive"))
    )
    (net (code "243") (name "unconnected-(E10-Pad15)") (class "Default")
      (node (ref "E10") (pin "15") (pinfunction "15_15") (pintype "passive"))
    )
    (net (code "244") (name "unconnected-(E10-Pad16)") (class "Default")
      (node (ref "E10") (pin "16") (pinfunction "16_16") (pintype "passive"))
    )
    (net (code "245") (name "unconnected-(E12A-I3-Pad6)") (class "Default")
      (node (ref "E12") (pin "6") (pinfunction "I3_6") (pintype "output"))
    )
    (net (code "246") (name "unconnected-(E14A-O4-Pad13)") (class "Default")
      (node (ref "E14") (pin "13") (pinfunction "O4_13") (pintype "tri_state"))
    )
    (net (code "247") (name "unconnected-(E20C-I0-Pad8)") (class "Default")
      (node (ref "E20") (pin "8") (pinfunction "I0_8") (pintype "input"))
    )
    (net (code "248") (name "unconnected-(E20C-I1-Pad9)") (class "Default")
      (node (ref "E20") (pin "9") (pinfunction "I1_9") (pintype "input"))
    )
    (net (code "249") (name "unconnected-(E20C-O-Pad10)") (class "Default")
      (node (ref "E20") (pin "10") (pinfunction "O_10") (pintype "open_collector"))
    )
    (net (code "250") (name "unconnected-(E21B-I0-Pad3)") (class "Default")
      (node (ref "E21") (pin "3") (pinfunction "I0_3") (pintype "input"))
    )
    (net (code "251") (name "unconnected-(E21B-I1-Pad4)") (class "Default")
      (node (ref "E21") (pin "4") (pinfunction "I1_4") (pintype "input"))
    )
    (net (code "252") (name "unconnected-(E21B-I2-Pad5)") (class "Default")
      (node (ref "E21") (pin "5") (pinfunction "I2_5") (pintype "input"))
    )
    (net (code "253") (name "unconnected-(E21B-O-Pad6)") (class "Default")
      (node (ref "E21") (pin "6") (pinfunction "O_6") (pintype "output"))
    )
    (net (code "254") (name "unconnected-(E26D-~{1Q}-Pad1)") (class "Default")
      (node (ref "E26") (pin "1") (pinfunction "~{1Q}_1") (pintype "output"))
    )
    (net (code "255") (name "unconnected-(E26D-~{2Q}-Pad14)") (class "Default")
      (node (ref "E26") (pin "14") (pinfunction "~{2Q}_14") (pintype "output"))
    )
    (net (code "256") (name "unconnected-(E31A-0-Pad1)") (class "Default")
      (node (ref "E31") (pin "1") (pinfunction "0_1") (pintype "output"))
    )
    (net (code "257") (name "unconnected-(E31A-3-Pad4)") (class "Default")
      (node (ref "E31") (pin "4") (pinfunction "3_4") (pintype "output"))
    )
    (net (code "258") (name "unconnected-(E40-Pad1)") (class "Default")
      (node (ref "E40") (pin "1") (pinfunction "1_1") (pintype "passive"))
    )
    (net (code "259") (name "unconnected-(E40-Pad2)") (class "Default")
      (node (ref "E40") (pin "2") (pinfunction "2_2") (pintype "passive"))
    )
    (net (code "260") (name "unconnected-(E40-Pad3)") (class "Default")
      (node (ref "E40") (pin "3") (pinfunction "3_3") (pintype "passive"))
    )
    (net (code "261") (name "unconnected-(E40-Pad4)") (class "Default")
      (node (ref "E40") (pin "4") (pinfunction "4_4") (pintype "passive"))
    )
    (net (code "262") (name "unconnected-(E40-Pad5)") (class "Default")
      (node (ref "E40") (pin "5") (pinfunction "5_5") (pintype "passive"))
    )
    (net (code "263") (name "unconnected-(E40-Pad6)") (class "Default")
      (node (ref "E40") (pin "6") (pinfunction "6_6") (pintype "passive"))
    )
    (net (code "264") (name "unconnected-(E40-Pad7)") (class "Default")
      (node (ref "E40") (pin "7") (pinfunction "7_7") (pintype "passive"))
    )
    (net (code "265") (name "unconnected-(E40-Pad8)") (class "Default")
      (node (ref "E40") (pin "8") (pinfunction "8_8") (pintype "passive"))
    )
    (net (code "266") (name "unconnected-(E40-Pad9)") (class "Default")
      (node (ref "E40") (pin "9") (pinfunction "9_9") (pintype "passive"))
    )
    (net (code "267") (name "unconnected-(E40-Pad10)") (class "Default")
      (node (ref "E40") (pin "10") (pinfunction "10_10") (pintype "passive"))
    )
    (net (code "268") (name "unconnected-(E40-Pad11)") (class "Default")
      (node (ref "E40") (pin "11") (pinfunction "11_11") (pintype "passive"))
    )
    (net (code "269") (name "unconnected-(E40-Pad12)") (class "Default")
      (node (ref "E40") (pin "12") (pinfunction "12_12") (pintype "passive"))
    )
    (net (code "270") (name "unconnected-(E40-Pad13)") (class "Default")
      (node (ref "E40") (pin "13") (pinfunction "13_13") (pintype "passive"))
    )
    (net (code "271") (name "unconnected-(E40-Pad14)") (class "Default")
      (node (ref "E40") (pin "14") (pinfunction "14_14") (pintype "passive"))
    )
    (net (code "272") (name "unconnected-(E40-Pad15)") (class "Default")
      (node (ref "E40") (pin "15") (pinfunction "15_15") (pintype "passive"))
    )
    (net (code "273") (name "unconnected-(E40-Pad16)") (class "Default")
      (node (ref "E40") (pin "16") (pinfunction "16_16") (pintype "passive"))
    )
    (net (code "274") (name "unconnected-(E43B-I0-Pad9)") (class "Default")
      (node (ref "E43") (pin "9") (pinfunction "I0_9") (pintype "input"))
    )
    (net (code "275") (name "unconnected-(E43B-I1-Pad10)") (class "Default")
      (node (ref "E43") (pin "10") (pinfunction "I1_10") (pintype "input"))
    )
    (net (code "276") (name "unconnected-(E43B-I2-Pad12)") (class "Default")
      (node (ref "E43") (pin "12") (pinfunction "I2_12") (pintype "input"))
    )
    (net (code "277") (name "unconnected-(E43B-I3-Pad13)") (class "Default")
      (node (ref "E43") (pin "13") (pinfunction "I3_13") (pintype "input"))
    )
    (net (code "278") (name "unconnected-(E43B-O-Pad8)") (class "Default")
      (node (ref "E43") (pin "8") (pinfunction "O_8") (pintype "output"))
    )
    (net (code "279") (name "unconnected-(E57D-I0-Pad12)") (class "Default")
      (node (ref "E57") (pin "12") (pinfunction "I0_12") (pintype "input"))
    )
    (net (code "280") (name "unconnected-(E57D-I1-Pad13)") (class "Default")
      (node (ref "E57") (pin "13") (pinfunction "I1_13") (pintype "input"))
    )
    (net (code "281") (name "unconnected-(E57D-O-Pad11)") (class "Default")
      (node (ref "E57") (pin "11") (pinfunction "O_11") (pintype "output"))
    )
    (net (code "282") (name "unconnected-(E59A-Q-Pad5)") (class "Default")
      (node (ref "E59") (pin "5") (pinfunction "Q_5") (pintype "output"))
    )
    (net (code "283") (name "unconnected-(E60A-Q-Pad5)") (class "Default")
      (node (ref "E60") (pin "5") (pinfunction "Q_5") (pintype "output"))
    )
    (net (code "284") (name "unconnected-(E63A-~{Q}-Pad6)") (class "Default")
      (node (ref "E63") (pin "6") (pinfunction "~{Q}_6") (pintype "output"))
    )
    (net (code "285") (name "unconnected-(E63B-Q-Pad9)") (class "Default")
      (node (ref "E63") (pin "9") (pinfunction "Q_9") (pintype "output"))
    )
    (net (code "286") (name "unconnected-(E64D-I0-Pad11)") (class "Default")
      (node (ref "E64") (pin "11") (pinfunction "I0_11") (pintype "input"))
    )
    (net (code "287") (name "unconnected-(E64D-I1-Pad12)") (class "Default")
      (node (ref "E64") (pin "12") (pinfunction "I1_12") (pintype "input"))
    )
    (net (code "288") (name "unconnected-(E64D-O-Pad13)") (class "Default")
      (node (ref "E64") (pin "13") (pinfunction "O_13") (pintype "output"))
    )
    (net (code "289") (name "unconnected-(E66C-I0-Pad9)") (class "Default")
      (node (ref "E66") (pin "9") (pinfunction "I0_9") (pintype "input"))
    )
    (net (code "290") (name "unconnected-(E66C-I1-Pad10)") (class "Default")
      (node (ref "E66") (pin "10") (pinfunction "I1_10") (pintype "input"))
    )
    (net (code "291") (name "unconnected-(E66C-O-Pad8)") (class "Default")
      (node (ref "E66") (pin "8") (pinfunction "O_8") (pintype "output"))
    )
    (net (code "292") (name "unconnected-(E68A-A<B_O-Pad7)") (class "Default")
      (node (ref "E68") (pin "7") (pinfunction "A<B_O_7") (pintype "output"))
    )
    (net (code "293") (name "unconnected-(E69A-F3-Pad13)") (class "Default")
      (node (ref "E69") (pin "13") (pinfunction "F3_13") (pintype "output"))
    )
    (net (code "294") (name "unconnected-(E72C-I0-Pad9)") (class "Default")
      (node (ref "E72") (pin "9") (pinfunction "I0_9") (pintype "input"))
    )
    (net (code "295") (name "unconnected-(E72C-I1-Pad10)") (class "Default")
      (node (ref "E72") (pin "10") (pinfunction "I1_10") (pintype "input"))
    )
    (net (code "296") (name "unconnected-(E72C-O-Pad14)") (class "Default")
      (node (ref "E72") (pin "14") (pinfunction "O_14") (pintype "output"))
    )
    (net (code "297") (name "unconnected-(E72D-I0-Pad11)") (class "Default")
      (node (ref "E72") (pin "11") (pinfunction "I0_11") (pintype "input"))
    )
    (net (code "298") (name "unconnected-(E72D-I1-Pad12)") (class "Default")
      (node (ref "E72") (pin "12") (pinfunction "I1_12") (pintype "input"))
    )
    (net (code "299") (name "unconnected-(E72D-O-Pad13)") (class "Default")
      (node (ref "E72") (pin "13") (pinfunction "O_13") (pintype "output"))
    )
    (net (code "300") (name "unconnected-(E73A-D1-Pad14)") (class "Default")
      (node (ref "E73") (pin "14") (pinfunction "D1_14") (pintype "input"))
    )
    (net (code "301") (name "unconnected-(E73A-Q1-Pad3)") (class "Default")
      (node (ref "E73") (pin "3") (pinfunction "Q1_3") (pintype "tri_state"))
    )
    (net (code "302") (name "unconnected-(E75A-I0-Pad4)") (class "Default")
      (node (ref "E75") (pin "4") (pinfunction "I0_4") (pintype "input"))
    )
    (net (code "303") (name "unconnected-(E75A-I1-Pad5)") (class "Default")
      (node (ref "E75") (pin "5") (pinfunction "I1_5") (pintype "input"))
    )
    (net (code "304") (name "unconnected-(E75A-O-Pad3)") (class "Default")
      (node (ref "E75") (pin "3") (pinfunction "O_3") (pintype "output"))
    )
    (net (code "305") (name "unconnected-(E75C-I0-Pad9)") (class "Default")
      (node (ref "E75") (pin "9") (pinfunction "I0_9") (pintype "input"))
    )
    (net (code "306") (name "unconnected-(E75C-I1-Pad10)") (class "Default")
      (node (ref "E75") (pin "10") (pinfunction "I1_10") (pintype "input"))
    )
    (net (code "307") (name "unconnected-(E75C-O-Pad14)") (class "Default")
      (node (ref "E75") (pin "14") (pinfunction "O_14") (pintype "output"))
    )
    (net (code "308") (name "unconnected-(E75D-I0-Pad11)") (class "Default")
      (node (ref "E75") (pin "11") (pinfunction "I0_11") (pintype "input"))
    )
    (net (code "309") (name "unconnected-(E75D-I1-Pad12)") (class "Default")
      (node (ref "E75") (pin "12") (pinfunction "I1_12") (pintype "input"))
    )
    (net (code "310") (name "unconnected-(E75D-O-Pad13)") (class "Default")
      (node (ref "E75") (pin "13") (pinfunction "O_13") (pintype "output"))
    )
    (net (code "311") (name "unconnected-(E76A-Q-Pad5)") (class "Default")
      (node (ref "E76") (pin "5") (pinfunction "Q_5") (pintype "output"))
    )
    (net (code "312") (name "unconnected-(E77A-~{Q}-Pad6)") (class "Default")
      (node (ref "E77") (pin "6") (pinfunction "~{Q}_6") (pintype "output"))
    )
    (net (code "313") (name "unconnected-(E77B-CLK-Pad11)") (class "Default")
      (node (ref "E77") (pin "11") (pinfunction "CLK_11") (pintype "input"))
    )
    (net (code "314") (name "unconnected-(E77B-CLR-Pad13)") (class "Default")
      (node (ref "E77") (pin "13") (pinfunction "CLR_13") (pintype "input"))
    )
    (net (code "315") (name "unconnected-(E77B-D-Pad12)") (class "Default")
      (node (ref "E77") (pin "12") (pinfunction "D_12") (pintype "input"))
    )
    (net (code "316") (name "unconnected-(E77B-PRE-Pad10)") (class "Default")
      (node (ref "E77") (pin "10") (pinfunction "PRE_10") (pintype "input"))
    )
    (net (code "317") (name "unconnected-(E77B-Q-Pad9)") (class "Default")
      (node (ref "E77") (pin "9") (pinfunction "Q_9") (pintype "output"))
    )
    (net (code "318") (name "unconnected-(E77B-~{Q}-Pad8)") (class "Default")
      (node (ref "E77") (pin "8") (pinfunction "~{Q}_8") (pintype "output"))
    )
    (net (code "319") (name "unconnected-(E79A-F2-Pad12)") (class "Default")
      (node (ref "E79") (pin "12") (pinfunction "F2_12") (pintype "output"))
    )
    (net (code "320") (name "unconnected-(E83D-A4-Pad10)") (class "Default")
      (node (ref "E83") (pin "10") (pinfunction "A4_10") (pintype "input"))
    )
    (net (code "321") (name "unconnected-(E83D-Y4-Pad9)") (class "Default")
      (node (ref "E83") (pin "9") (pinfunction "Y4_9") (pintype "tri_state"))
    )
    (net (code "322") (name "unconnected-(E84A-1A4-Pad10)") (class "Default")
      (node (ref "E84") (pin "10") (pinfunction "1A4_10") (pintype "input"))
    )
    (net (code "323") (name "unconnected-(E84A-1Y4-Pad9)") (class "Default")
      (node (ref "E84") (pin "9") (pinfunction "1Y4_9") (pintype "tri_state"))
    )
    (net (code "324") (name "unconnected-(E84A-2A1-Pad12)") (class "Default")
      (node (ref "E84") (pin "12") (pinfunction "2A1_12") (pintype "input"))
    )
    (net (code "325") (name "unconnected-(E84A-2A2-Pad14)") (class "Default")
      (node (ref "E84") (pin "14") (pinfunction "2A2_14") (pintype "input"))
    )
    (net (code "326") (name "unconnected-(E84A-2G-Pad15)") (class "Default")
      (node (ref "E84") (pin "15") (pinfunction "2G_15") (pintype "input"))
    )
    (net (code "327") (name "unconnected-(E84A-2Y1-Pad11)") (class "Default")
      (node (ref "E84") (pin "11") (pinfunction "2Y1_11") (pintype "tri_state"))
    )
    (net (code "328") (name "unconnected-(E84A-2Y2-Pad13)") (class "Default")
      (node (ref "E84") (pin "13") (pinfunction "2Y2_13") (pintype "tri_state"))
    )
    (net (code "329") (name "unconnected-(E85A-D2-Pad4)") (class "Default")
      (node (ref "E85") (pin "4") (pinfunction "D2_4") (pintype "input"))
    )
    (net (code "330") (name "unconnected-(E85A-Q2-Pad5)") (class "Default")
      (node (ref "E85") (pin "5") (pinfunction "Q2_5") (pintype "output"))
    )
    (net (code "331") (name "unconnected-(E86A-2A2-Pad14)") (class "Default")
      (node (ref "E86") (pin "14") (pinfunction "2A2_14") (pintype "input"))
    )
    (net (code "332") (name "unconnected-(E86A-2Y2-Pad13)") (class "Default")
      (node (ref "E86") (pin "13") (pinfunction "2Y2_13") (pintype "tri_state"))
    )
    (net (code "333") (name "unconnected-(E87A-O3-Pad9)") (class "Default")
      (node (ref "E87") (pin "9") (pinfunction "O3_9") (pintype "tri_state"))
    )
    (net (code "334") (name "unconnected-(E93A-D1-Pad4)") (class "Default")
      (node (ref "E93") (pin "4") (pinfunction "D1_4") (pintype "input"))
    )
    (net (code "335") (name "unconnected-(E93A-Q1-Pad2)") (class "Default")
      (node (ref "E93") (pin "2") (pinfunction "Q1_2") (pintype "output"))
    )
    (net (code "336") (name "unconnected-(E93A-~{Q1}-Pad3)") (class "Default")
      (node (ref "E93") (pin "3") (pinfunction "~{Q1}_3") (pintype "output"))
    )
    (net (code "337") (name "unconnected-(E94C-I0-Pad9)") (class "Default")
      (node (ref "E94") (pin "9") (pinfunction "I0_9") (pintype "input"))
    )
    (net (code "338") (name "unconnected-(E94C-I1-Pad10)") (class "Default")
      (node (ref "E94") (pin "10") (pinfunction "I1_10") (pintype "input"))
    )
    (net (code "339") (name "unconnected-(E94C-O-Pad8)") (class "Default")
      (node (ref "E94") (pin "8") (pinfunction "O_8") (pintype "output"))
    )
    (net (code "340") (name "unconnected-(E94D-I0-Pad12)") (class "Default")
      (node (ref "E94") (pin "12") (pinfunction "I0_12") (pintype "input"))
    )
    (net (code "341") (name "unconnected-(E94D-I1-Pad13)") (class "Default")
      (node (ref "E94") (pin "13") (pinfunction "I1_13") (pintype "input"))
    )
    (net (code "342") (name "unconnected-(E94D-O-Pad11)") (class "Default")
      (node (ref "E94") (pin "11") (pinfunction "O_11") (pintype "output"))
    )
    (net (code "343") (name "unconnected-(E97A-CLR-Pad15)") (class "Default")
      (node (ref "E97") (pin "15") (pinfunction "CLR_15") (pintype "input"))
    )
    (net (code "344") (name "unconnected-(E97A-D1-Pad14)") (class "Default")
      (node (ref "E97") (pin "14") (pinfunction "D1_14") (pintype "input"))
    )
    (net (code "345") (name "unconnected-(E97A-G1-Pad9)") (class "Default")
      (node (ref "E97") (pin "9") (pinfunction "G1_9") (pintype "input"))
    )
    (net (code "346") (name "unconnected-(E97A-G2-Pad10)") (class "Default")
      (node (ref "E97") (pin "10") (pinfunction "G2_10") (pintype "input"))
    )
    (net (code "347") (name "unconnected-(E97A-Q1-Pad3)") (class "Default")
      (node (ref "E97") (pin "3") (pinfunction "Q1_3") (pintype "tri_state"))
    )
    (net (code "348") (name "unconnected-(E101D-A4-Pad10)") (class "Default")
      (node (ref "E101") (pin "10") (pinfunction "A4_10") (pintype "input"))
    )
    (net (code "349") (name "unconnected-(E101D-Y4-Pad9)") (class "Default")
      (node (ref "E101") (pin "9") (pinfunction "Y4_9") (pintype "tri_state"))
    )
    (net (code "350") (name "unconnected-(E102A-D1-Pad4)") (class "Default")
      (node (ref "E102") (pin "4") (pinfunction "D1_4") (pintype "input"))
    )
    (net (code "351") (name "unconnected-(E102A-Q1-Pad2)") (class "Default")
      (node (ref "E102") (pin "2") (pinfunction "Q1_2") (pintype "output"))
    )
    (net (code "352") (name "unconnected-(E102A-~{Q1}-Pad3)") (class "Default")
      (node (ref "E102") (pin "3") (pinfunction "~{Q1}_3") (pintype "output"))
    )
    (net (code "353") (name "unconnected-(E104A-1A4-Pad10)") (class "Default")
      (node (ref "E104") (pin "10") (pinfunction "1A4_10") (pintype "input"))
    )
    (net (code "354") (name "unconnected-(E104A-1Y4-Pad9)") (class "Default")
      (node (ref "E104") (pin "9") (pinfunction "1Y4_9") (pintype "tri_state"))
    )
    (net (code "355") (name "unconnected-(E104A-2A1-Pad12)") (class "Default")
      (node (ref "E104") (pin "12") (pinfunction "2A1_12") (pintype "input"))
    )
    (net (code "356") (name "unconnected-(E104A-2A2-Pad14)") (class "Default")
      (node (ref "E104") (pin "14") (pinfunction "2A2_14") (pintype "input"))
    )
    (net (code "357") (name "unconnected-(E104A-2G-Pad15)") (class "Default")
      (node (ref "E104") (pin "15") (pinfunction "2G_15") (pintype "input"))
    )
    (net (code "358") (name "unconnected-(E104A-2Y1-Pad11)") (class "Default")
      (node (ref "E104") (pin "11") (pinfunction "2Y1_11") (pintype "tri_state"))
    )
    (net (code "359") (name "unconnected-(E104A-2Y2-Pad13)") (class "Default")
      (node (ref "E104") (pin "13") (pinfunction "2Y2_13") (pintype "tri_state"))
    )
    (net (code "360") (name "unconnected-(E112A-O3-Pad9)") (class "Default")
      (node (ref "E112") (pin "9") (pinfunction "O3_9") (pintype "tri_state"))
    )
    (net (code "361") (name "unconnected-(E114A-O1-Pad11)") (class "Default")
      (node (ref "E114") (pin "11") (pinfunction "O1_11") (pintype "tri_state"))
    )
    (net (code "362") (name "unconnected-(E114A-O2-Pad10)") (class "Default")
      (node (ref "E114") (pin "10") (pinfunction "O2_10") (pintype "tri_state"))
    )
    (net (code "363") (name "unconnected-(E114A-O3-Pad9)") (class "Default")
      (node (ref "E114") (pin "9") (pinfunction "O3_9") (pintype "tri_state"))
    )
    (net (code "364") (name "unconnected-(E115F-I-Pad13)") (class "Default")
      (node (ref "E115") (pin "13") (pinfunction "I_13") (pintype "input"))
    )
    (net (code "365") (name "unconnected-(E115F-O-Pad12)") (class "Default")
      (node (ref "E115") (pin "12") (pinfunction "O_12") (pintype "output"))
    )
    (net (code "366") (name "~{C0}") (class "Default")
      (node (ref "E19") (pin "13") (pinfunction "O_13") (pintype "open_collector"))
      (node (ref "U$1") (pin "CE1") (pinfunction "1_CE1") (pintype "bidirectional"))
    )
    (net (code "367") (name "~{C1}") (class "Default")
      (node (ref "E19") (pin "10") (pinfunction "O_10") (pintype "open_collector"))
      (node (ref "U$1") (pin "CH1") (pinfunction "1_CH1") (pintype "bidirectional"))
    )
    (net (code "368") (name "~{CPMA_DISABLE}") (class "Default")
      (node (ref "E52") (pin "12") (pinfunction "I1_12") (pintype "input"))
      (node (ref "U$1") (pin "CU1") (pinfunction "1_CU1") (pintype "bidirectional"))
    )
    (net (code "369") (name "~{DATA00}") (class "Default")
      (node (ref "E12") (pin "4") (pinfunction "B3_4") (pintype "bidirectional"))
      (node (ref "U$1") (pin "AR1") (pinfunction "1_AR1") (pintype "bidirectional"))
    )
    (net (code "370") (name "~{DATA01}") (class "Default")
      (node (ref "E12") (pin "1") (pinfunction "B2_1") (pintype "bidirectional"))
      (node (ref "U$1") (pin "AS1") (pinfunction "1_AS1") (pintype "bidirectional"))
    )
    (net (code "371") (name "~{DATA02}") (class "Default")
      (node (ref "E12") (pin "12") (pinfunction "B1_12") (pintype "bidirectional"))
      (node (ref "U$1") (pin "AU1") (pinfunction "1_AU1") (pintype "bidirectional"))
    )
    (net (code "372") (name "~{DATA03}") (class "Default")
      (node (ref "E12") (pin "15") (pinfunction "B0_15") (pintype "bidirectional"))
      (node (ref "U$1") (pin "AV1") (pinfunction "1_AV1") (pintype "bidirectional"))
    )
    (net (code "373") (name "~{DATA04}") (class "Default")
      (node (ref "E13") (pin "4") (pinfunction "B3_4") (pintype "bidirectional"))
      (node (ref "U$1") (pin "BR1") (pinfunction "1_BR1") (pintype "bidirectional"))
    )
    (net (code "374") (name "~{DATA05}") (class "Default")
      (node (ref "E13") (pin "1") (pinfunction "B2_1") (pintype "bidirectional"))
      (node (ref "U$1") (pin "BS1") (pinfunction "1_BS1") (pintype "bidirectional"))
    )
    (net (code "375") (name "~{DATA06}") (class "Default")
      (node (ref "E13") (pin "12") (pinfunction "B1_12") (pintype "bidirectional"))
      (node (ref "U$1") (pin "BU1") (pinfunction "1_BU1") (pintype "bidirectional"))
    )
    (net (code "376") (name "~{DATA07}") (class "Default")
      (node (ref "E13") (pin "15") (pinfunction "B0_15") (pintype "bidirectional"))
      (node (ref "U$1") (pin "BV1") (pinfunction "1_BV1") (pintype "bidirectional"))
    )
    (net (code "377") (name "~{DATA08}") (class "Default")
      (node (ref "E45") (pin "4") (pinfunction "B3_4") (pintype "bidirectional"))
      (node (ref "U$1") (pin "DR1") (pinfunction "1_DR1") (pintype "bidirectional"))
    )
    (net (code "378") (name "~{DATA09}") (class "Default")
      (node (ref "E45") (pin "1") (pinfunction "B2_1") (pintype "bidirectional"))
      (node (ref "U$1") (pin "DS1") (pinfunction "1_DS1") (pintype "bidirectional"))
    )
    (net (code "379") (name "~{DATA10}") (class "Default")
      (node (ref "E45") (pin "12") (pinfunction "B1_12") (pintype "bidirectional"))
      (node (ref "U$1") (pin "DU1") (pinfunction "1_DU1") (pintype "bidirectional"))
    )
    (net (code "380") (name "~{DATA11}") (class "Default")
      (node (ref "E45") (pin "15") (pinfunction "B0_15") (pintype "bidirectional"))
      (node (ref "U$1") (pin "DV1") (pinfunction "1_DV1") (pintype "bidirectional"))
    )
    (net (code "381") (name "~{D}") (class "Default")
      (node (ref "E61") (pin "9") (pinfunction "I0_9") (pintype "input"))
      (node (ref "U$1") (pin "DK2") (pinfunction "1_DK2") (pintype "bidirectional"))
    )
    (net (code "382") (name "~{EMA0}") (class "Default")
      (node (ref "E1") (pin "6") (pinfunction "Q4_6") (pintype "tri_state"))
      (node (ref "E73") (pin "6") (pinfunction "Q4_6") (pintype "tri_state"))
      (node (ref "U$1") (pin "AH2") (pinfunction "1_AH2") (pintype "bidirectional"))
    )
    (net (code "383") (name "~{EMA1}") (class "Default")
      (node (ref "E1") (pin "5") (pinfunction "Q3_5") (pintype "tri_state"))
      (node (ref "E73") (pin "5") (pinfunction "Q3_5") (pintype "tri_state"))
      (node (ref "U$1") (pin "AE2") (pinfunction "1_AE2") (pintype "bidirectional"))
    )
    (net (code "384") (name "~{EMA2}") (class "Default")
      (node (ref "E1") (pin "4") (pinfunction "Q2_4") (pintype "tri_state"))
      (node (ref "E73") (pin "4") (pinfunction "Q2_4") (pintype "tri_state"))
      (node (ref "U$1") (pin "AD2") (pinfunction "1_AD2") (pintype "bidirectional"))
    )
    (net (code "385") (name "~{F_SET}") (class "Default")
      (node (ref "E75") (pin "7") (pinfunction "I1_7") (pintype "input"))
      (node (ref "U$1") (pin "DP2") (pinfunction "1_DP2") (pintype "bidirectional"))
    )
    (net (code "386") (name "~{F}") (class "Default")
      (node (ref "E61") (pin "12") (pinfunction "I1_12") (pintype "input"))
      (node (ref "U$1") (pin "DJ2") (pinfunction "1_DJ2") (pintype "bidirectional"))
    )
    (net (code "387") (name "~{IND1}") (class "Default")
      (node (ref "E72") (pin "5") (pinfunction "I1_5") (pintype "input"))
      (node (ref "U$1") (pin "CU2") (pinfunction "1_CU2") (pintype "bidirectional"))
    )
    (net (code "388") (name "~{IND2}") (class "Default")
      (node (ref "E72") (pin "7") (pinfunction "I1_7") (pintype "input"))
      (node (ref "U$1") (pin "CV2") (pinfunction "1_CV2") (pintype "bidirectional"))
    )
    (net (code "389") (name "~{INT_IN_PROG}") (class "Default")
      (node (ref "E3") (pin "7") (pinfunction "I1_7") (pintype "input"))
      (node (ref "U$1") (pin "BP2") (pinfunction "1_BP2") (pintype "bidirectional"))
    )
    (net (code "390") (name "~{INT_RQST}") (class "Default")
      (node (ref "E42") (pin "1") (pinfunction "O_1") (pintype "open_collector"))
      (node (ref "E42") (pin "13") (pinfunction "O_13") (pintype "open_collector"))
      (node (ref "U$1") (pin "CP1") (pinfunction "1_CP1") (pintype "bidirectional"))
    )
    (net (code "391") (name "~{IR0}") (class "Default")
      (node (ref "E61") (pin "7") (pinfunction "I1_7") (pintype "input"))
      (node (ref "U$1") (pin "DD2") (pinfunction "1_DD2") (pintype "bidirectional"))
    )
    (net (code "392") (name "~{IR1}") (class "Default")
      (node (ref "E61") (pin "5") (pinfunction "I1_5") (pintype "input"))
      (node (ref "U$1") (pin "DE2") (pinfunction "1_DE2") (pintype "bidirectional"))
    )
    (net (code "393") (name "~{KEY_CONTROL}") (class "Default")
      (node (ref "E51") (pin "9") (pinfunction "I0_9") (pintype "input"))
      (node (ref "U$1") (pin "DU2") (pinfunction "1_DU2") (pintype "bidirectional"))
    )
    (net (code "394") (name "~{LA_EN}") (class "Default")
      (node (ref "E41") (pin "7") (pinfunction "I1_7") (pintype "input"))
      (node (ref "E51") (pin "10") (pinfunction "I1_10") (pintype "input"))
      (node (ref "U$1") (pin "BM2") (pinfunction "1_BM2") (pintype "bidirectional"))
    )
    (net (code "395") (name "~{LINK}") (class "Default")
      (node (ref "E3") (pin "12") (pinfunction "I1_12") (pintype "input"))
      (node (ref "U$1") (pin "AV2") (pinfunction "1_AV2") (pintype "bidirectional"))
    )
    (net (code "396") (name "~{MD00}") (class "Default")
      (node (ref "E11") (pin "7") (pinfunction "I1_7") (pintype "input"))
      (node (ref "U$1") (pin "AK1") (pinfunction "1_AK1") (pintype "bidirectional"))
    )
    (net (code "397") (name "~{MD01}") (class "Default")
      (node (ref "E11") (pin "4") (pinfunction "I0_4") (pintype "input"))
      (node (ref "U$1") (pin "AL1") (pinfunction "1_AL1") (pintype "bidirectional"))
    )
    (net (code "398") (name "~{MD02}") (class "Default")
      (node (ref "E11") (pin "11") (pinfunction "I0_11") (pintype "input"))
      (node (ref "U$1") (pin "AM1") (pinfunction "1_AM1") (pintype "bidirectional"))
    )
    (net (code "399") (name "~{MD03}") (class "Default")
      (node (ref "E11") (pin "10") (pinfunction "I1_10") (pintype "input"))
      (node (ref "U$1") (pin "AP1") (pinfunction "1_AP1") (pintype "bidirectional"))
    )
    (net (code "400") (name "~{MD04}") (class "Default")
      (node (ref "E25") (pin "7") (pinfunction "I1_7") (pintype "input"))
      (node (ref "U$1") (pin "BK1") (pinfunction "1_BK1") (pintype "bidirectional"))
    )
    (net (code "401") (name "~{MD05}") (class "Default")
      (node (ref "E25") (pin "4") (pinfunction "I0_4") (pintype "input"))
      (node (ref "U$1") (pin "BL1") (pinfunction "1_BL1") (pintype "bidirectional"))
    )
    (net (code "402") (name "~{MD06}") (class "Default")
      (node (ref "E25") (pin "11") (pinfunction "I0_11") (pintype "input"))
      (node (ref "U$1") (pin "BM1") (pinfunction "1_BM1") (pintype "bidirectional"))
    )
    (net (code "403") (name "~{MD07}") (class "Default")
      (node (ref "E25") (pin "10") (pinfunction "I1_10") (pintype "input"))
      (node (ref "U$1") (pin "BP1") (pinfunction "1_BP1") (pintype "bidirectional"))
    )
    (net (code "404") (name "~{MD08}") (class "Default")
      (node (ref "E71") (pin "7") (pinfunction "I1_7") (pintype "input"))
      (node (ref "U$1") (pin "DK1") (pinfunction "1_DK1") (pintype "bidirectional"))
    )
    (net (code "405") (name "~{MD09}") (class "Default")
      (node (ref "E71") (pin "4") (pinfunction "I0_4") (pintype "input"))
      (node (ref "U$1") (pin "DL1") (pinfunction "1_DL1") (pintype "bidirectional"))
    )
    (net (code "406") (name "~{MD10}") (class "Default")
      (node (ref "E71") (pin "11") (pinfunction "I0_11") (pintype "input"))
      (node (ref "U$1") (pin "DM1") (pinfunction "1_DM1") (pintype "bidirectional"))
    )
    (net (code "407") (name "~{MD11}") (class "Default")
      (node (ref "E71") (pin "10") (pinfunction "I1_10") (pintype "input"))
      (node (ref "U$1") (pin "DP1") (pinfunction "1_DP1") (pintype "bidirectional"))
    )
    (net (code "408") (name "~{P1_ENRF}") (class "Default")
      (node (ref "E112") (pin "13") (pinfunction "~{G}_13") (pintype "input"))
      (node (ref "E114") (pin "13") (pinfunction "~{G}_13") (pintype "input"))
      (node (ref "E33") (pin "11") (pinfunction "O_11") (pintype "output"))
      (node (ref "E8") (pin "5") (pinfunction "I0_5") (pintype "input"))
    )
    (net (code "409") (name "~{P2_BCPMAD}") (class "Default")
      (node (ref "E52") (pin "13") (pinfunction "O_13") (pintype "output"))
      (node (ref "E63") (pin "12") (pinfunction "D_12") (pintype "input"))
    )
    (net (code "410") (name "~{P2_DFA}") (class "Default")
      (node (ref "E101") (pin "6") (pinfunction "A3_6") (pintype "input"))
      (node (ref "E102") (pin "7") (pinfunction "Q2_7") (pintype "output"))
      (node (ref "E103") (pin "14") (pinfunction "D6_14") (pintype "input"))
      (node (ref "E104") (pin "6") (pinfunction "1A3_6") (pintype "input"))
    )
    (net (code "411") (name "~{P2_DFB}") (class "Default")
      (node (ref "E101") (pin "4") (pinfunction "A2_4") (pintype "input"))
      (node (ref "E102") (pin "10") (pinfunction "Q3_10") (pintype "output"))
      (node (ref "E103") (pin "13") (pinfunction "D5_13") (pintype "input"))
      (node (ref "E104") (pin "4") (pinfunction "1A2_4") (pintype "input"))
    )
    (net (code "412") (name "~{P2_DFC}") (class "Default")
      (node (ref "E101") (pin "2") (pinfunction "A1_2") (pintype "input"))
      (node (ref "E102") (pin "15") (pinfunction "Q4_15") (pintype "output"))
      (node (ref "E103") (pin "11") (pinfunction "D4_11") (pintype "input"))
      (node (ref "E104") (pin "2") (pinfunction "1A1_2") (pintype "input"))
    )
    (net (code "413") (name "~{P2_ELAR}") (class "Default")
      (node (ref "E1") (pin "1") (pinfunction "M_1") (pintype "input"))
      (node (ref "E1") (pin "2") (pinfunction "N_2") (pintype "input"))
      (node (ref "E63") (pin "5") (pinfunction "Q_5") (pintype "output"))
    )
    (net (code "414") (name "~{P2_EMAEN}") (class "Default")
      (node (ref "E63") (pin "8") (pinfunction "~{Q}_8") (pintype "output"))
      (node (ref "E73") (pin "1") (pinfunction "M_1") (pintype "input"))
      (node (ref "E73") (pin "2") (pinfunction "N_2") (pintype "input"))
    )
    (net (code "415") (name "~{P2_IFA}") (class "Default")
      (node (ref "E103") (pin "6") (pinfunction "D3_6") (pintype "input"))
      (node (ref "E83") (pin "2") (pinfunction "A1_2") (pintype "input"))
      (node (ref "E84") (pin "6") (pinfunction "1A3_6") (pintype "input"))
      (node (ref "E93") (pin "7") (pinfunction "Q2_7") (pintype "output"))
    )
    (net (code "416") (name "~{P2_IFB}") (class "Default")
      (node (ref "E103") (pin "4") (pinfunction "D2_4") (pintype "input"))
      (node (ref "E83") (pin "4") (pinfunction "A2_4") (pintype "input"))
      (node (ref "E84") (pin "4") (pinfunction "1A2_4") (pintype "input"))
      (node (ref "E93") (pin "10") (pinfunction "Q3_10") (pintype "output"))
    )
    (net (code "417") (name "~{P2_IFC}") (class "Default")
      (node (ref "E103") (pin "3") (pinfunction "D1_3") (pintype "input"))
      (node (ref "E83") (pin "6") (pinfunction "A3_6") (pintype "input"))
      (node (ref "E84") (pin "2") (pinfunction "1A1_2") (pintype "input"))
      (node (ref "E93") (pin "15") (pinfunction "Q4_15") (pintype "output"))
    )
    (net (code "418") (name "~{P2_INT}") (class "Default")
      (node (ref "E115") (pin "4") (pinfunction "O_4") (pintype "output"))
      (node (ref "E92") (pin "2") (pinfunction "I1_2") (pintype "input"))
    )
    (net (code "419") (name "~{P2_RST}") (class "Default")
      (node (ref "E63") (pin "13") (pinfunction "CLR_13") (pintype "input"))
      (node (ref "E67") (pin "6") (pinfunction "O_6") (pintype "output"))
      (node (ref "E85") (pin "1") (pinfunction "CLR_1") (pintype "input"))
      (node (ref "E88") (pin "1") (pinfunction "CLR_1") (pintype "input"))
    )
    (net (code "420") (name "~{P3_BINIT}") (class "Default")
      (node (ref "E22") (pin "4") (pinfunction "O_4") (pintype "output"))
      (node (ref "E32") (pin "10") (pinfunction "PRE_10") (pintype "input"))
    )
    (net (code "421") (name "~{P3_BM0}") (class "Default")
      (node (ref "E29") (pin "2") (pinfunction "I0_2") (pintype "input"))
      (node (ref "E5") (pin "10") (pinfunction "O_10") (pintype "output"))
    )
    (net (code "422") (name "~{P3_BM2}") (class "Default")
      (node (ref "E30") (pin "3") (pinfunction "I2_3") (pintype "input"))
      (node (ref "E5") (pin "12") (pinfunction "O_12") (pintype "output"))
    )
    (net (code "423") (name "~{P3_BM3}") (class "Default")
      (node (ref "E49") (pin "5") (pinfunction "I2_5") (pintype "input"))
      (node (ref "E7") (pin "10") (pinfunction "O_10") (pintype "output"))
    )
    (net (code "424") (name "~{P3_BM4}") (class "Default")
      (node (ref "E36") (pin "9") (pinfunction "I0_9") (pintype "input"))
      (node (ref "E43") (pin "2") (pinfunction "I1_2") (pintype "input"))
      (node (ref "E7") (pin "12") (pinfunction "O_12") (pintype "output"))
    )
    (net (code "425") (name "~{P3_BM11}") (class "Default")
      (node (ref "E43") (pin "1") (pinfunction "I0_1") (pintype "input"))
      (node (ref "E44") (pin "12") (pinfunction "O_12") (pintype "output"))
    )
    (net (code "426") (name "~{P3_BTP3}") (class "Default")
      (node (ref "E26") (pin "13") (pinfunction "1C,2C_13") (pintype "input"))
      (node (ref "E29") (pin "11") (pinfunction "I0_11") (pintype "input"))
      (node (ref "E38") (pin "1") (pinfunction "I0_1") (pintype "input"))
      (node (ref "E38") (pin "2") (pinfunction "I1_2") (pintype "input"))
      (node (ref "E47") (pin "11") (pinfunction "I0_11") (pintype "input"))
      (node (ref "E51") (pin "2") (pinfunction "O_2") (pintype "output"))
    )
    (net (code "427") (name "~{P3_CFROM}") (class "Default")
      (node (ref "E14") (pin "12") (pinfunction "O5_12") (pintype "tri_state"))
      (node (ref "E28") (pin "13") (pinfunction "~{G1}_13") (pintype "input"))
    )
    (net (code "428") (name "~{P3_DECEN}") (class "Default")
      (node (ref "E14") (pin "11") (pinfunction "O6_11") (pintype "tri_state"))
      (node (ref "E31") (pin "18") (pinfunction "G1_18") (pintype "input"))
      (node (ref "E47") (pin "2") (pinfunction "I0_2") (pintype "input"))
    )
    (net (code "429") (name "~{P3_E2CFROM}") (class "Default")
      (node (ref "E26") (pin "15") (pinfunction "2Q_15") (pintype "output"))
      (node (ref "E28") (pin "14") (pinfunction "~{G2}_14") (pintype "input"))
    )
    (net (code "430") (name "~{P3_HOS}") (class "Default")
      (node (ref "E14") (pin "15") (pinfunction "O3_15") (pintype "tri_state"))
      (node (ref "E24") (pin "2") (pinfunction "I1_2") (pintype "input"))
    )
    (net (code "431") (name "~{P4_CDF}") (class "Default")
      (node (ref "E28") (pin "9") (pinfunction "O3_9") (pintype "tri_state"))
      (node (ref "E70") (pin "10") (pinfunction "I1_10") (pintype "input"))
      (node (ref "E80") (pin "12") (pinfunction "A2_12") (pintype "input"))
      (node (ref "R17") (pin "1") (pinfunction "1_1") (pintype "passive"))
    )
    (net (code "432") (name "~{P4_CIF}") (class "Default")
      (node (ref "E28") (pin "10") (pinfunction "O2_10") (pintype "tri_state"))
      (node (ref "E70") (pin "9") (pinfunction "I0_9") (pintype "input"))
      (node (ref "E80") (pin "11") (pinfunction "A1_11") (pintype "input"))
      (node (ref "R16") (pin "1") (pinfunction "1_1") (pintype "passive"))
    )
    (net (code "433") (name "~{P4_CINT}") (class "Default")
      (node (ref "E31") (pin "9") (pinfunction "8_9") (pintype "output"))
      (node (ref "E33") (pin "5") (pinfunction "I1_5") (pintype "input"))
    )
    (net (code "434") (name "~{P4_CUF}") (class "Default")
      (node (ref "E22") (pin "11") (pinfunction "I_11") (pintype "input"))
      (node (ref "E31") (pin "16") (pinfunction "14_16") (pintype "output"))
    )
    (net (code "435") (name "~{P4_CUMB}") (class "Default")
      (node (ref "E33") (pin "8") (pinfunction "O_8") (pintype "output"))
      (node (ref "E59") (pin "10") (pinfunction "PRE_10") (pintype "input"))
      (node (ref "E60") (pin "1") (pinfunction "CLR_1") (pintype "input"))
    )
    (net (code "436") (name "~{P4_DFEN}") (class "Default")
      (node (ref "E76") (pin "9") (pinfunction "Q_9") (pintype "output"))
      (node (ref "E92") (pin "13") (pinfunction "I2_13") (pintype "input"))
    )
    (net (code "437") (name "~{P4_FATAL}") (class "Default")
      (node (ref "E32") (pin "1") (pinfunction "CLR_1") (pintype "input"))
      (node (ref "E38") (pin "6") (pinfunction "O_6") (pintype "output"))
    )
    (net (code "438") (name "~{P4_GTF}") (class "Default")
      (node (ref "E18") (pin "12") (pinfunction "I0_12") (pintype "input"))
      (node (ref "E18") (pin "13") (pinfunction "I1_13") (pintype "input"))
      (node (ref "E43") (pin "6") (pinfunction "O_6") (pintype "output"))
      (node (ref "E56") (pin "3") (pinfunction "I0_3") (pintype "input"))
      (node (ref "E6") (pin "12") (pinfunction "I0_12") (pintype "input"))
    )
    (net (code "439") (name "~{P4_GTS}") (class "Default")
      (node (ref "E31") (pin "2") (pinfunction "1_2") (pintype "output"))
      (node (ref "E56") (pin "5") (pinfunction "I2_5") (pintype "input"))
      (node (ref "E6") (pin "13") (pinfunction "I1_13") (pintype "input"))
    )
    (net (code "440") (name "~{P4_LET_IO}") (class "Default")
      (node (ref "E24") (pin "11") (pinfunction "I2_11") (pintype "input"))
      (node (ref "E28") (pin "12") (pinfunction "O0_12") (pintype "tri_state"))
      (node (ref "E30") (pin "4") (pinfunction "I3_4") (pintype "input"))
      (node (ref "E30") (pin "5") (pinfunction "I4_5") (pintype "input"))
      (node (ref "E30") (pin "6") (pinfunction "I5_6") (pintype "input"))
      (node (ref "E64") (pin "5") (pinfunction "I0_5") (pintype "input"))
      (node (ref "E95") (pin "1") (pinfunction "1G_1") (pintype "input"))
      (node (ref "E95") (pin "15") (pinfunction "2G_15") (pintype "input"))
      (node (ref "R14") (pin "1") (pinfunction "1_1") (pintype "passive"))
    )
    (net (code "441") (name "~{P4_LRR}") (class "Default")
      (node (ref "E31") (pin "5") (pinfunction "4_5") (pintype "output"))
      (node (ref "E47") (pin "12") (pinfunction "I1_12") (pintype "input"))
    )
    (net (code "442") (name "~{P4_LUSR}") (class "Default")
      (node (ref "E29") (pin "12") (pinfunction "I1_12") (pintype "input"))
      (node (ref "E31") (pin "7") (pinfunction "6_7") (pintype "output"))
    )
    (net (code "443") (name "~{P4_PCLR}") (class "Default")
      (node (ref "E49") (pin "2") (pinfunction "I1_2") (pintype "input"))
      (node (ref "E63") (pin "4") (pinfunction "PRE_4") (pintype "input"))
      (node (ref "E67") (pin "5") (pinfunction "I1_5") (pintype "input"))
      (node (ref "E76") (pin "3") (pinfunction "CLK_3") (pintype "input"))
      (node (ref "PAD2") (pin "1") (pinfunction "P_1") (pintype "passive"))
    )
    (net (code "444") (name "~{P4_PLXA}") (class "Default")
      (node (ref "E49") (pin "13") (pinfunction "I2_13") (pintype "input"))
      (node (ref "E57") (pin "6") (pinfunction "O_6") (pintype "output"))
      (node (ref "E58") (pin "1") (pinfunction "I_1") (pintype "input"))
      (node (ref "E63") (pin "1") (pinfunction "CLR_1") (pintype "input"))
      (node (ref "E67") (pin "4") (pinfunction "I0_4") (pintype "input"))
    )
    (net (code "445") (name "~{P4_RDF}") (class "Default")
      (node (ref "E112") (pin "15") (pinfunction "A7_15") (pintype "input"))
      (node (ref "E114") (pin "15") (pinfunction "A7_15") (pintype "input"))
      (node (ref "E31") (pin "10") (pinfunction "9_10") (pintype "output"))
      (node (ref "E33") (pin "13") (pinfunction "I1_13") (pintype "input"))
    )
    (net (code "446") (name "~{P4_RIB}") (class "Default")
      (node (ref "E31") (pin "13") (pinfunction "11_13") (pintype "output"))
      (node (ref "E56") (pin "4") (pinfunction "I1_4") (pintype "input"))
    )
    (net (code "447") (name "~{P4_RIF}") (class "Default")
      (node (ref "E31") (pin "11") (pinfunction "10_11") (pintype "output"))
      (node (ref "E33") (pin "12") (pinfunction "I0_12") (pintype "input"))
    )
    (net (code "448") (name "~{P4_RMF}") (class "Default")
      (node (ref "E107") (pin "1") (pinfunction "1G_1") (pintype "input"))
      (node (ref "E107") (pin "15") (pinfunction "2G_15") (pintype "input"))
      (node (ref "E31") (pin "14") (pinfunction "12_14") (pintype "output"))
      (node (ref "E39") (pin "1") (pinfunction "I_1") (pintype "input"))
      (node (ref "E50") (pin "9") (pinfunction "I0_9") (pintype "input"))
      (node (ref "E70") (pin "13") (pinfunction "I1_13") (pintype "input"))
    )
    (net (code "449") (name "~{P4_RRR}") (class "Default")
      (node (ref "E31") (pin "6") (pinfunction "5_6") (pintype "output"))
      (node (ref "E86") (pin "1") (pinfunction "1G_1") (pintype "input"))
      (node (ref "E86") (pin "15") (pinfunction "2G_15") (pintype "input"))
    )
    (net (code "450") (name "~{P4_RTF}") (class "Default")
      (node (ref "E36") (pin "8") (pinfunction "O_8") (pintype "output"))
      (node (ref "E38") (pin "9") (pinfunction "I0_9") (pintype "input"))
      (node (ref "E80") (pin "14") (pinfunction "A4_14") (pintype "input"))
    )
    (net (code "451") (name "~{P4_RTS}") (class "Default")
      (node (ref "E31") (pin "3") (pinfunction "2_3") (pintype "output"))
      (node (ref "E38") (pin "10") (pinfunction "I1_10") (pintype "input"))
      (node (ref "E70") (pin "12") (pinfunction "I0_12") (pintype "input"))
    )
    (net (code "452") (name "~{P4_RUSR}") (class "Default")
      (node (ref "E106") (pin "1") (pinfunction "1G_1") (pintype "input"))
      (node (ref "E106") (pin "15") (pinfunction "2G_15") (pintype "input"))
      (node (ref "E31") (pin "8") (pinfunction "7_8") (pintype "output"))
    )
    (net (code "453") (name "~{P4_SINT}") (class "Default")
      (node (ref "E22") (pin "13") (pinfunction "I_13") (pintype "input"))
      (node (ref "E31") (pin "15") (pinfunction "13_15") (pintype "output"))
    )
    (net (code "454") (name "~{P4_SUF}") (class "Default")
      (node (ref "E31") (pin "17") (pinfunction "15_17") (pintype "output"))
      (node (ref "E39") (pin "3") (pinfunction "I_3") (pintype "input"))
      (node (ref "E67") (pin "2") (pinfunction "I1_2") (pintype "input"))
    )
    (net (code "455") (name "~{P4_USINT}") (class "Default")
      (node (ref "E24") (pin "4") (pinfunction "I1_4") (pintype "input"))
      (node (ref "E24") (pin "5") (pinfunction "I2_5") (pintype "input"))
      (node (ref "E32") (pin "9") (pinfunction "Q_9") (pintype "output"))
    )
    (net (code "456") (name "~{P6_DISF}") (class "Default")
      (node (ref "E101") (pin "1") (pinfunction "~{G}_1") (pintype "input"))
      (node (ref "E83") (pin "1") (pinfunction "~{G}_1") (pintype "input"))
      (node (ref "E94") (pin "3") (pinfunction "O_3") (pintype "output"))
    )
    (net (code "457") (name "~{P6_USM}") (class "Default")
      (node (ref "E59") (pin "2") (pinfunction "D_2") (pintype "input"))
      (node (ref "E59") (pin "9") (pinfunction "Q_9") (pintype "output"))
      (node (ref "E83") (pin "14") (pinfunction "A2_14") (pintype "input"))
    )
    (net (code "458") (name "~{PAUSE}") (class "Default")
      (node (ref "D1") (pin "C") (pinfunction "C_C") (pintype "passive"))
      (node (ref "E41") (pin "4") (pinfunction "I0_4") (pintype "input"))
      (node (ref "Q1") (pin "3") (pinfunction "C_3") (pintype "passive"))
      (node (ref "U$1") (pin "CD1") (pinfunction "1_CD1") (pintype "bidirectional"))
    )
    (net (code "459") (name "~{POWER_OK}") (class "Default")
      (node (ref "E41") (pin "9") (pinfunction "I0_9") (pintype "input"))
      (node (ref "U$1") (pin "BV2") (pinfunction "1_BV2") (pintype "bidirectional"))
    )
    (net (code "460") (name "~{RD0}") (class "Default")
      (node (ref "E4") (pin "10") (pinfunction "O_10") (pintype "open_collector"))
      (node (ref "E5") (pin "1") (pinfunction "I_1") (pintype "input"))
      (node (ref "R12") (pin "2") (pinfunction "2_2") (pintype "passive"))
    )
    (net (code "461") (name "~{RD1}") (class "Default")
      (node (ref "E5") (pin "3") (pinfunction "I_3") (pintype "input"))
      (node (ref "R9") (pin "2") (pinfunction "2_2") (pintype "passive"))
    )
    (net (code "462") (name "~{RD2}") (class "Default")
      (node (ref "E5") (pin "5") (pinfunction "I_5") (pintype "input"))
      (node (ref "R8") (pin "2") (pinfunction "2_2") (pintype "passive"))
    )
    (net (code "463") (name "~{RD3}") (class "Default")
      (node (ref "E5") (pin "9") (pinfunction "I_9") (pintype "input"))
      (node (ref "E8") (pin "13") (pinfunction "O_13") (pintype "open_collector"))
      (node (ref "E83") (pin "11") (pinfunction "Y1_11") (pintype "tri_state"))
      (node (ref "R2") (pin "2") (pinfunction "2_2") (pintype "passive"))
    )
    (net (code "464") (name "~{RD4}") (class "Default")
      (node (ref "E7") (pin "1") (pinfunction "I_1") (pintype "input"))
      (node (ref "R1") (pin "2") (pinfunction "2_2") (pintype "passive"))
    )
    (net (code "465") (name "~{RD5}") (class "Default")
      (node (ref "E7") (pin "3") (pinfunction "I_3") (pintype "input"))
      (node (ref "E8") (pin "10") (pinfunction "O_10") (pintype "open_collector"))
      (node (ref "E83") (pin "13") (pinfunction "Y2_13") (pintype "tri_state"))
      (node (ref "R6") (pin "2") (pinfunction "2_2") (pintype "passive"))
    )
    (net (code "466") (name "~{RD6}") (class "Default")
      (node (ref "E105") (pin "13") (pinfunction "2Y2_13") (pintype "tri_state"))
      (node (ref "E106") (pin "3") (pinfunction "1Y1_3") (pintype "tri_state"))
      (node (ref "E114") (pin "12") (pinfunction "O0_12") (pintype "tri_state"))
      (node (ref "E7") (pin "5") (pinfunction "I_5") (pintype "input"))
      (node (ref "E83") (pin "7") (pinfunction "Y3_7") (pintype "tri_state"))
      (node (ref "R7") (pin "2") (pinfunction "2_2") (pintype "passive"))
    )
    (net (code "467") (name "~{RD7}") (class "Default")
      (node (ref "E105") (pin "11") (pinfunction "2Y1_11") (pintype "tri_state"))
      (node (ref "E106") (pin "5") (pinfunction "1Y2_5") (pintype "tri_state"))
      (node (ref "E112") (pin "11") (pinfunction "O1_11") (pintype "tri_state"))
      (node (ref "E7") (pin "9") (pinfunction "I_9") (pintype "input"))
      (node (ref "E83") (pin "5") (pinfunction "Y2_5") (pintype "tri_state"))
      (node (ref "E86") (pin "3") (pinfunction "1Y1_3") (pintype "tri_state"))
      (node (ref "R31") (pin "2") (pinfunction "2_2") (pintype "passive"))
    )
    (net (code "468") (name "~{RD8}") (class "Default")
      (node (ref "E105") (pin "9") (pinfunction "1Y4_9") (pintype "tri_state"))
      (node (ref "E106") (pin "7") (pinfunction "1Y3_7") (pintype "tri_state"))
      (node (ref "E112") (pin "12") (pinfunction "O0_12") (pintype "tri_state"))
      (node (ref "E44") (pin "1") (pinfunction "I_1") (pintype "input"))
      (node (ref "E83") (pin "3") (pinfunction "Y1_3") (pintype "tri_state"))
      (node (ref "E86") (pin "5") (pinfunction "1Y2_5") (pintype "tri_state"))
      (node (ref "R25") (pin "2") (pinfunction "2_2") (pintype "passive"))
    )
    (net (code "469") (name "~{RD9}") (class "Default")
      (node (ref "E101") (pin "3") (pinfunction "Y1_3") (pintype "tri_state"))
      (node (ref "E105") (pin "7") (pinfunction "1Y3_7") (pintype "tri_state"))
      (node (ref "E106") (pin "9") (pinfunction "1Y4_9") (pintype "tri_state"))
      (node (ref "E44") (pin "3") (pinfunction "I_3") (pintype "input"))
      (node (ref "E86") (pin "7") (pinfunction "1Y3_7") (pintype "tri_state"))
      (node (ref "R24") (pin "2") (pinfunction "2_2") (pintype "passive"))
    )
    (net (code "470") (name "~{RD10}") (class "Default")
      (node (ref "E101") (pin "5") (pinfunction "Y2_5") (pintype "tri_state"))
      (node (ref "E105") (pin "5") (pinfunction "1Y2_5") (pintype "tri_state"))
      (node (ref "E106") (pin "11") (pinfunction "2Y1_11") (pintype "tri_state"))
      (node (ref "E44") (pin "5") (pinfunction "I_5") (pintype "input"))
      (node (ref "E86") (pin "9") (pinfunction "1Y4_9") (pintype "tri_state"))
      (node (ref "R26") (pin "2") (pinfunction "2_2") (pintype "passive"))
    )
    (net (code "471") (name "~{RD11}") (class "Default")
      (node (ref "E101") (pin "7") (pinfunction "Y3_7") (pintype "tri_state"))
      (node (ref "E105") (pin "3") (pinfunction "1Y1_3") (pintype "tri_state"))
      (node (ref "E106") (pin "13") (pinfunction "2Y2_13") (pintype "tri_state"))
      (node (ref "E44") (pin "9") (pinfunction "I_9") (pintype "input"))
      (node (ref "E86") (pin "11") (pinfunction "2Y1_11") (pintype "tri_state"))
      (node (ref "R27") (pin "2") (pinfunction "2_2") (pintype "passive"))
    )
    (net (code "472") (name "~{RUN}") (class "Default")
      (node (ref "E66") (pin "4") (pinfunction "I0_4") (pintype "input"))
      (node (ref "U$1") (pin "BU2") (pinfunction "1_BU2") (pintype "bidirectional"))
    )
    (net (code "473") (name "~{SKIP}") (class "Default")
      (node (ref "E42") (pin "4") (pinfunction "O_4") (pintype "open_collector"))
      (node (ref "U$1") (pin "CS1") (pinfunction "1_CS1") (pintype "bidirectional"))
    )
    (net (code "474") (name "~{TS1}") (class "Default")
      (node (ref "E41") (pin "10") (pinfunction "I1_10") (pintype "input"))
      (node (ref "E41") (pin "11") (pinfunction "I0_11") (pintype "input"))
      (node (ref "U$1") (pin "CK2") (pinfunction "1_CK2") (pintype "bidirectional"))
    )
    (net (code "475") (name "~{TS3}") (class "Default")
      (node (ref "E51") (pin "12") (pinfunction "I1_12") (pintype "input"))
      (node (ref "U$1") (pin "CM2") (pinfunction "1_CM2") (pintype "bidirectional"))
    )
    (net (code "476") (name "~{TS4}") (class "Default")
      (node (ref "E51") (pin "4") (pinfunction "I0_4") (pintype "input"))
      (node (ref "E51") (pin "5") (pinfunction "I1_5") (pintype "input"))
      (node (ref "U$1") (pin "CP2") (pinfunction "1_CP2") (pintype "bidirectional"))
    )
    (net (code "477") (name "~{USER_MODE}") (class "Default")
      (node (ref "E8") (pin "1") (pinfunction "O_1") (pintype "open_collector"))
      (node (ref "E8") (pin "4") (pinfunction "O_4") (pintype "open_collector"))
      (node (ref "U$1") (pin "DM2") (pinfunction "1_DM2") (pintype "bidirectional"))
    )
  )
)
